# DL0WH_BiTuner_Ctrl_1V2.net
KiCad netlist of a schematic drawn in EAGLE
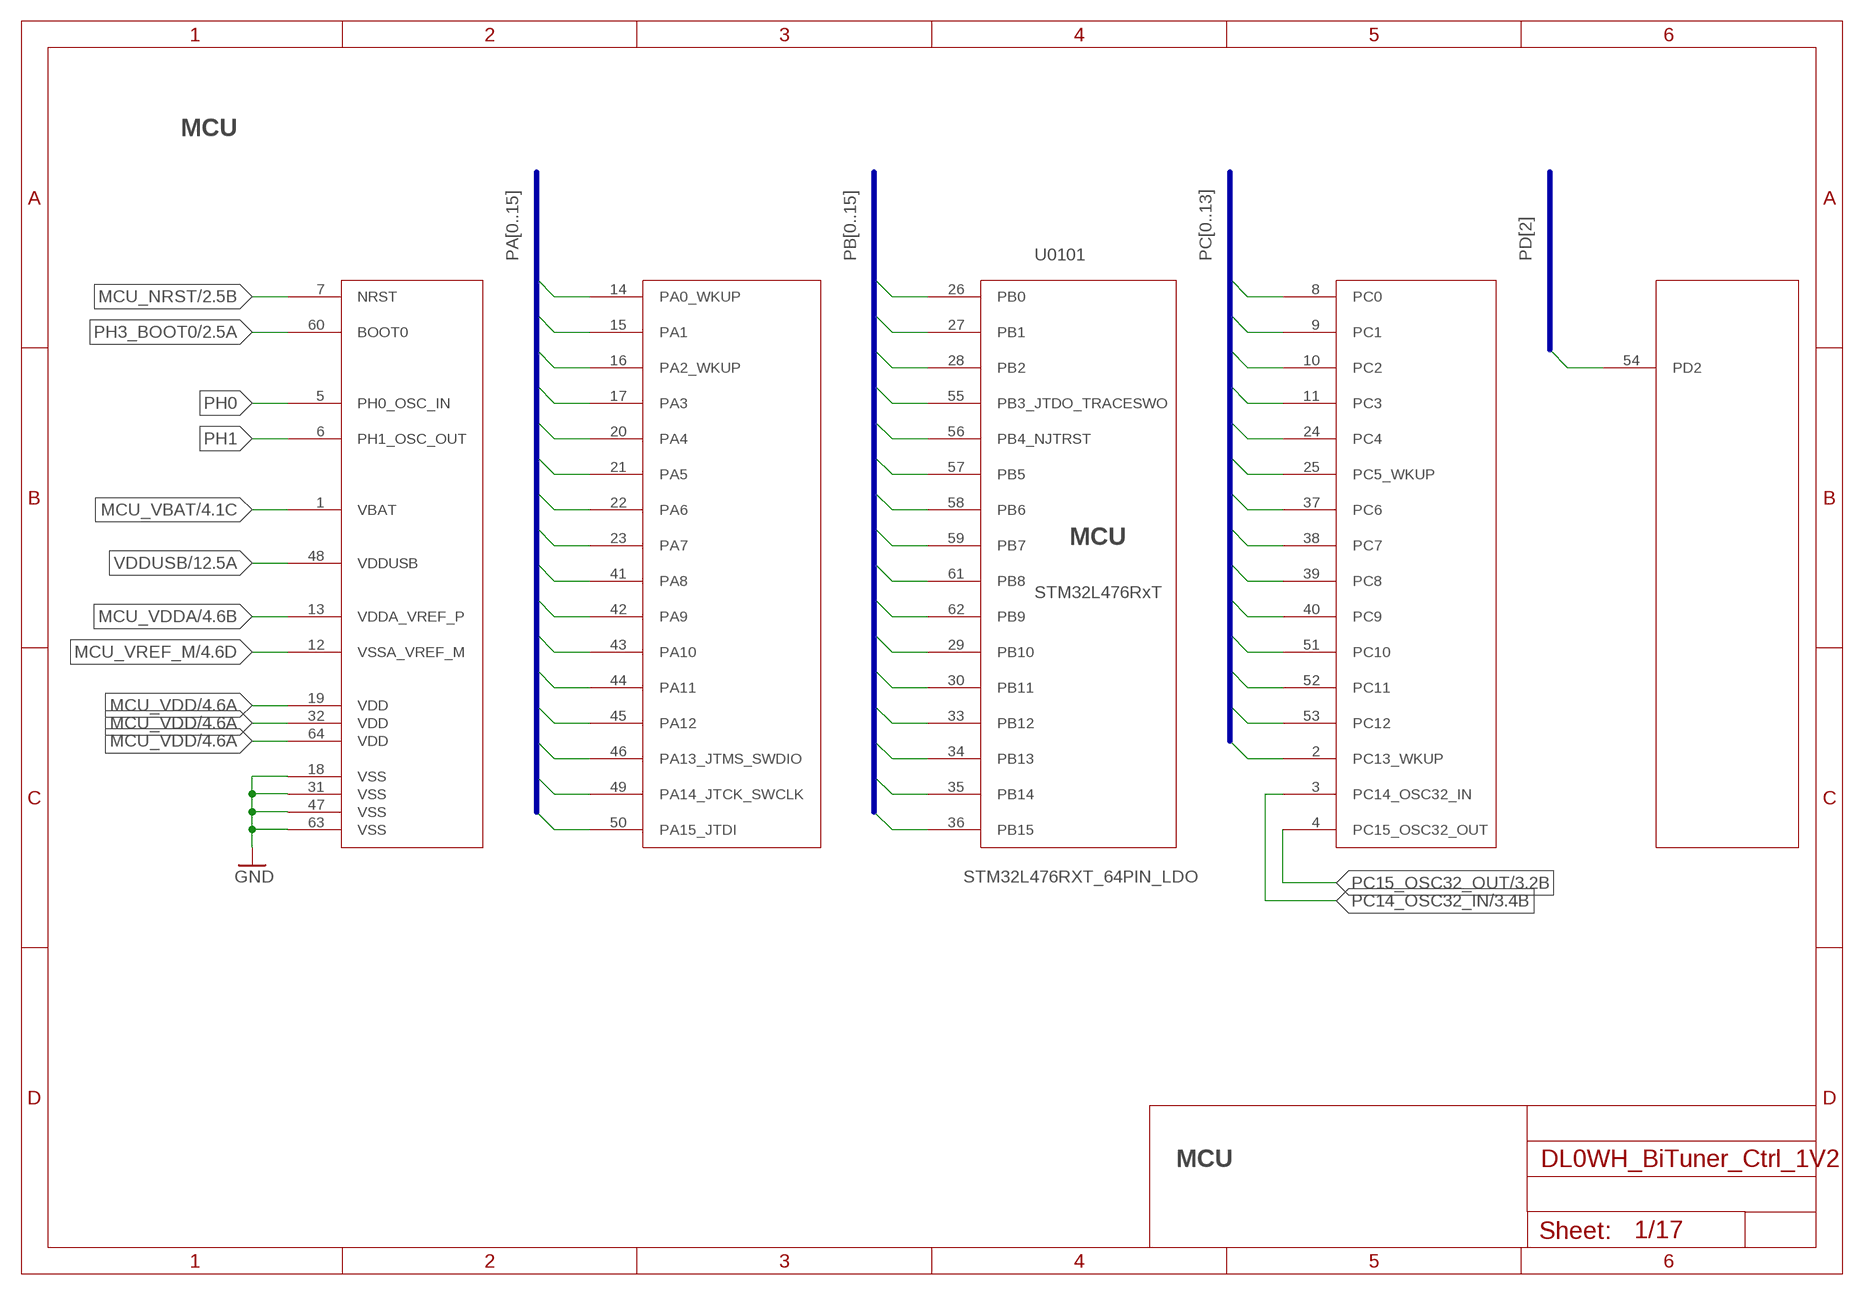
[diagram p0: schematic, sheet 1]
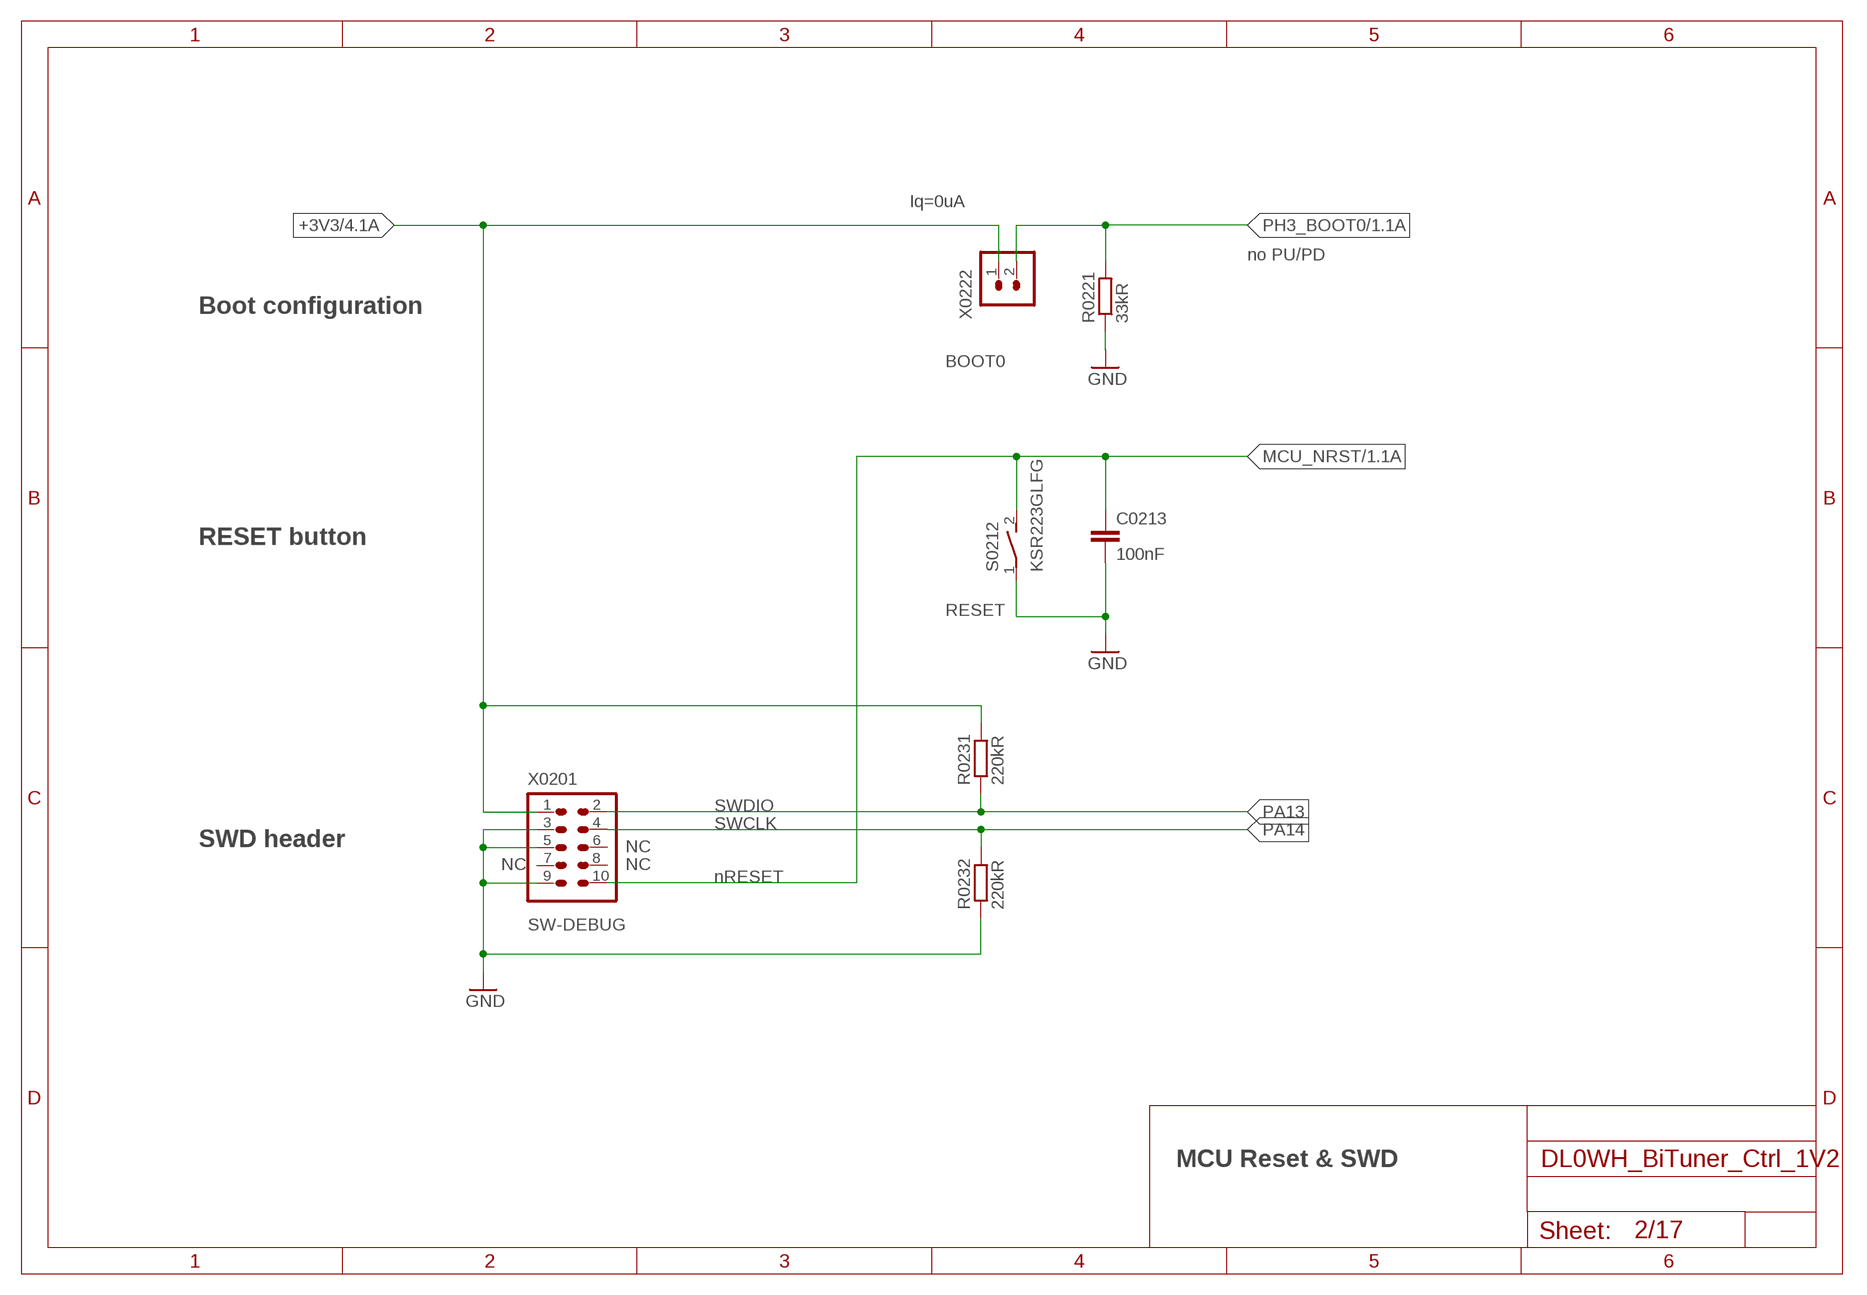
[diagram p1: schematic, sheet 2]
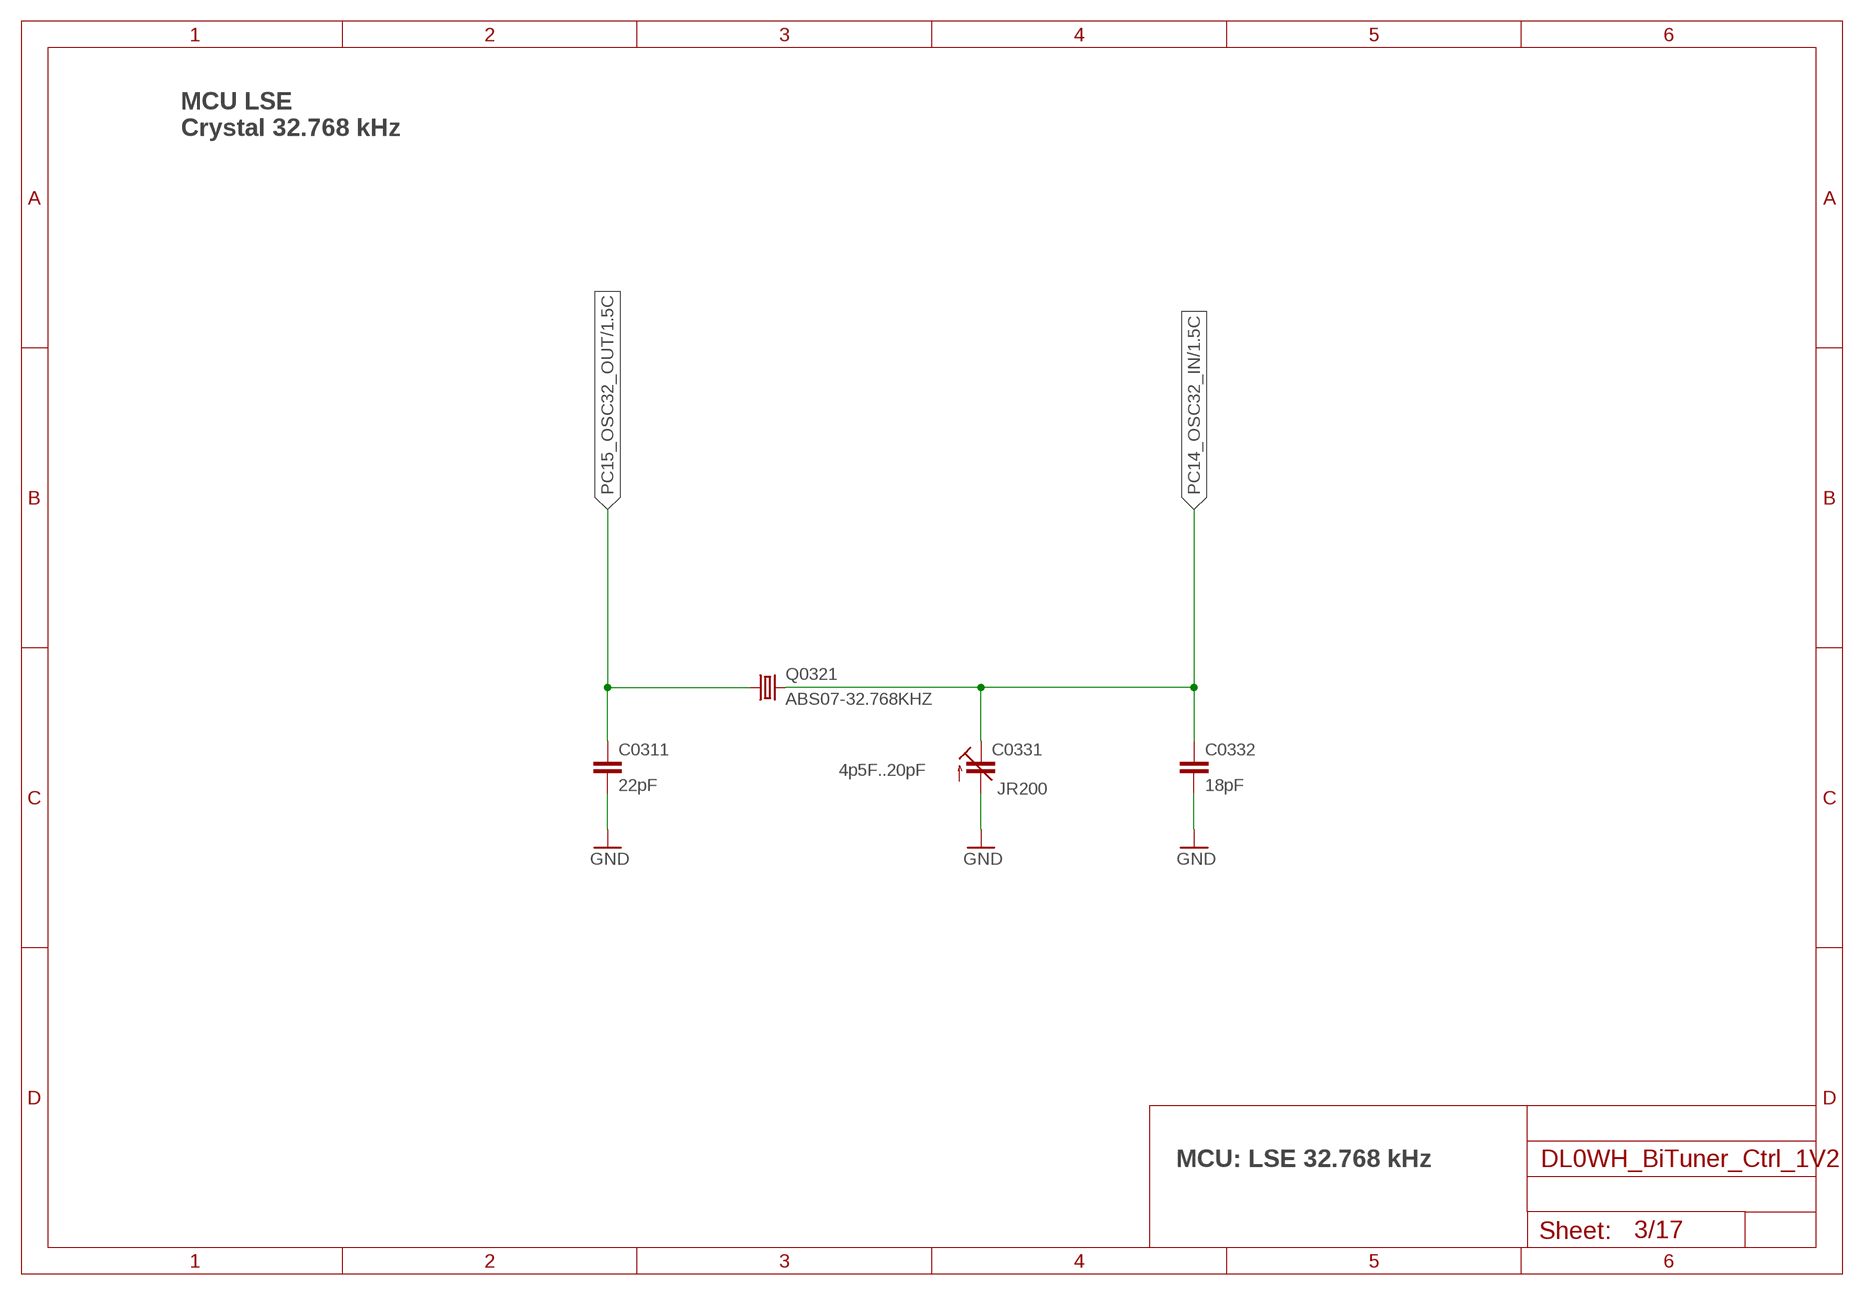
[diagram p2: schematic, sheet 3]
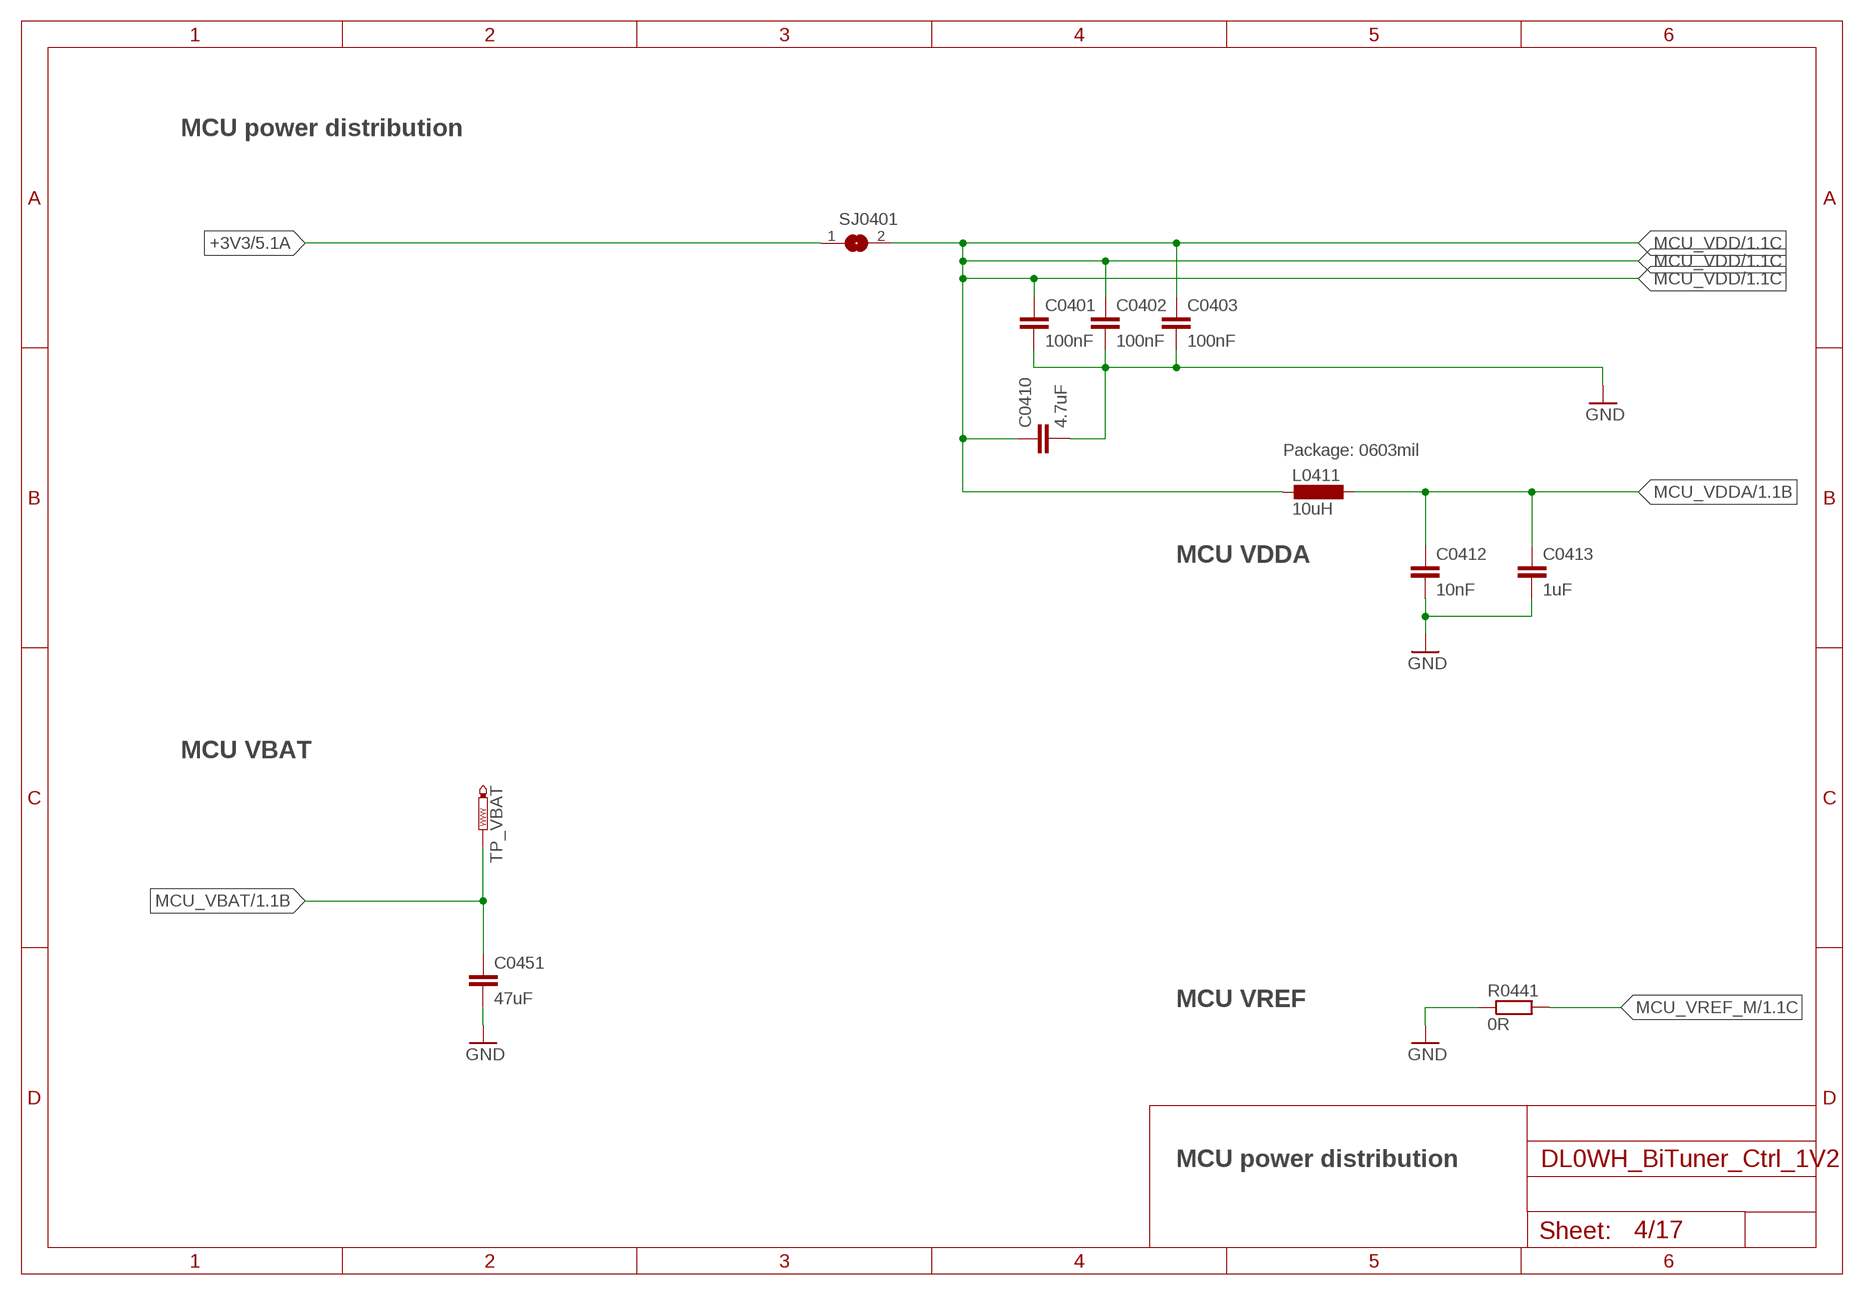
[diagram p3: schematic, sheet 4]
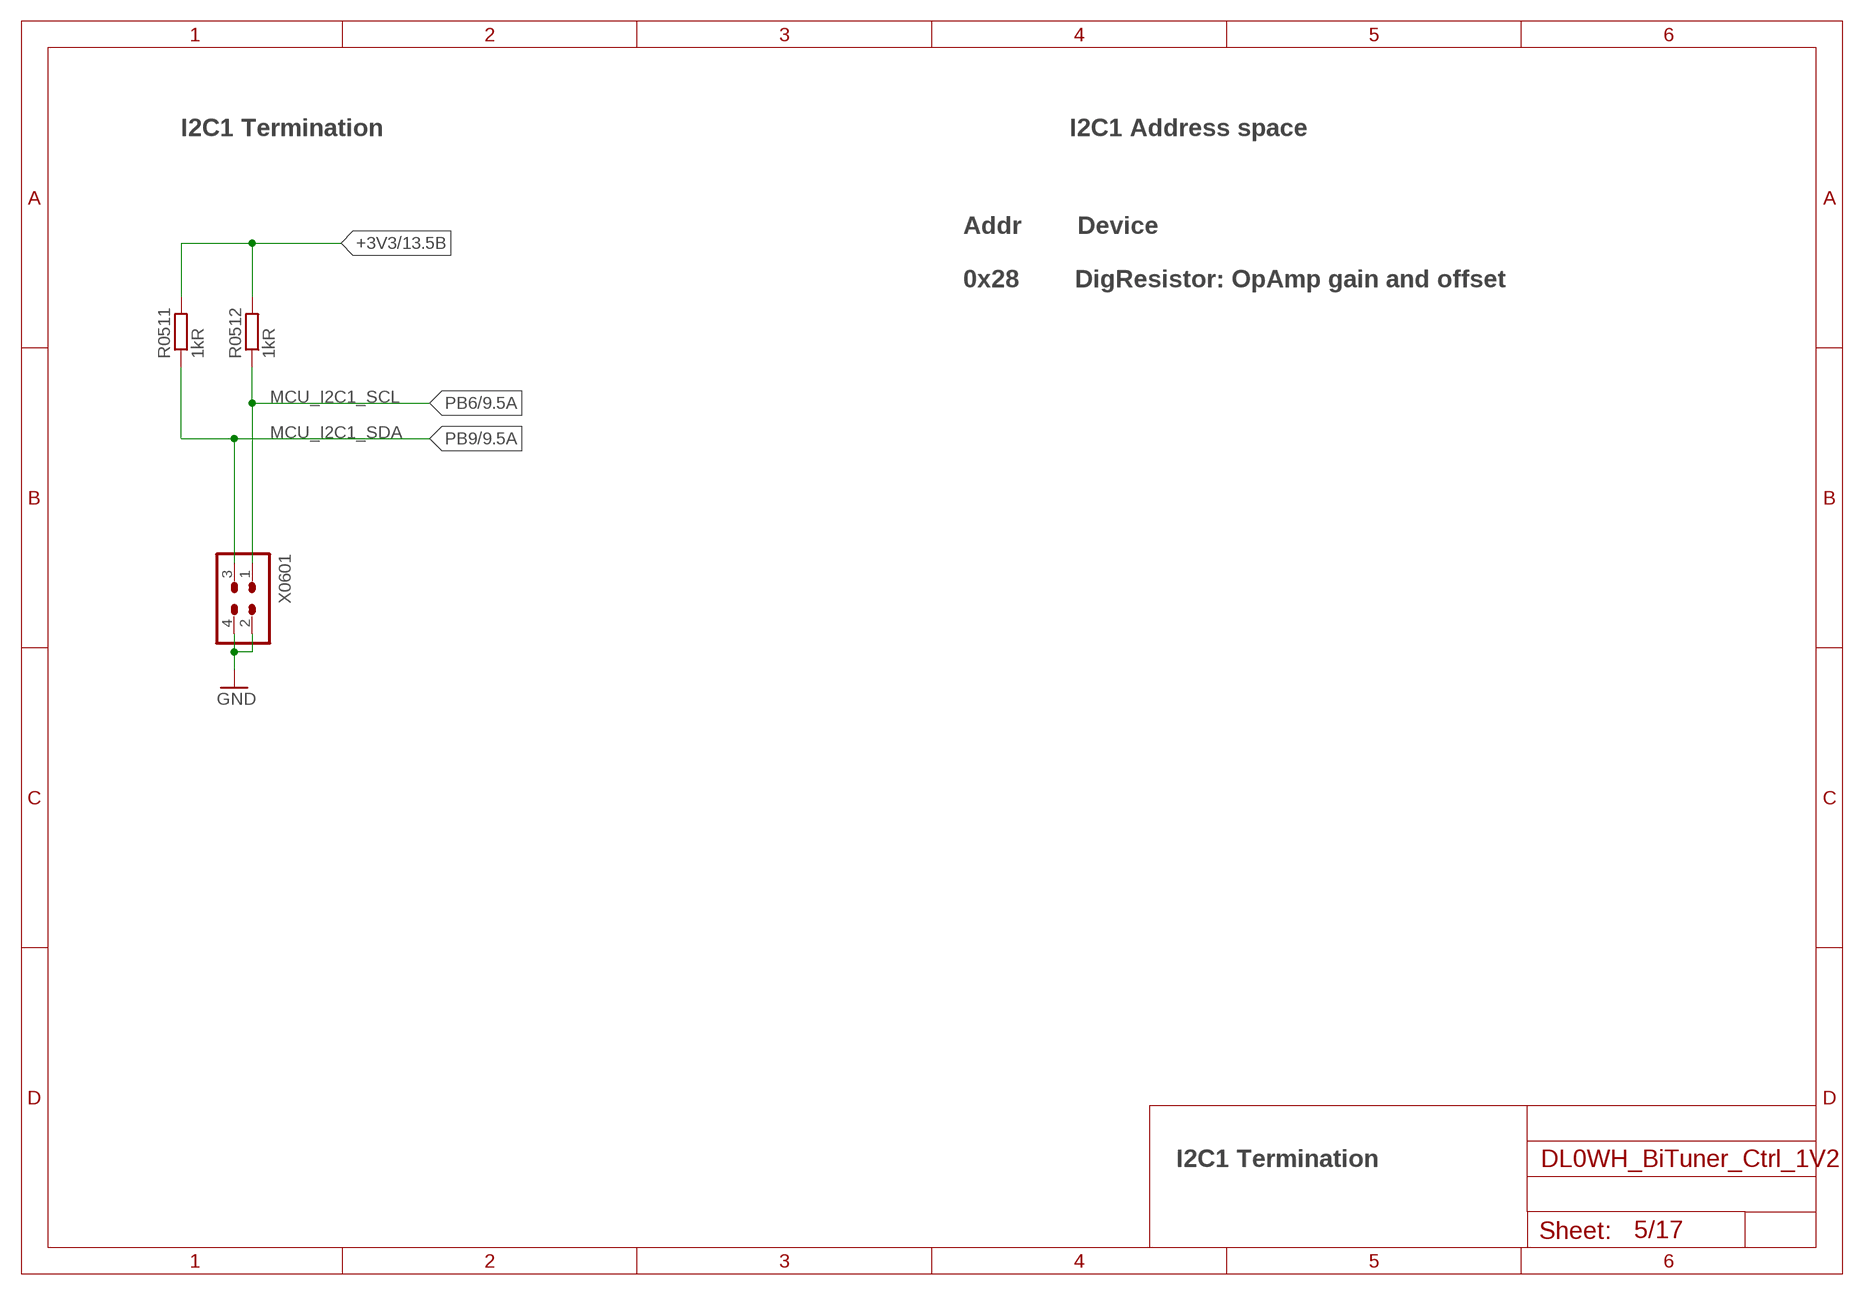
[diagram p4: schematic, sheet 5]
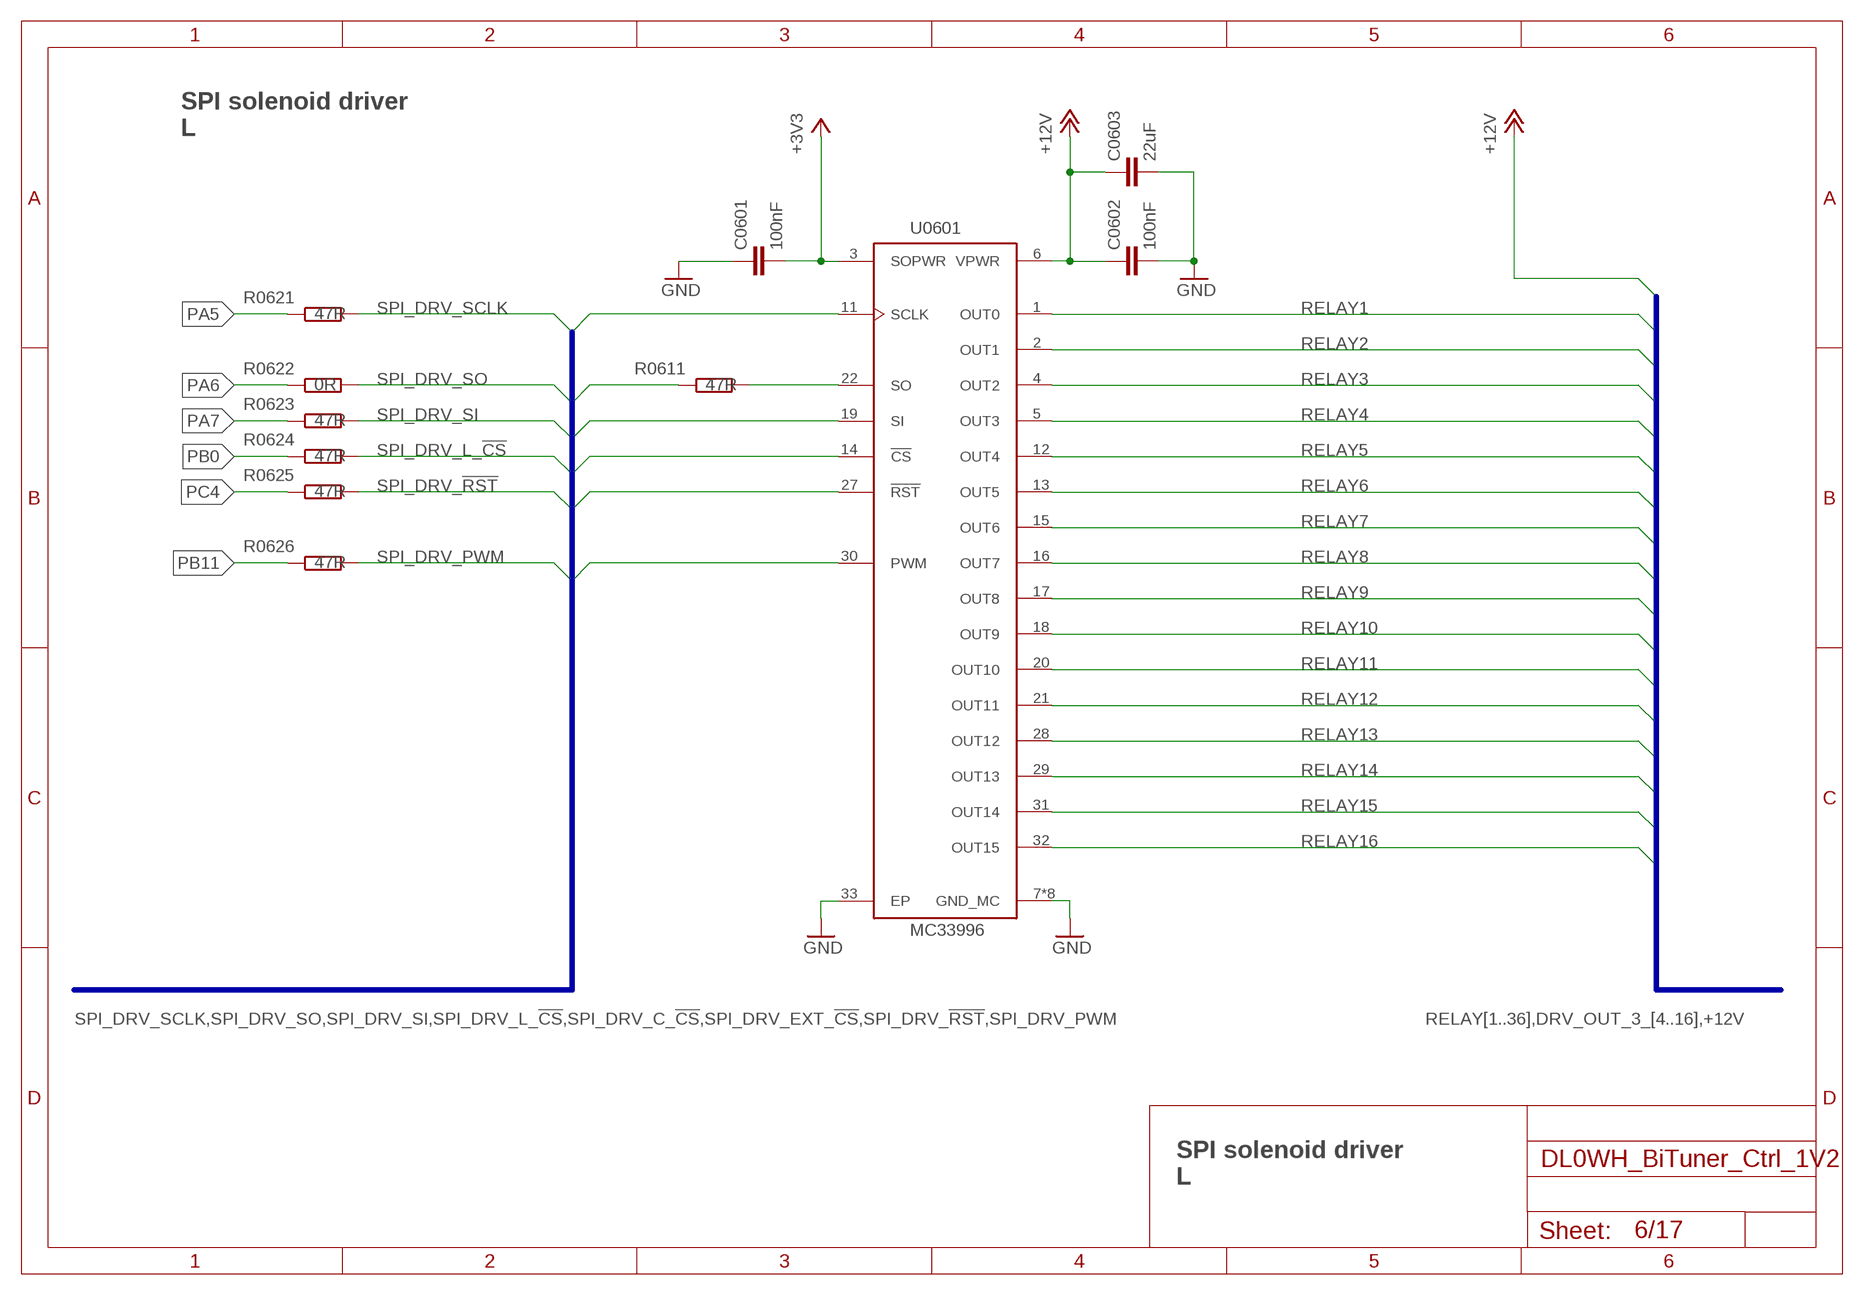
[diagram p5: schematic, sheet 6]
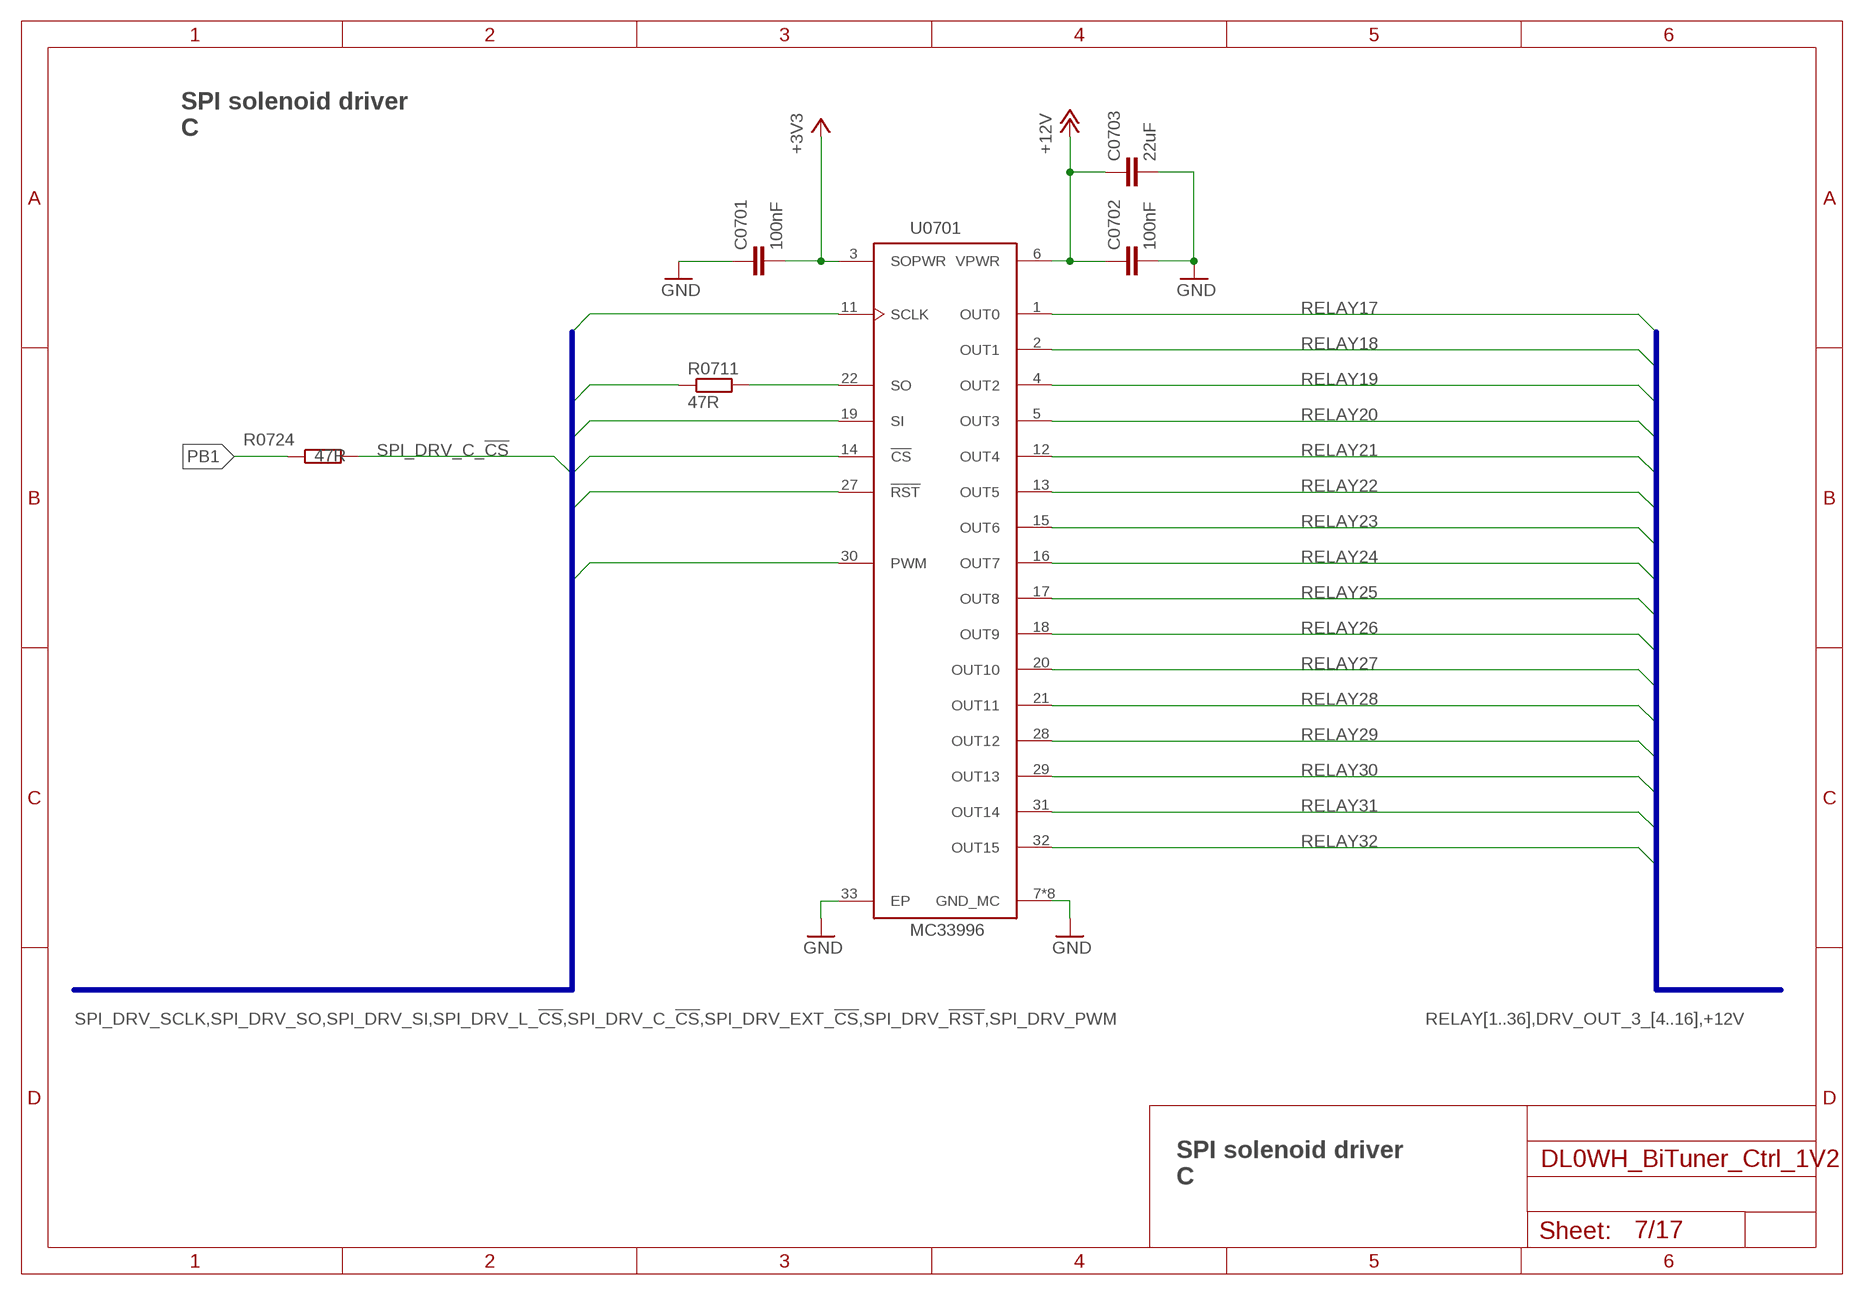
[diagram p6: schematic, sheet 7]
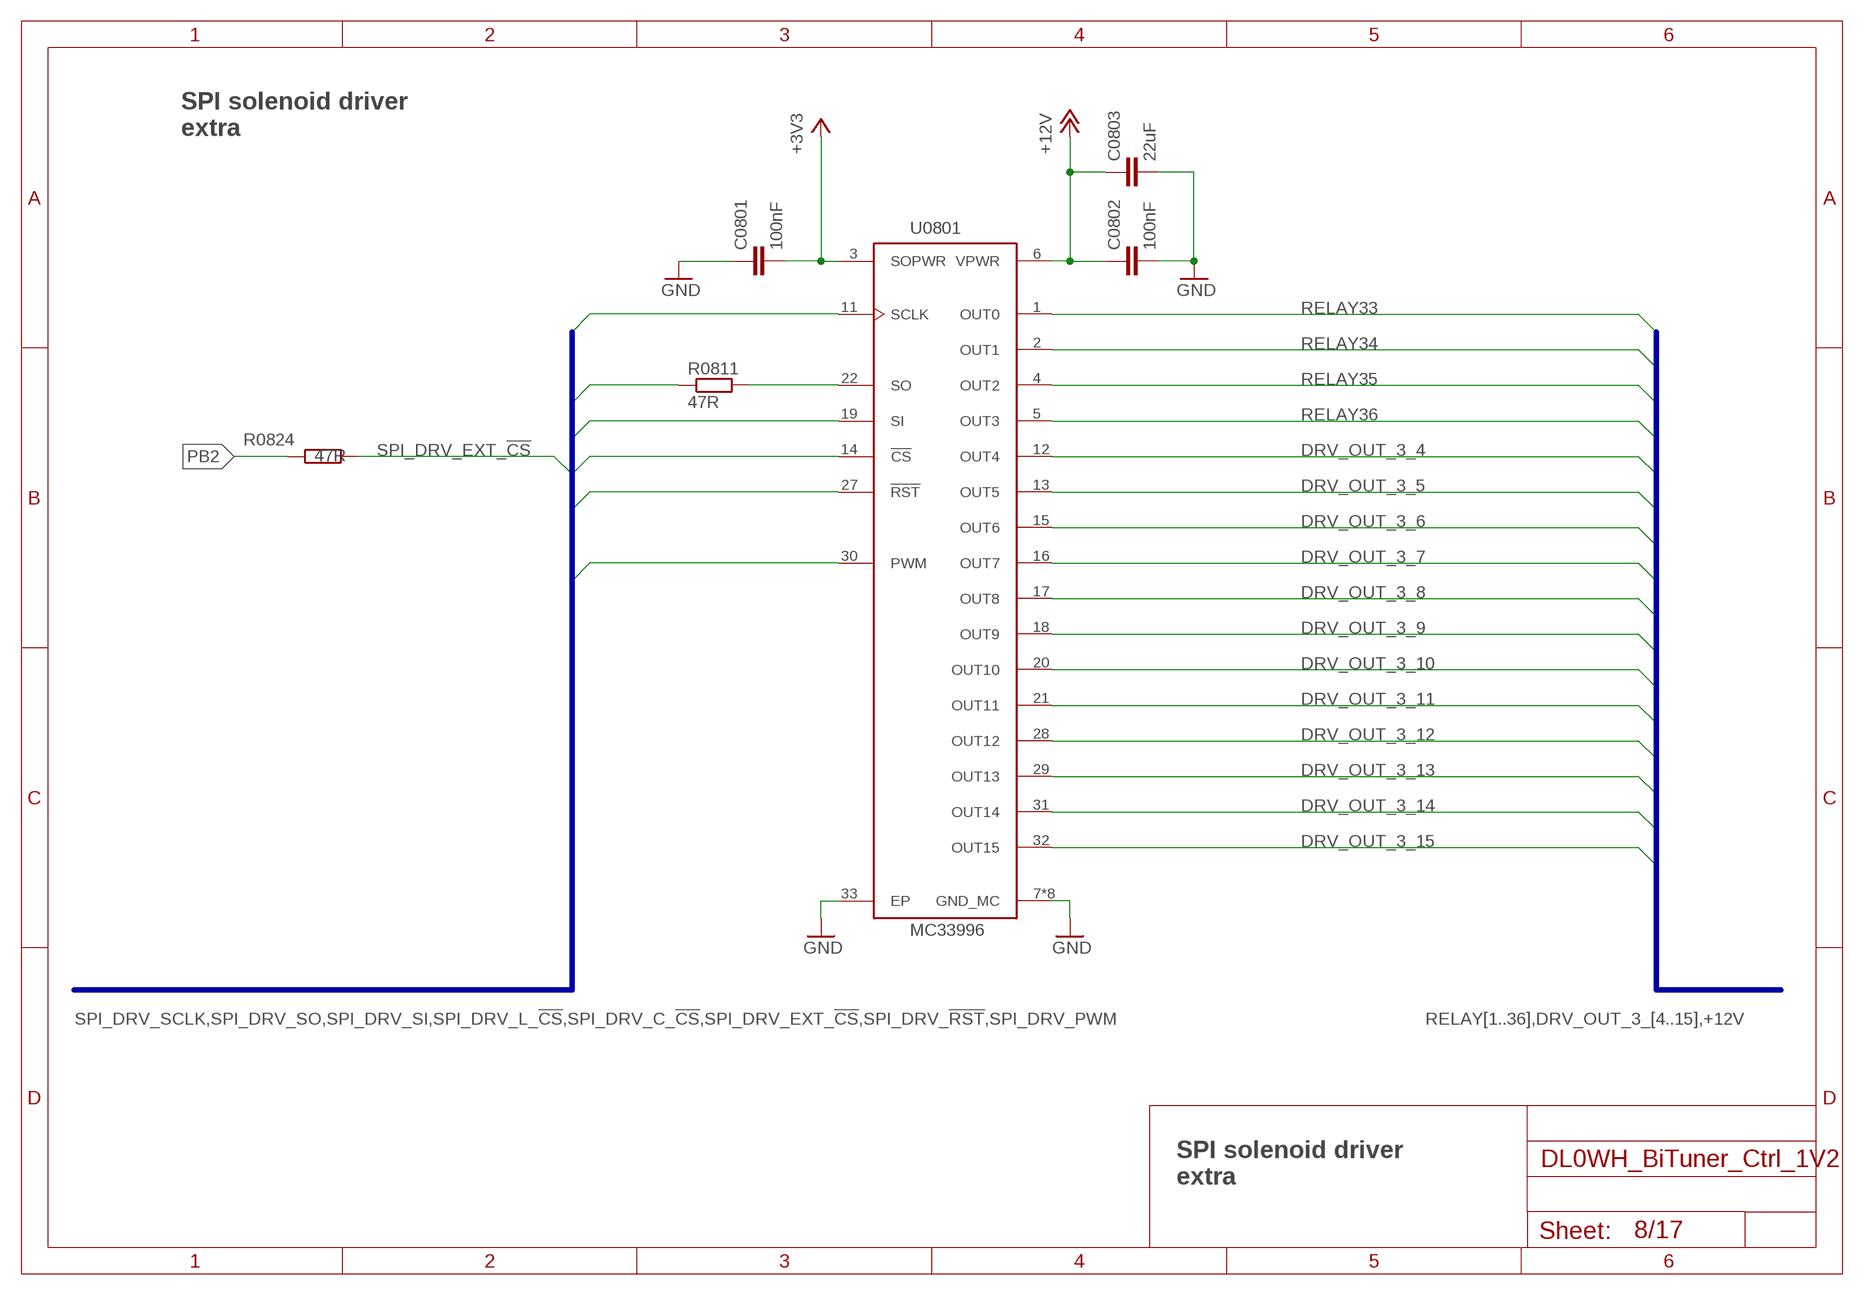
[diagram p7: schematic, sheet 8]
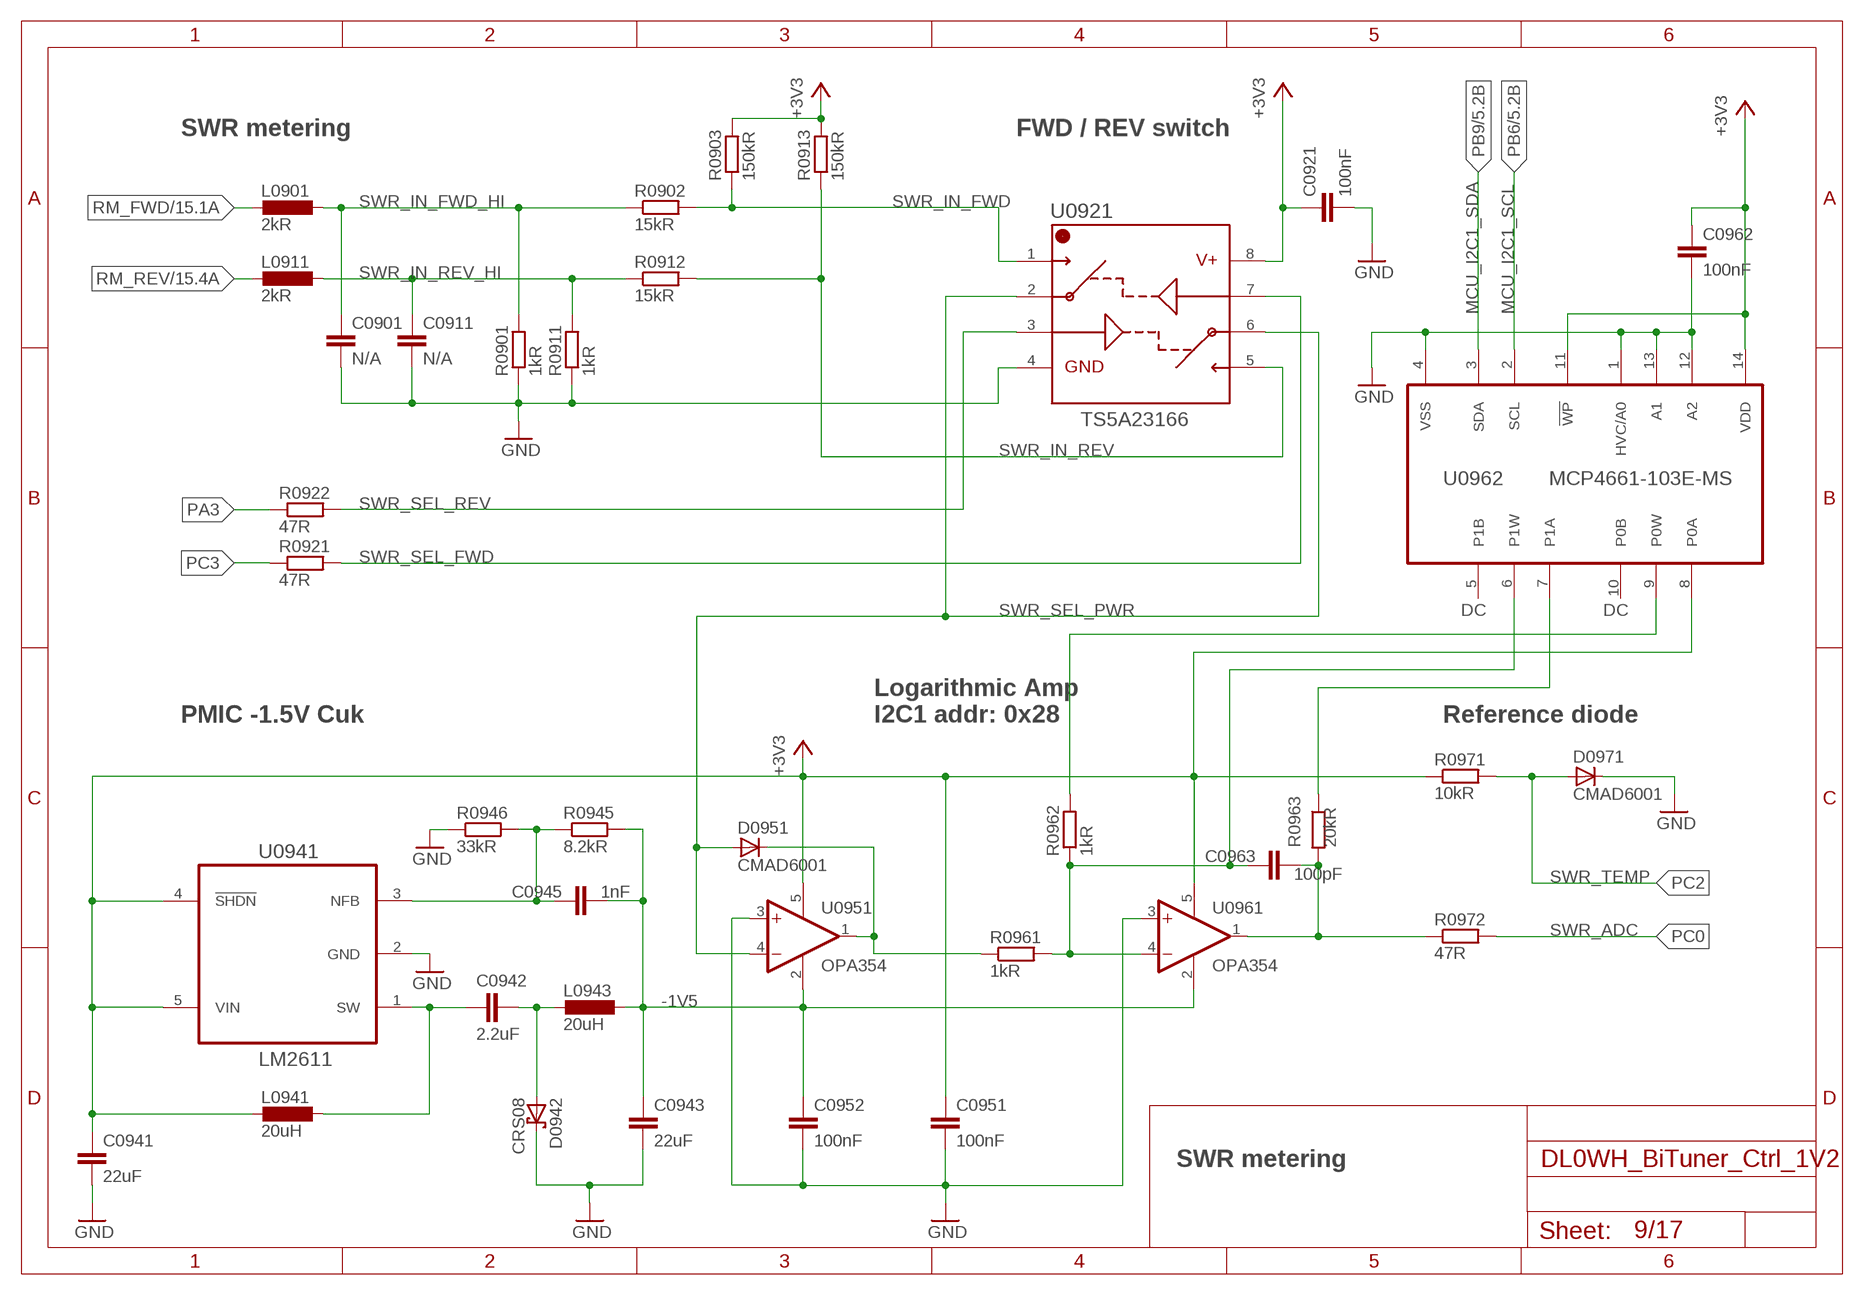
[diagram p8: schematic, sheet 9]
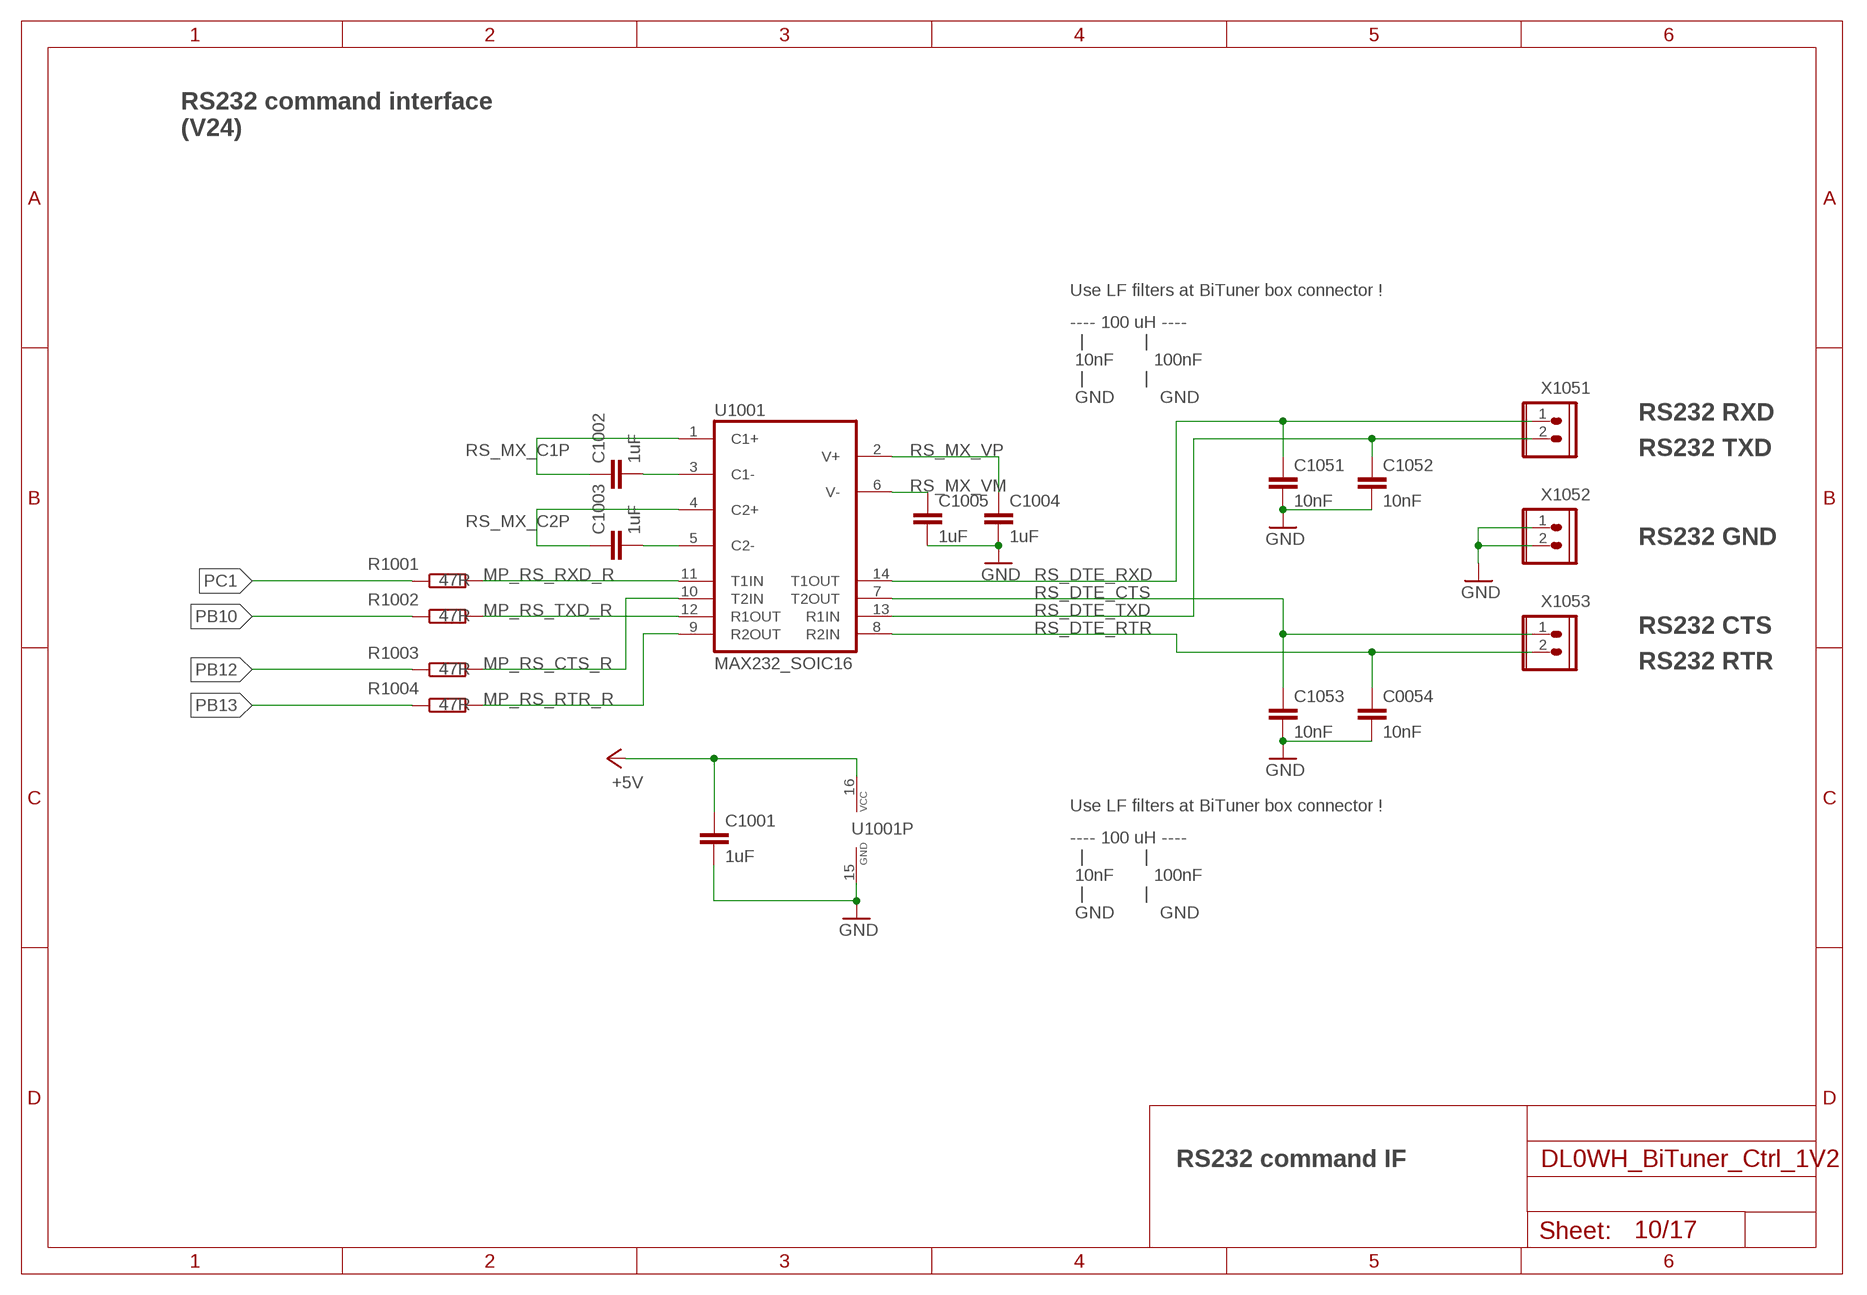
[diagram p9: schematic, sheet 10]
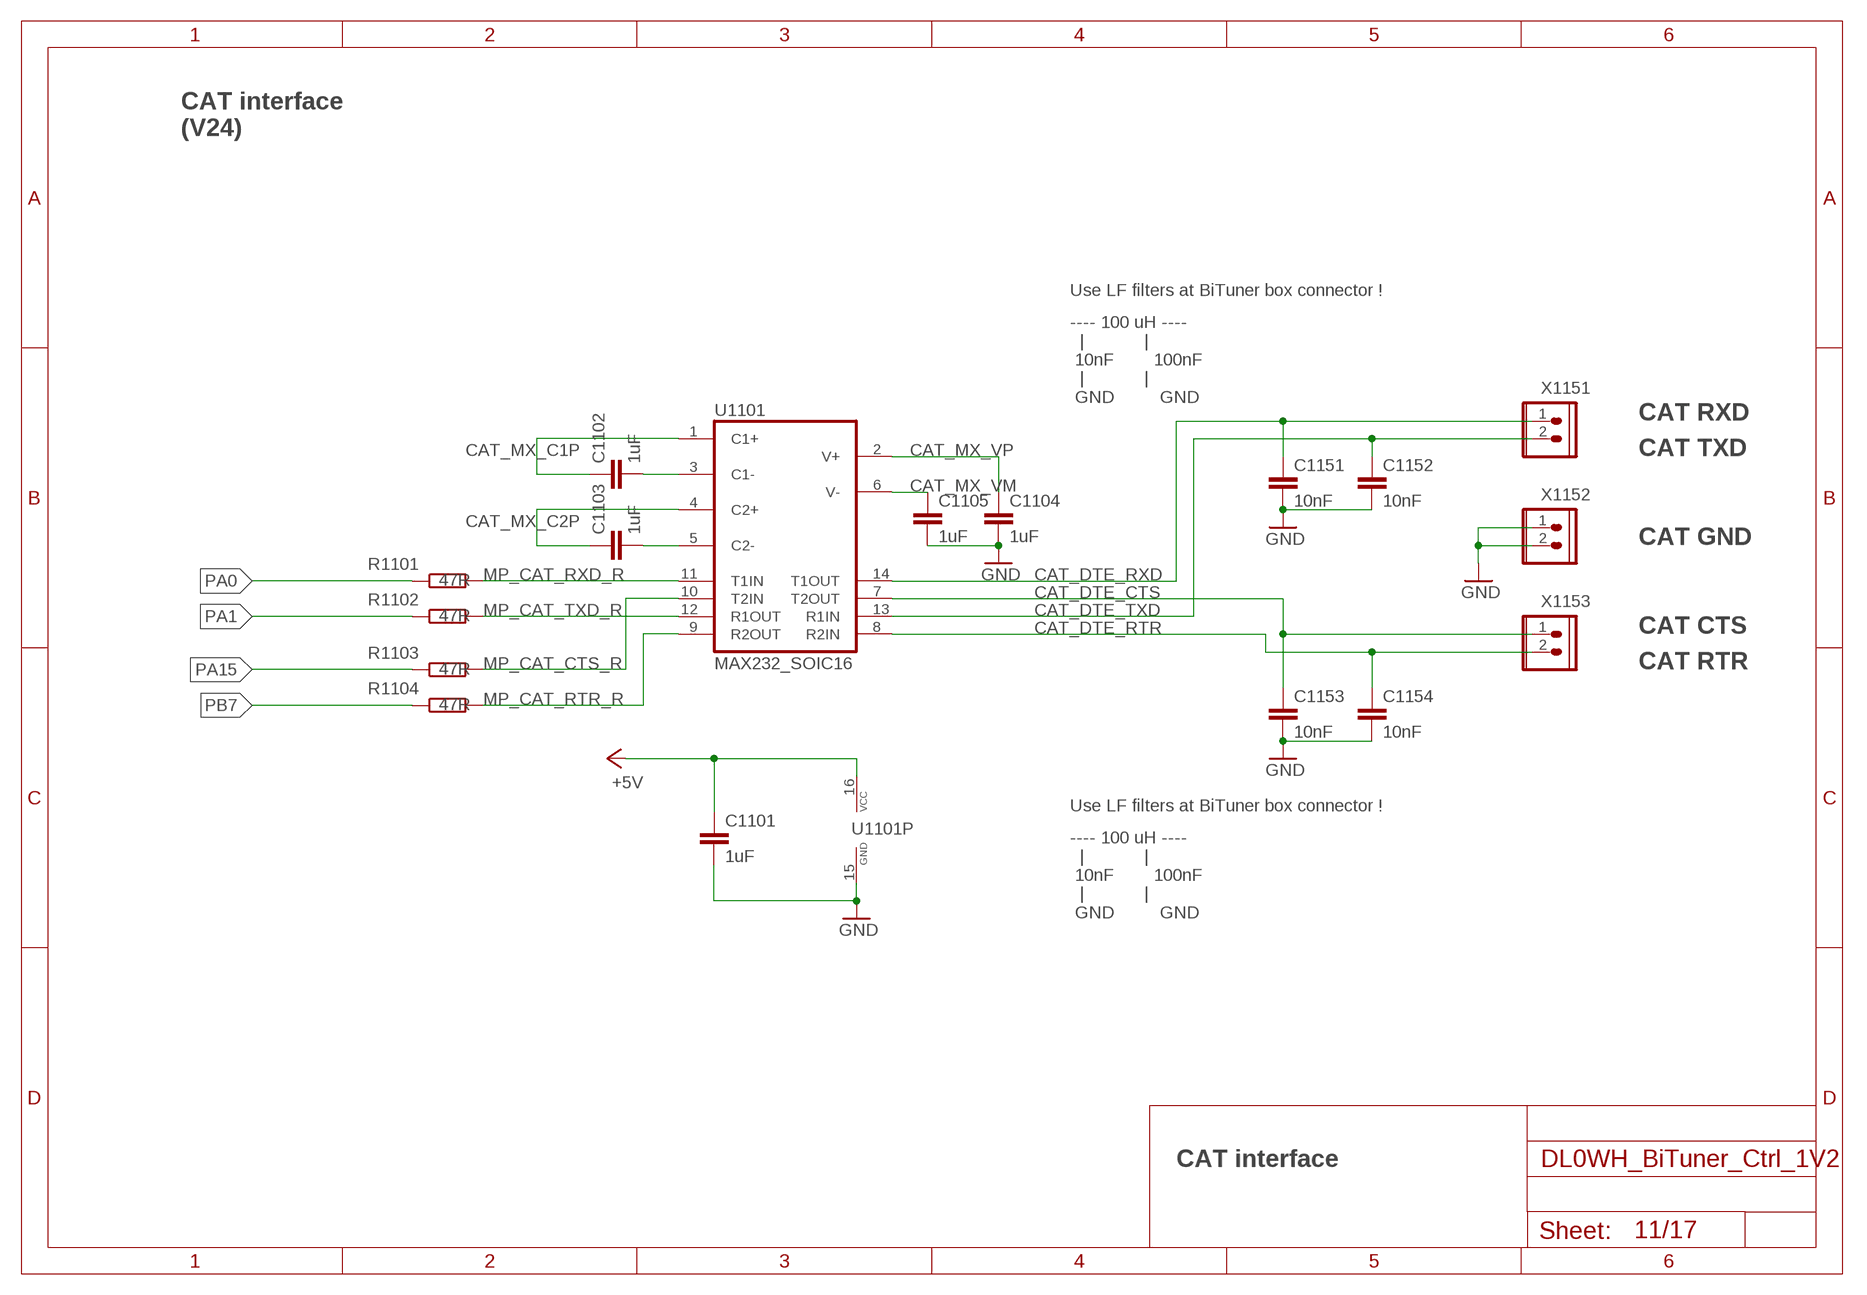
[diagram p10: schematic, sheet 11]
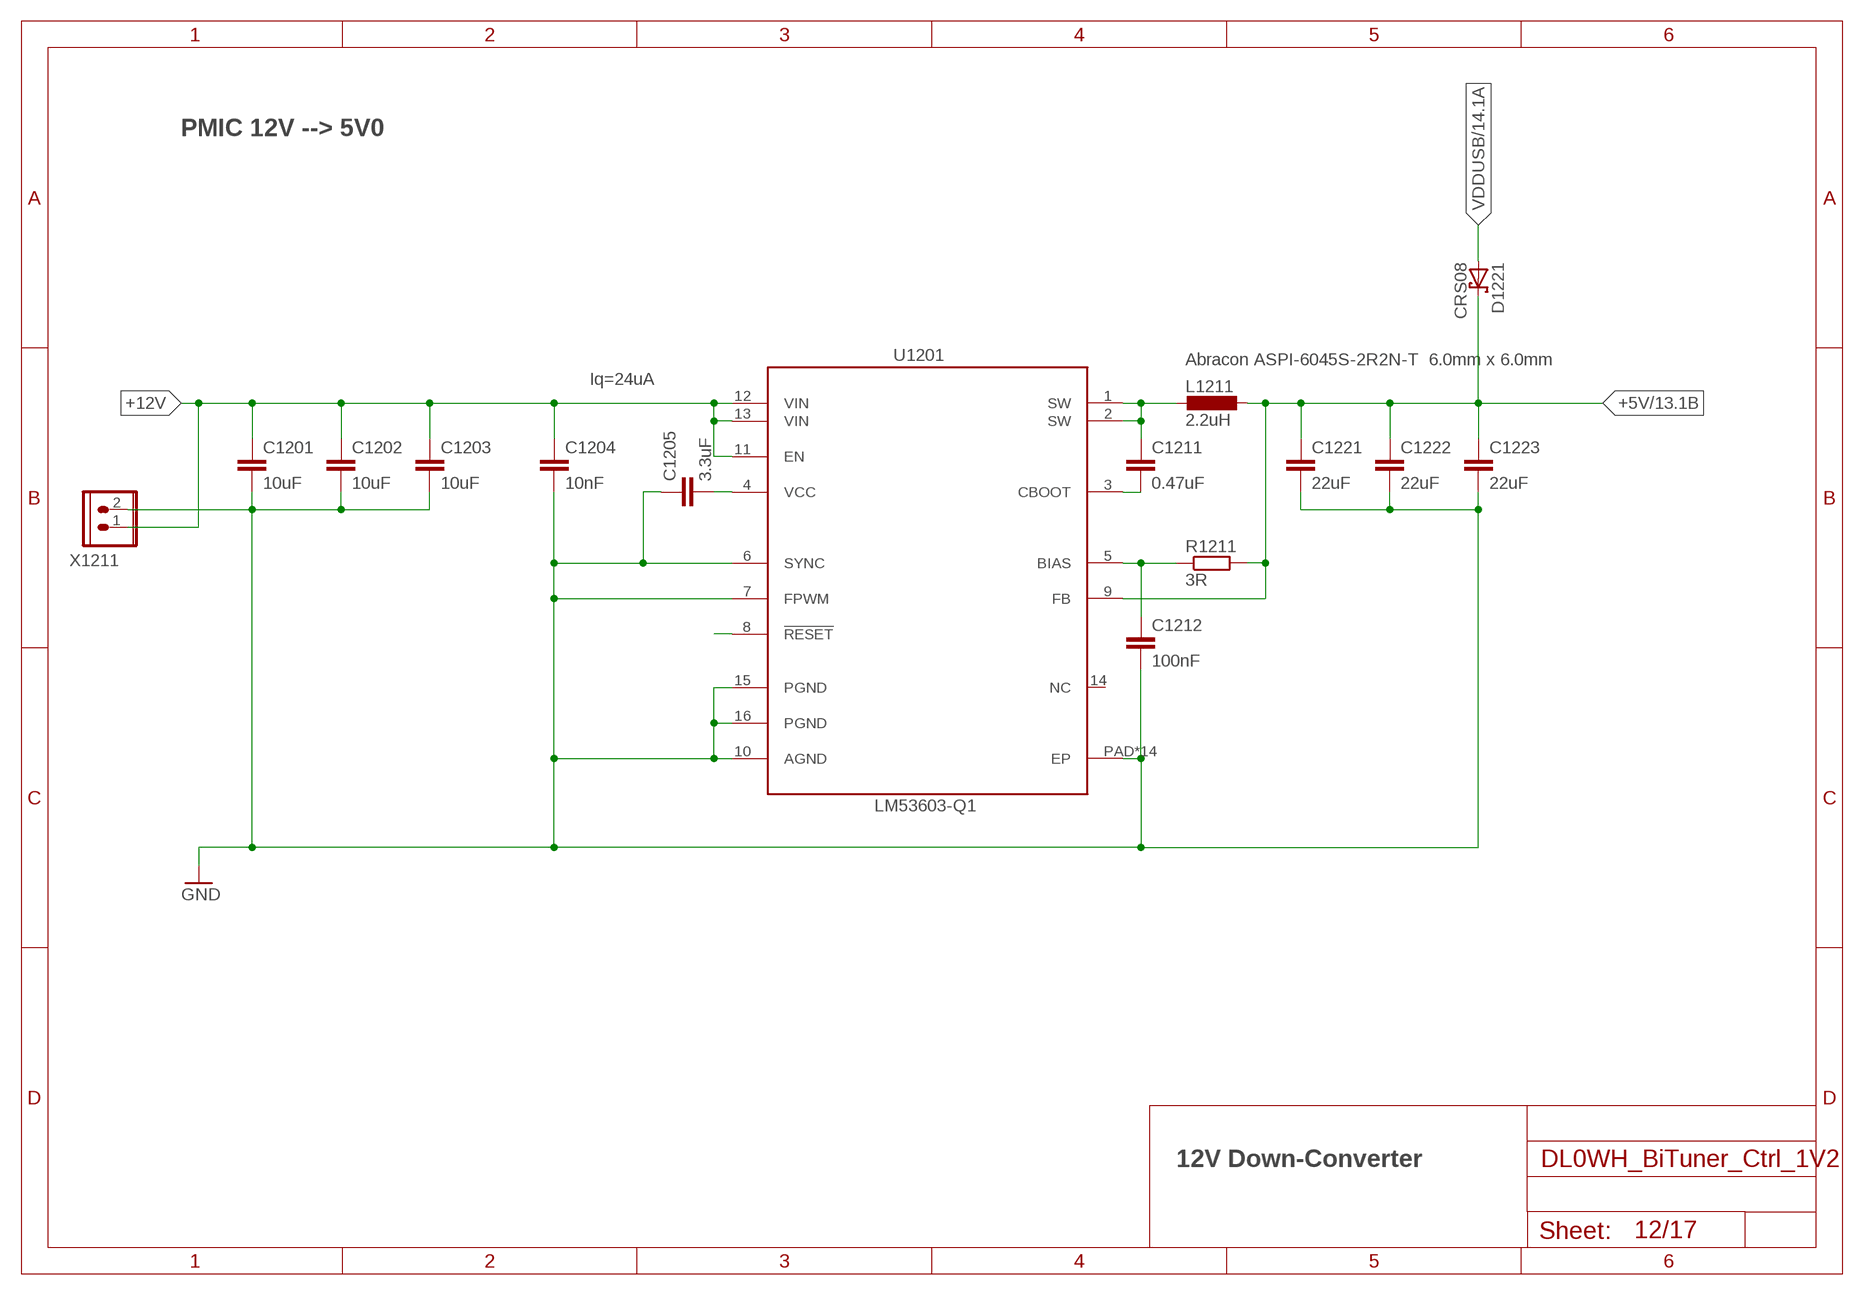
[diagram p11: schematic, sheet 12]
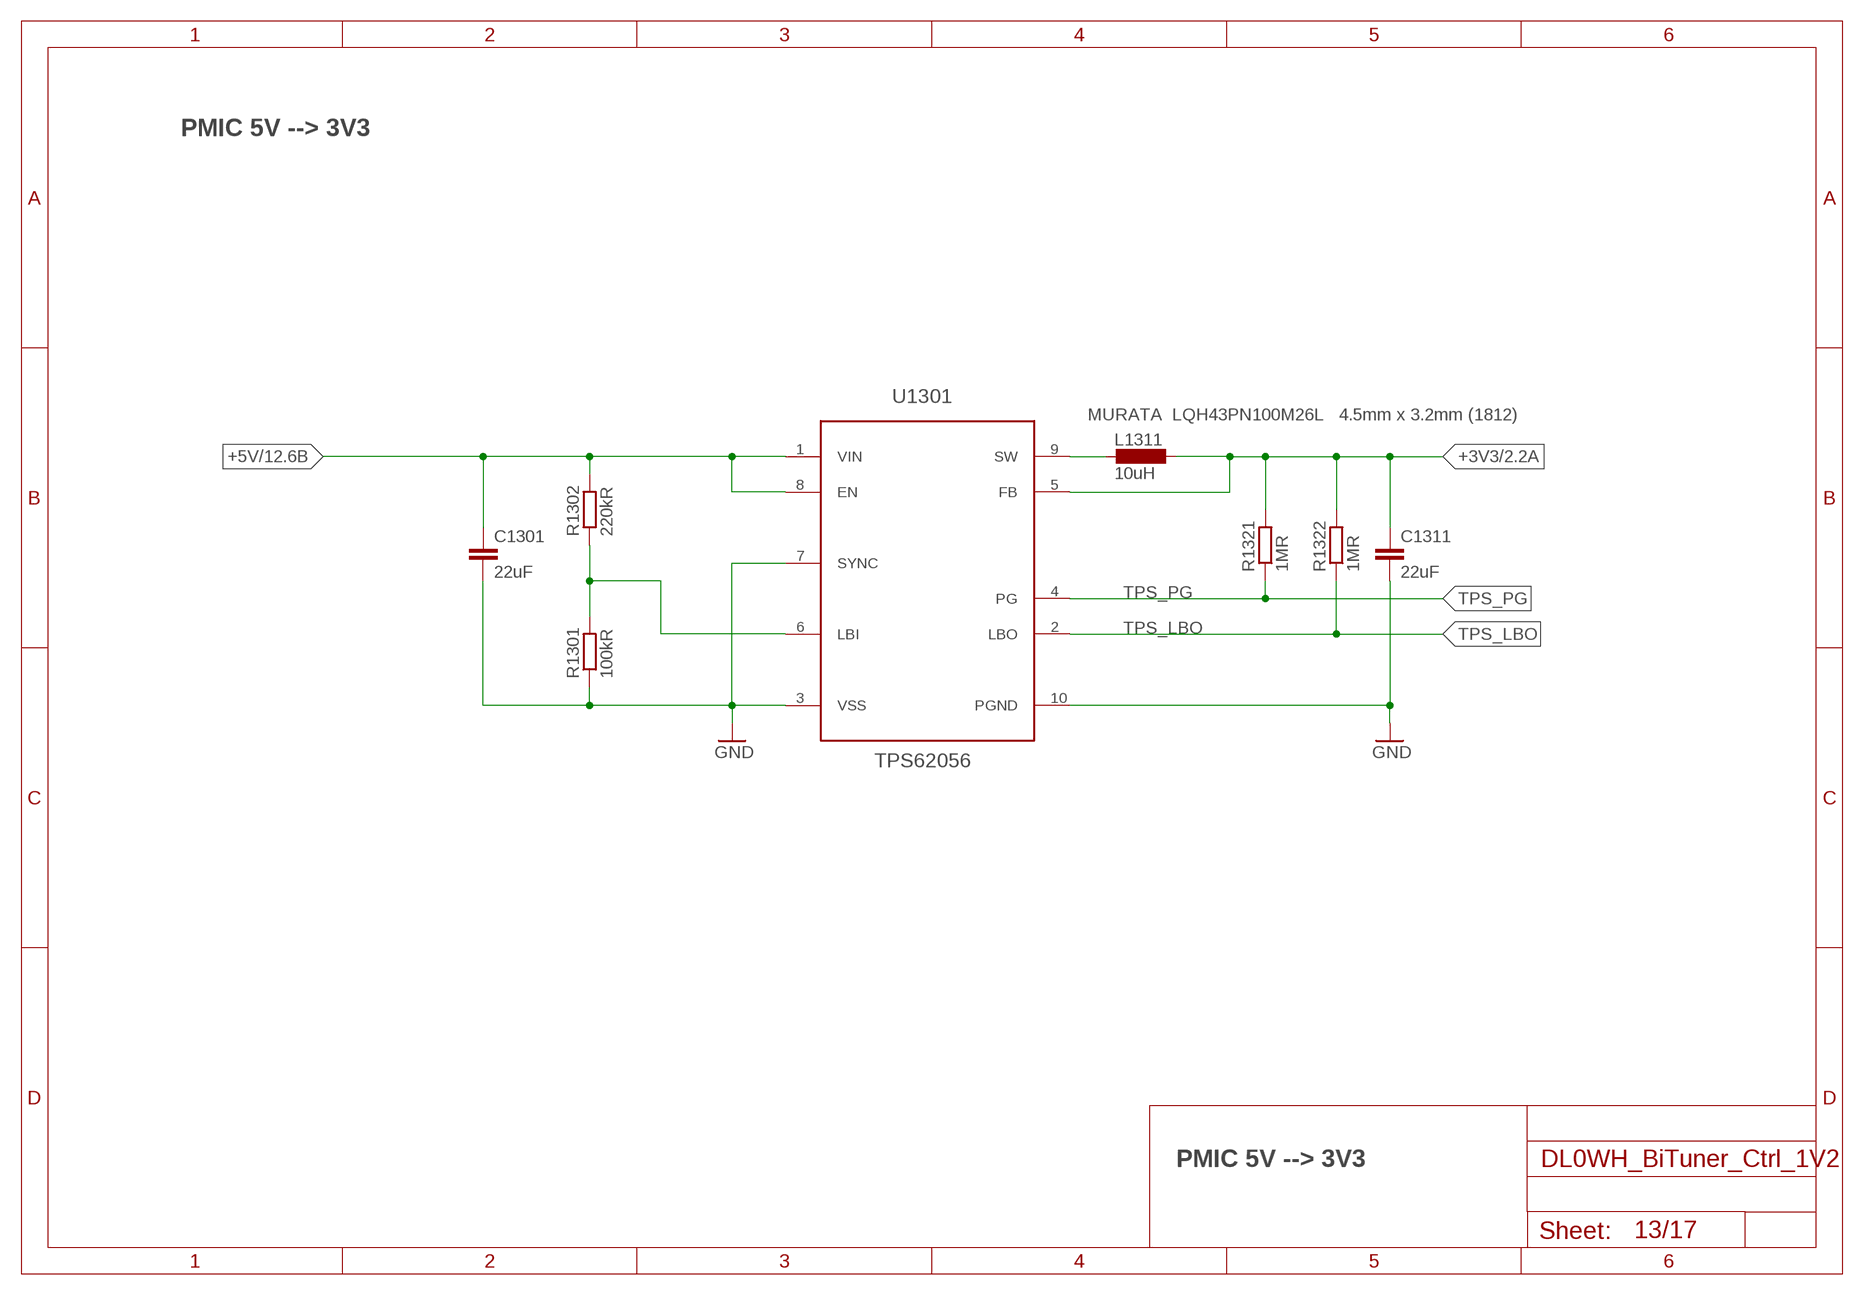
[diagram p12: schematic, sheet 13]
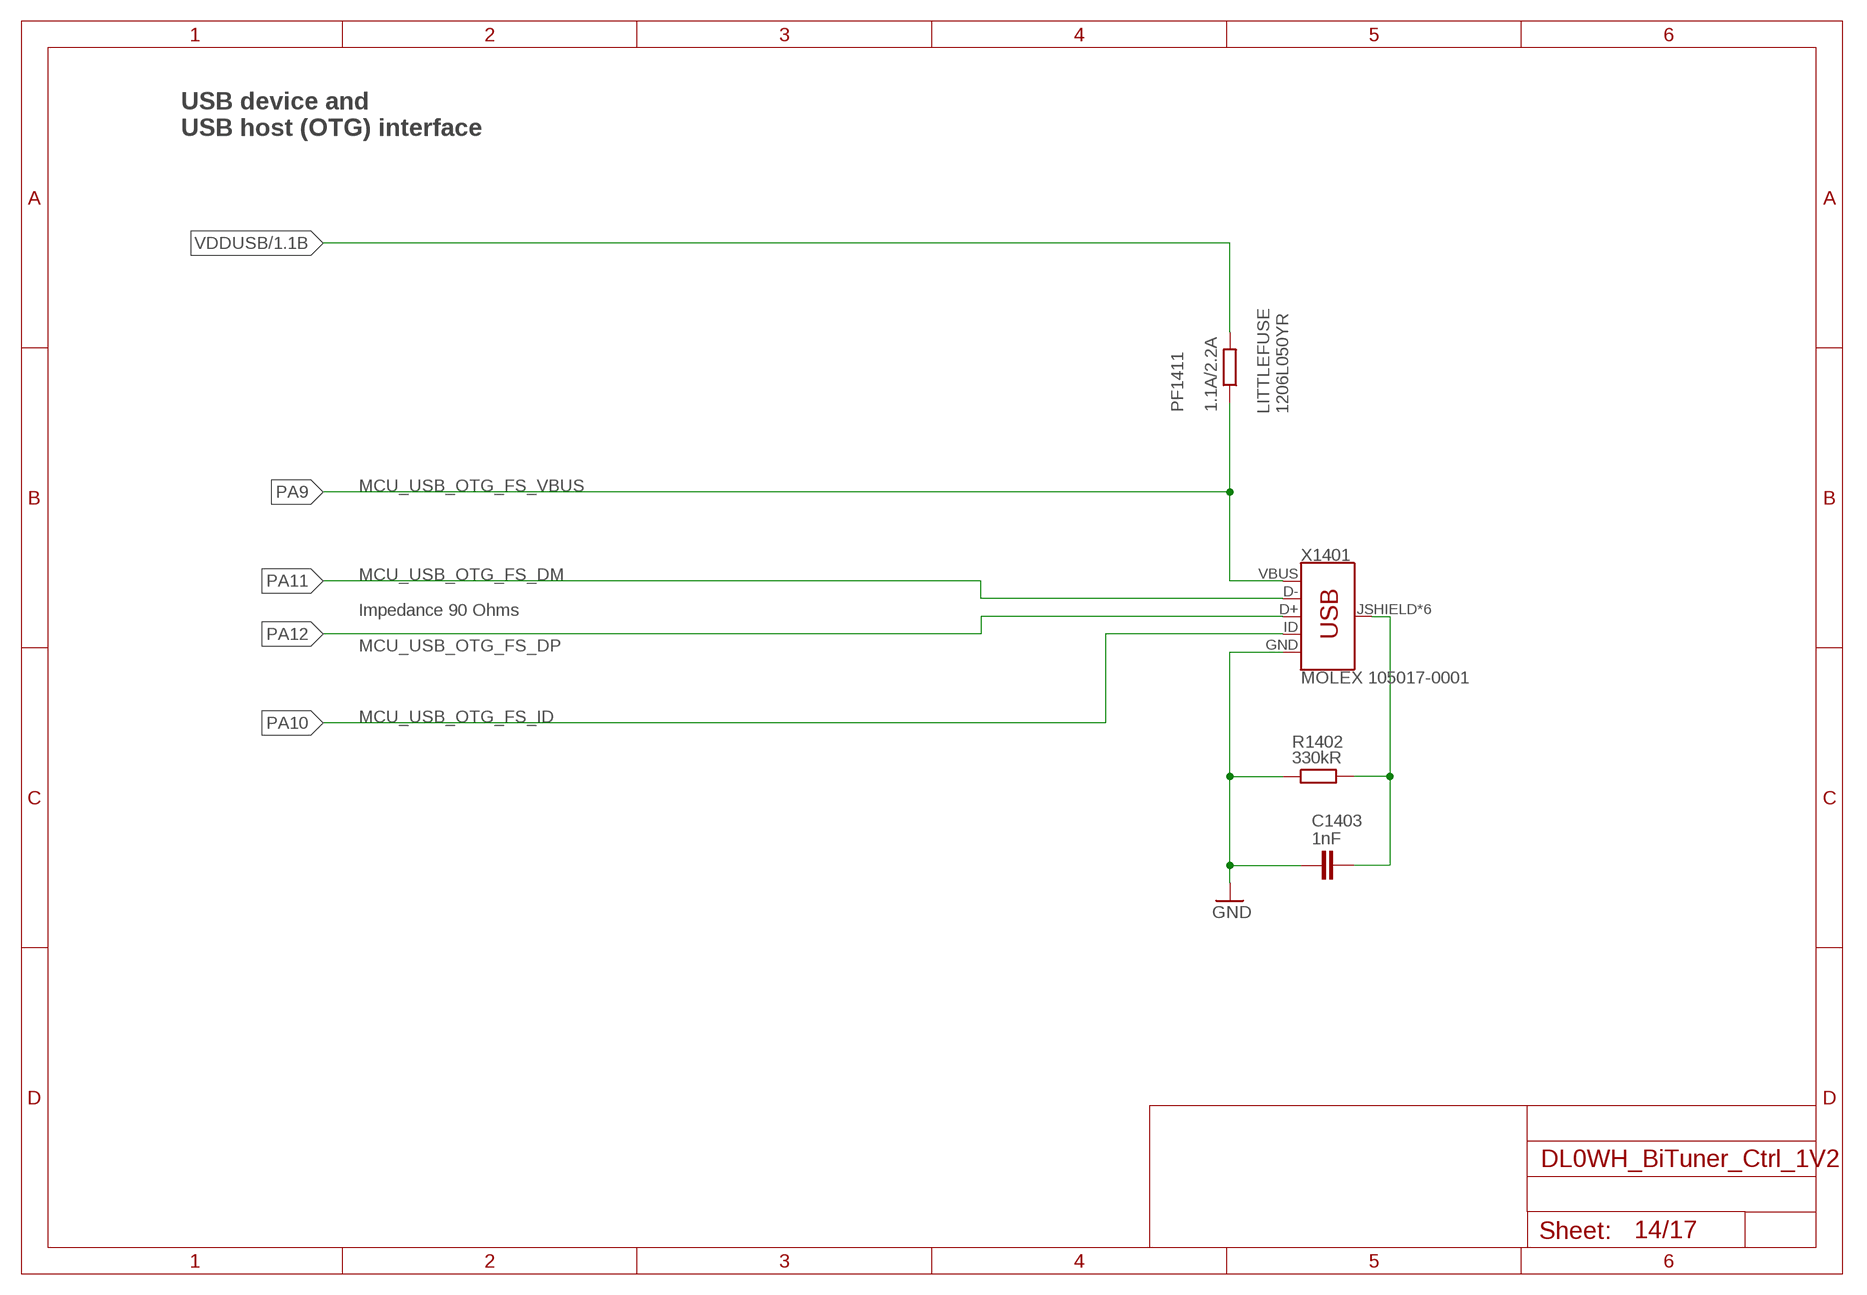
[diagram p13: schematic, sheet 14]
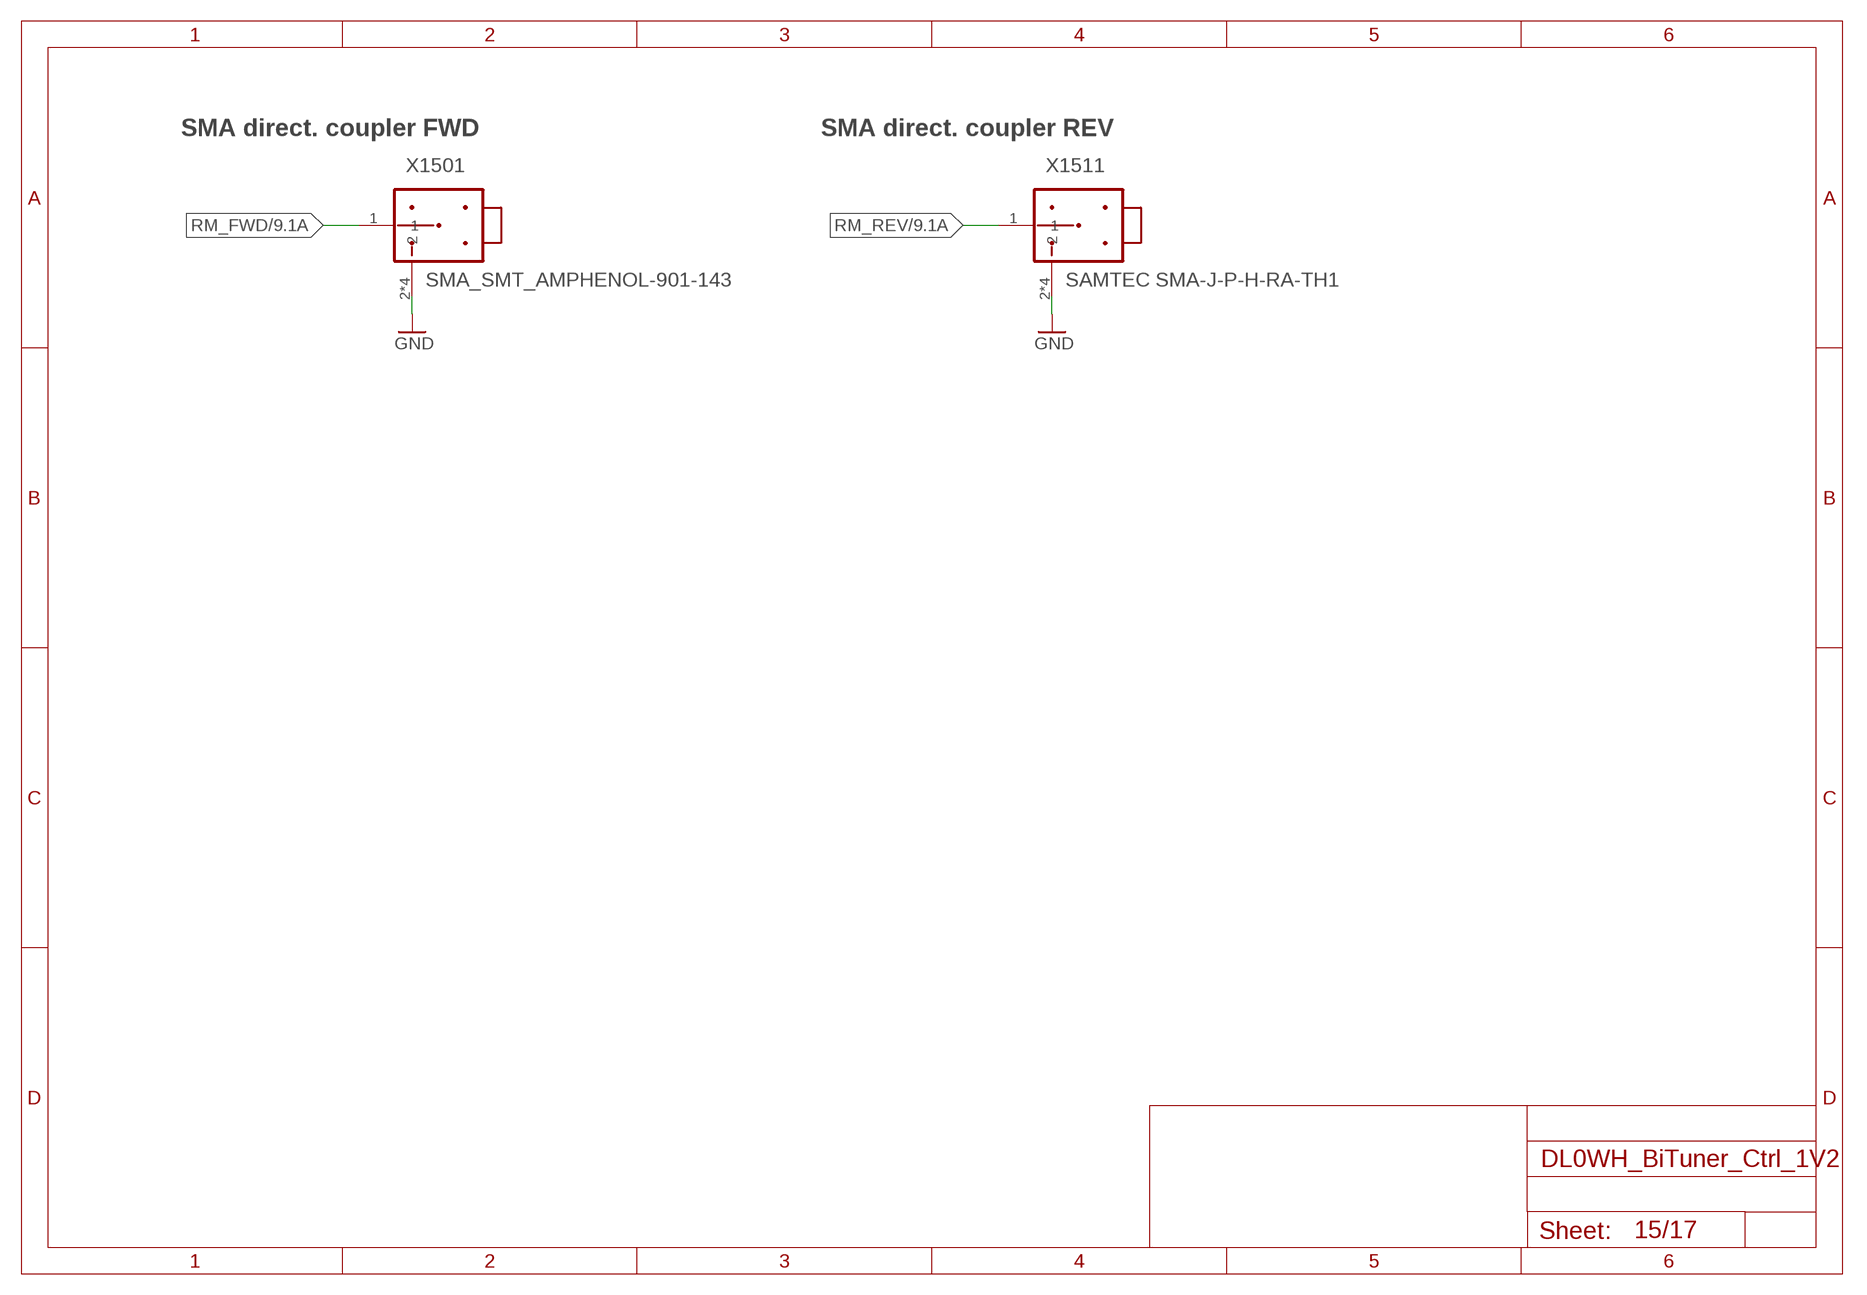
[diagram p14: schematic, sheet 15]
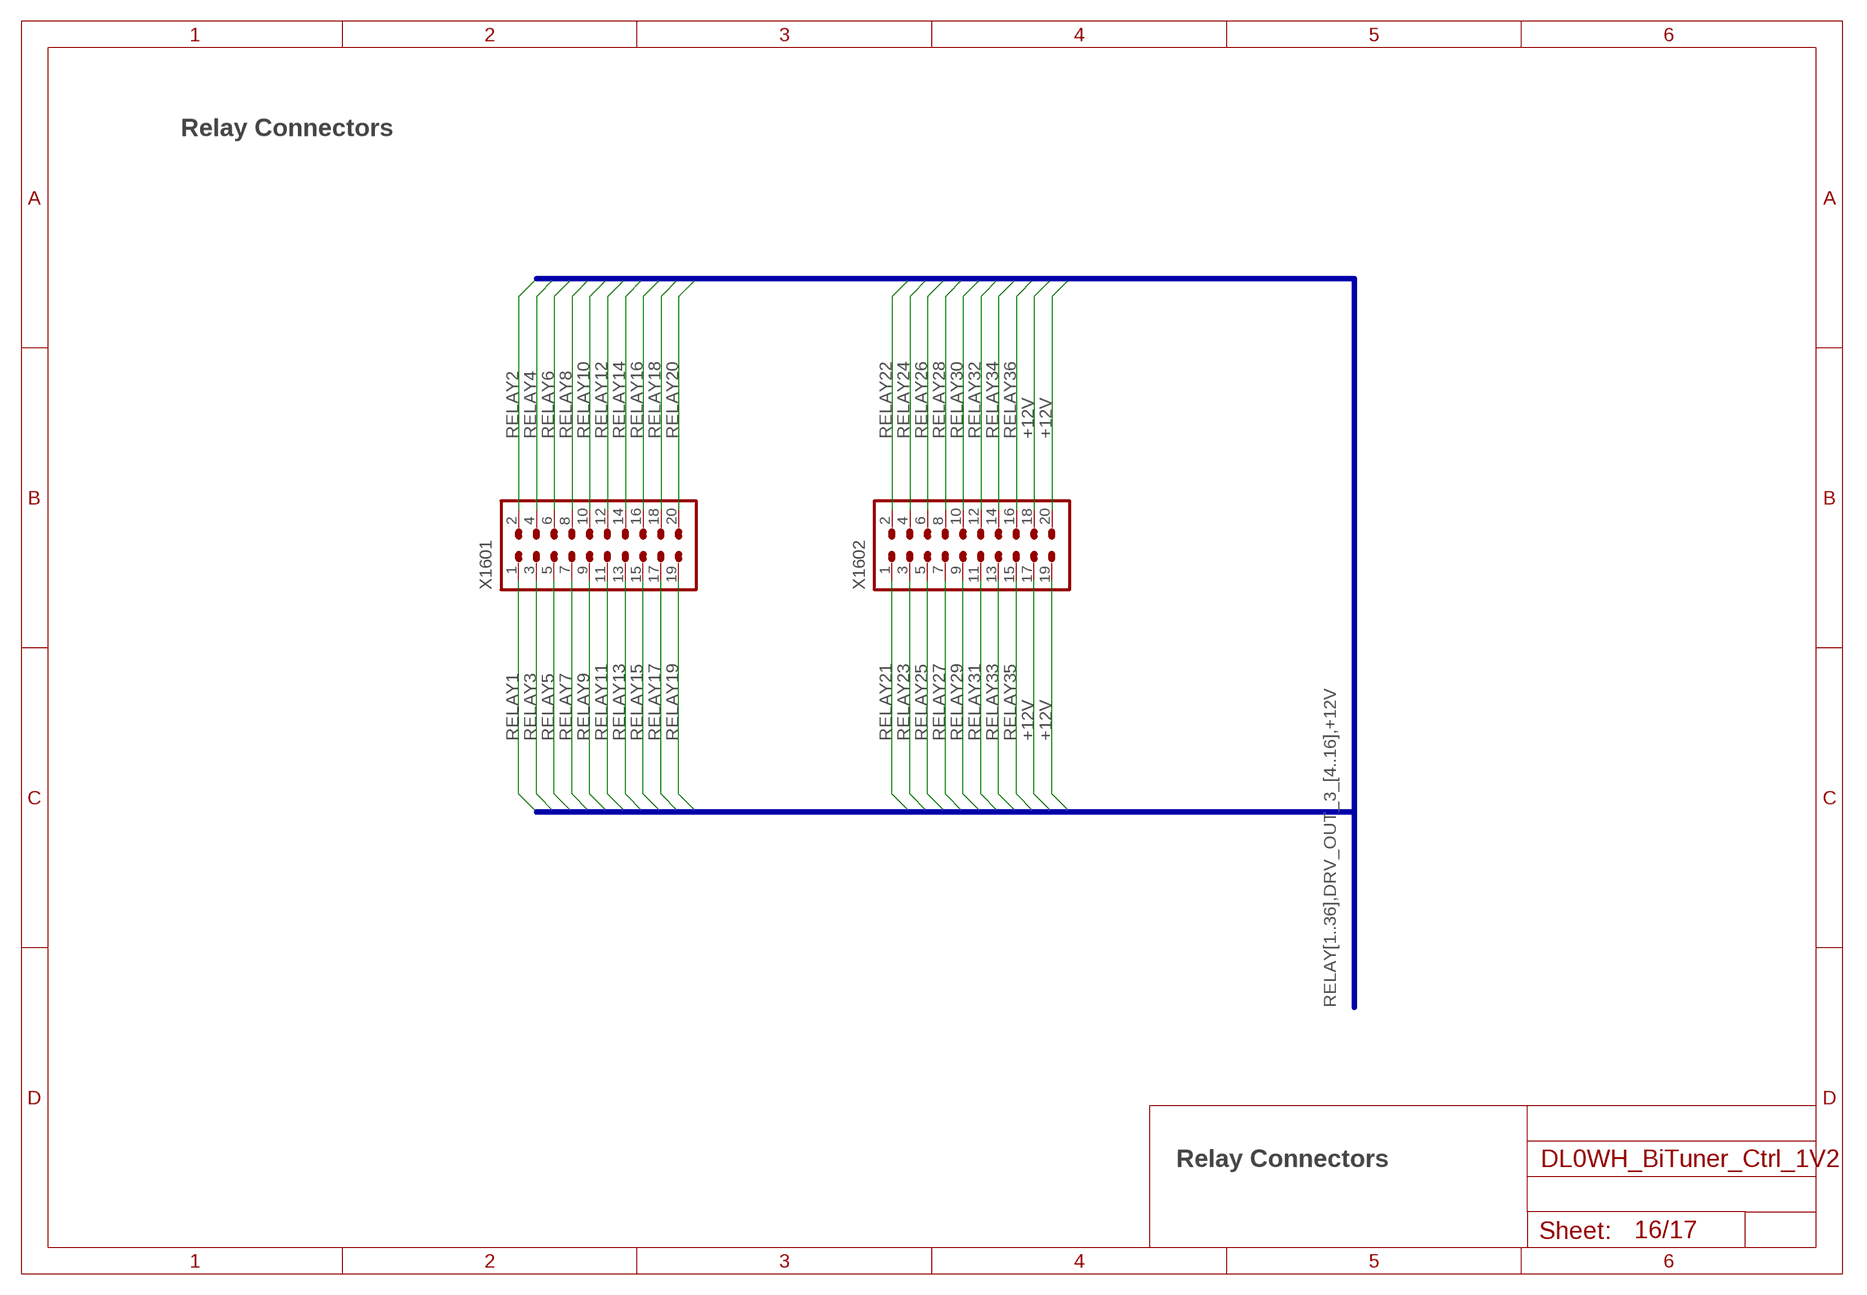
[diagram p15: schematic, sheet 16]
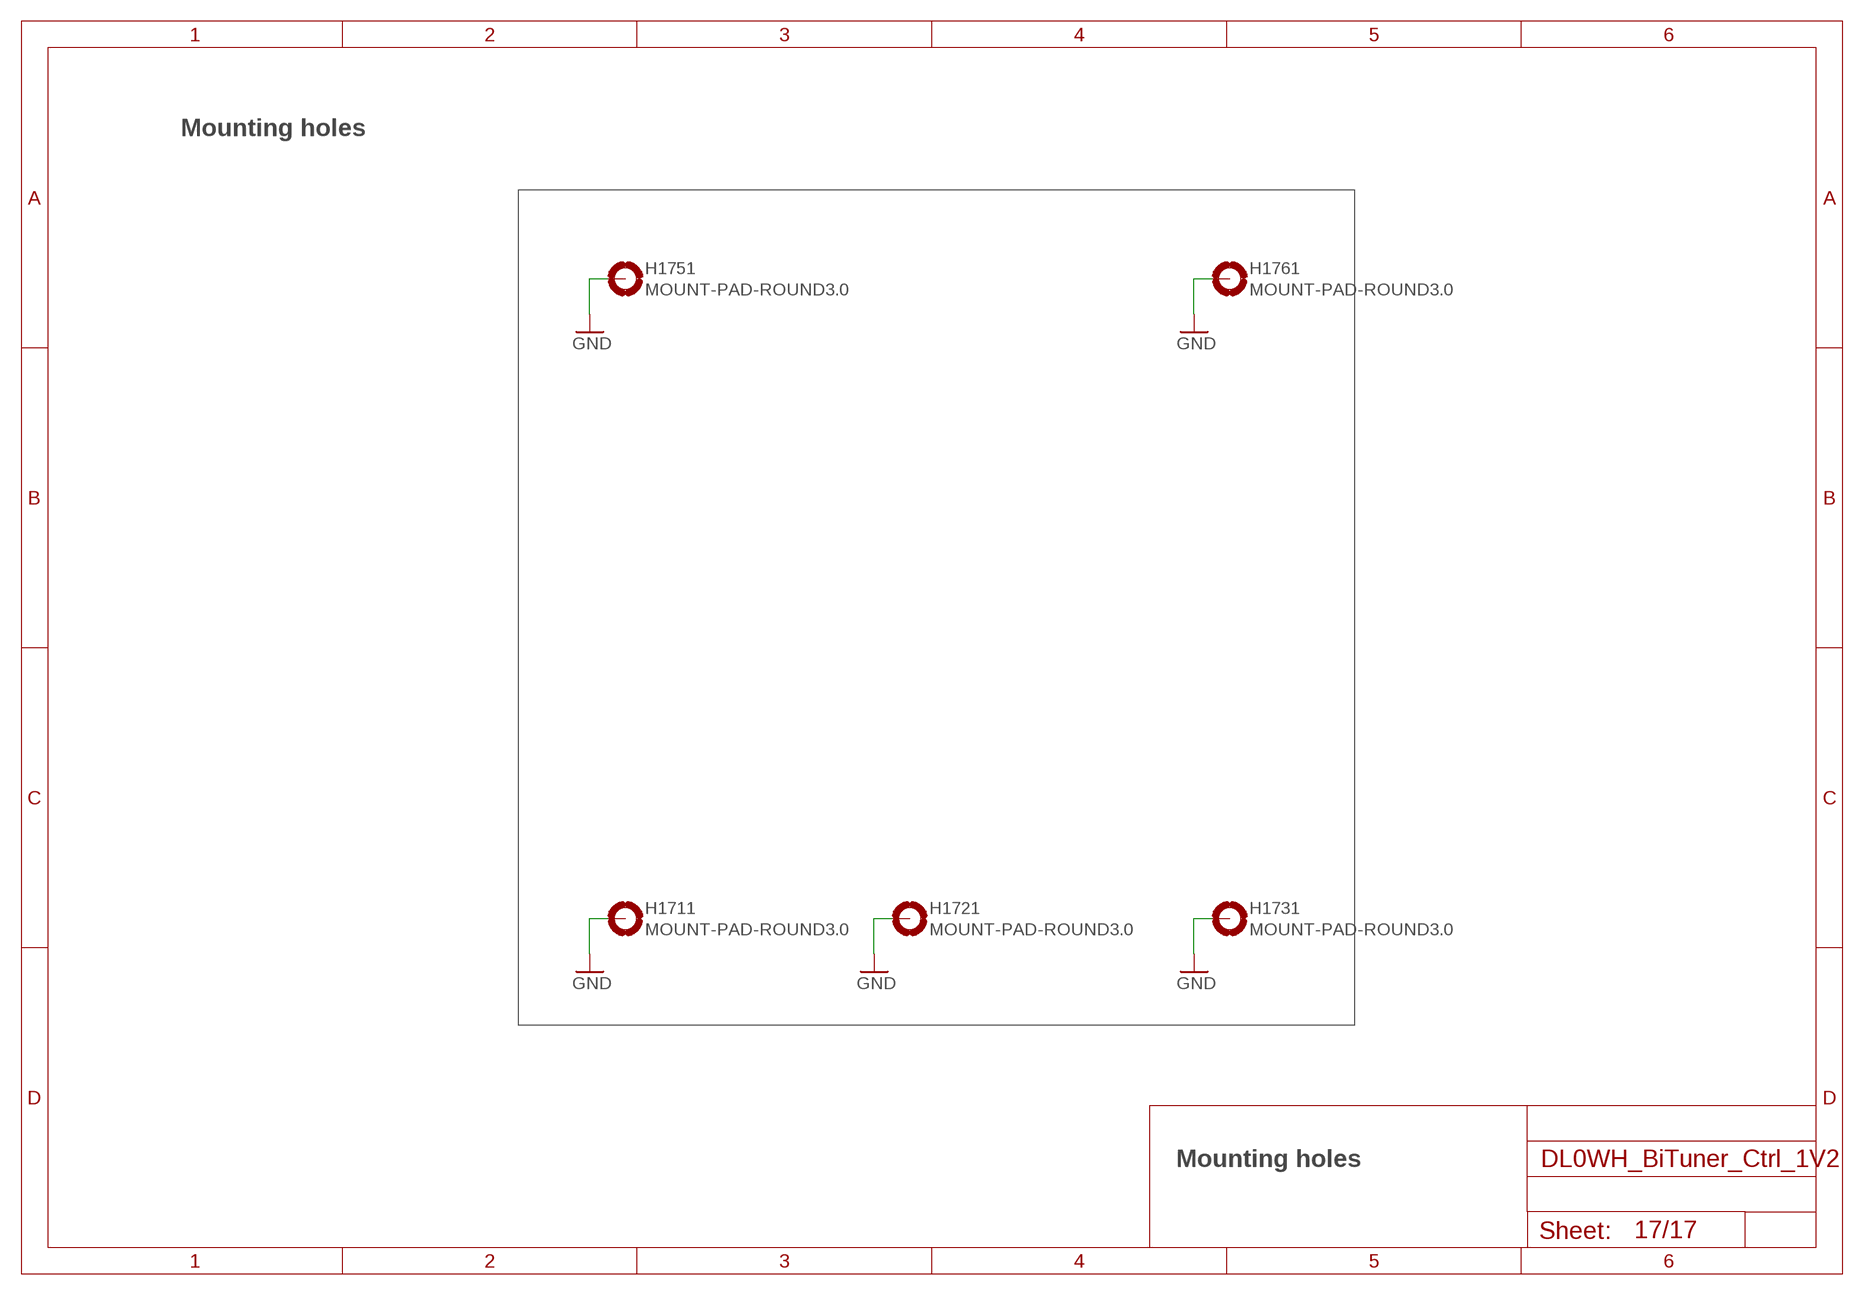
[diagram p16: schematic, sheet 17]

(export (version "E")
  (design (tool "Eeschema 10.0.6"))
  (components
    (comp (ref "C0401")
      (value "100nF")
      (footprint "eagle-import:C0402")
      (libsource (lib "eagle-import") (part "C-EUC0402"))
    )
    (comp (ref "C0402")
      (value "100nF")
      (footprint "eagle-import:C0402")
      (libsource (lib "eagle-import") (part "C-EUC0402"))
    )
    (comp (ref "C0403")
      (value "100nF")
      (footprint "eagle-import:C0402")
      (libsource (lib "eagle-import") (part "C-EUC0402"))
    )
    (comp (ref "C0410")
      (value "4.7uF")
      (footprint "eagle-import:C0603")
      (libsource (lib "eagle-import") (part "C-EUC0603"))
    )
    (comp (ref "C0412")
      (value "10nF")
      (footprint "eagle-import:C0402")
      (libsource (lib "eagle-import") (part "C-EUC0402"))
    )
    (comp (ref "C0413")
      (value "1uF")
      (footprint "eagle-import:C0402")
      (libsource (lib "eagle-import") (part "C-EUC0402"))
    )
    (comp (ref "C0451")
      (value "47uF")
      (footprint "eagle-import:C0805")
      (libsource (lib "eagle-import") (part "C-EUC0805"))
    )
    (comp (ref "L0411")
      (value "10uH")
      (footprint "eagle-import:L0603")
      (libsource (lib "eagle-import") (part "L-EUL0603"))
    )
    (comp (ref "R0441")
      (value "0R")
      (footprint "eagle-import:R0402")
      (libsource (lib "eagle-import") (part "R-EU_R0402"))
    )
    (comp (ref "SJ0401")
      (value "SJ")
      (footprint "eagle-import:SJ")
      (libsource (lib "eagle-import") (part "SJ"))
    )
    (comp (ref "TP_VBAT")
      (value "PTR1B1,27")
      (footprint "eagle-import:B1,27")
      (libsource (lib "eagle-import") (part "PTR1B1,27"))
    )
    (comp (ref "C1201")
      (value "10uF")
      (footprint "eagle-import:C0603")
      (libsource (lib "eagle-import") (part "C-EUC0603"))
    )
    (comp (ref "C1202")
      (value "10uF")
      (footprint "eagle-import:C0603")
      (libsource (lib "eagle-import") (part "C-EUC0603"))
    )
    (comp (ref "C1203")
      (value "10uF")
      (footprint "eagle-import:C0603")
      (libsource (lib "eagle-import") (part "C-EUC0603"))
    )
    (comp (ref "C1204")
      (value "10nF")
      (footprint "eagle-import:C0402")
      (libsource (lib "eagle-import") (part "C-EUC0402"))
    )
    (comp (ref "C1205")
      (value "3.3uF")
      (footprint "eagle-import:C0603")
      (libsource (lib "eagle-import") (part "C-EUC0603"))
    )
    (comp (ref "C1211")
      (value "0.47uF")
      (footprint "eagle-import:C0402")
      (libsource (lib "eagle-import") (part "C-EUC0402"))
    )
    (comp (ref "C1212")
      (value "100nF")
      (footprint "eagle-import:C0402")
      (libsource (lib "eagle-import") (part "C-EUC0402"))
    )
    (comp (ref "C1221")
      (value "22uF")
      (footprint "eagle-import:C0603")
      (libsource (lib "eagle-import") (part "C-EUC0603"))
    )
    (comp (ref "C1222")
      (value "22uF")
      (footprint "eagle-import:C0603")
      (libsource (lib "eagle-import") (part "C-EUC0603"))
    )
    (comp (ref "C1223")
      (value "22uF")
      (footprint "eagle-import:C0603")
      (libsource (lib "eagle-import") (part "C-EUC0603"))
    )
    (comp (ref "D1221")
      (value "CRS08")
      (footprint "eagle-import:SOD80C")
      (libsource (lib "eagle-import") (part "CRS08"))
    )
    (comp (ref "L1211")
      (value "2.2uH")
      (footprint "eagle-import:L_6.00MM_X_6.00MM")
      (libsource (lib "eagle-import") (part "L-EU6.00X6.00MM"))
    )
    (comp (ref "R1211")
      (value "3R")
      (footprint "eagle-import:R0402")
      (libsource (lib "eagle-import") (part "R-EU_R0402"))
    )
    (comp (ref "U1201")
      (value "LM53603-Q1")
      (footprint "eagle-import:HTSSOP16")
      (libsource (lib "eagle-import") (part "LM53603-Q1"))
    )
    (comp (ref "X1211")
      (value "WIRE-TO-BOARD_5MM08_1X02")
      (footprint "eagle-import:WIRE-TO-BOARD_5MM08_1X02")
      (libsource (lib "eagle-import") (part "WIRE-TO-BOARD_5MM08_1X02"))
    )
    (comp (ref "C0213")
      (value "100nF")
      (footprint "eagle-import:C0402")
      (libsource (lib "eagle-import") (part "C-EUC0402"))
    )
    (comp (ref "R0221")
      (value "33kR")
      (footprint "eagle-import:R0402")
      (libsource (lib "eagle-import") (part "R-EU_R0402"))
    )
    (comp (ref "R0231")
      (value "220kR")
      (footprint "eagle-import:R0402")
      (libsource (lib "eagle-import") (part "R-EU_R0402"))
    )
    (comp (ref "R0232")
      (value "220kR")
      (footprint "eagle-import:R0402")
      (libsource (lib "eagle-import") (part "R-EU_R0402"))
    )
    (comp (ref "S0212")
      (value "KSR223GLFG")
      (footprint "eagle-import:KSR223G_SMD_1POL")
      (libsource (lib "eagle-import") (part "KSR223G_SMD_1POL"))
    )
    (comp (ref "X0201")
      (value "FTSH-105-01-F-D-K")
      (footprint "eagle-import:2X05_1MM27_SHROUDED_CORTEX_JTAG_SWD")
      (libsource (lib "eagle-import") (part "2X05_1MM27_SHROUDED_CORTEX_JTAG_SWD{dblquote}"))
    )
    (comp (ref "X0222")
      (value "HEADER-1X2")
      (footprint "eagle-import:1X02")
      (libsource (lib "eagle-import") (part "HEADER-1X2"))
    )
    (comp (ref "C0801")
      (value "100nF")
      (footprint "eagle-import:C0402")
      (libsource (lib "eagle-import") (part "C-EUC0402"))
    )
    (comp (ref "C0802")
      (value "100nF")
      (footprint "eagle-import:C0402")
      (libsource (lib "eagle-import") (part "C-EUC0402"))
    )
    (comp (ref "C0803")
      (value "22uF")
      (footprint "eagle-import:C0603")
      (libsource (lib "eagle-import") (part "C-EUC0603"))
    )
    (comp (ref "R0811")
      (value "47R")
      (footprint "eagle-import:R0402")
      (libsource (lib "eagle-import") (part "R-EU_R0402"))
    )
    (comp (ref "R0824")
      (value "47R")
      (footprint "eagle-import:R0402")
      (libsource (lib "eagle-import") (part "R-EU_R0402"))
    )
    (comp (ref "U0801")
      (value "MC33996")
      (footprint "eagle-import:SOICW32")
      (libsource (lib "eagle-import") (part "MC33996"))
    )
    (comp (ref "C1301")
      (value "22uF")
      (footprint "eagle-import:C0603")
      (libsource (lib "eagle-import") (part "C-EUC0603"))
    )
    (comp (ref "C1311")
      (value "22uF")
      (footprint "eagle-import:C0603")
      (libsource (lib "eagle-import") (part "C-EUC0603"))
    )
    (comp (ref "L1311")
      (value "10uH")
      (footprint "eagle-import:L_4.50MM_X_3.20MM")
      (libsource (lib "eagle-import") (part "L-EU4.50X3.20MM"))
    )
    (comp (ref "R1301")
      (value "100kR")
      (footprint "eagle-import:R0402")
      (libsource (lib "eagle-import") (part "R-EU_R0402"))
    )
    (comp (ref "R1302")
      (value "220kR")
      (footprint "eagle-import:R0402")
      (libsource (lib "eagle-import") (part "R-EU_R0402"))
    )
    (comp (ref "R1321")
      (value "1MR")
      (footprint "eagle-import:R0402")
      (libsource (lib "eagle-import") (part "R-EU_R0402"))
    )
    (comp (ref "R1322")
      (value "1MR")
      (footprint "eagle-import:R0402")
      (libsource (lib "eagle-import") (part "R-EU_R0402"))
    )
    (comp (ref "U1301")
      (value "TPS62056")
      (footprint "eagle-import:S-PDSO-G10")
      (libsource (lib "eagle-import") (part "TPS62051"))
    )
    (comp (ref "X1601")
      (value "2X10_2MM56_SOCKET")
      (footprint "eagle-import:2X10")
      (libsource (lib "eagle-import") (part "2X10_2MM56_SOCKET"))
    )
    (comp (ref "X1602")
      (value "2X10_2MM56_SOCKET")
      (footprint "eagle-import:2X10")
      (libsource (lib "eagle-import") (part "2X10_2MM56_SOCKET"))
    )
    (comp (ref "C0901")
      (value "N/A")
      (footprint "eagle-import:C0402")
      (libsource (lib "eagle-import") (part "C-EUC0402"))
    )
    (comp (ref "C0911")
      (value "N/A")
      (footprint "eagle-import:C0402")
      (libsource (lib "eagle-import") (part "C-EUC0402"))
    )
    (comp (ref "C0921")
      (value "100nF")
      (footprint "eagle-import:C0402")
      (libsource (lib "eagle-import") (part "C-EUC0402"))
    )
    (comp (ref "C0941")
      (value "22uF")
      (footprint "eagle-import:C0603")
      (libsource (lib "eagle-import") (part "C-EUC0603"))
    )
    (comp (ref "C0942")
      (value "2.2uF")
      (footprint "eagle-import:C0805")
      (libsource (lib "eagle-import") (part "C-EUC0805"))
    )
    (comp (ref "C0943")
      (value "22uF")
      (footprint "eagle-import:C0603")
      (libsource (lib "eagle-import") (part "C-EUC0603"))
    )
    (comp (ref "C0945")
      (value "1nF")
      (footprint "eagle-import:C0402")
      (libsource (lib "eagle-import") (part "C-EUC0402"))
    )
    (comp (ref "C0951")
      (value "100nF")
      (footprint "eagle-import:C0402")
      (libsource (lib "eagle-import") (part "C-EUC0402"))
    )
    (comp (ref "C0952")
      (value "100nF")
      (footprint "eagle-import:C0402")
      (libsource (lib "eagle-import") (part "C-EUC0402"))
    )
    (comp (ref "C0962")
      (value "100nF")
      (footprint "eagle-import:C0402")
      (libsource (lib "eagle-import") (part "C-EUC0402"))
    )
    (comp (ref "C0963")
      (value "100pF")
      (footprint "eagle-import:C0402")
      (libsource (lib "eagle-import") (part "C-EUC0402"))
    )
    (comp (ref "D0942")
      (value "CRS08")
      (footprint "eagle-import:SOD80C")
      (libsource (lib "eagle-import") (part "CRS08"))
    )
    (comp (ref "D0951")
      (value "CMAD6001")
      (footprint "eagle-import:SOD923")
      (libsource (lib "eagle-import") (part "D_SOD923"))
    )
    (comp (ref "D0971")
      (value "CMAD6001")
      (footprint "eagle-import:SOD923")
      (libsource (lib "eagle-import") (part "D_SOD923"))
    )
    (comp (ref "L0901")
      (value "2kR")
      (footprint "eagle-import:L0603")
      (libsource (lib "eagle-import") (part "L-EUL0603"))
    )
    (comp (ref "L0911")
      (value "2kR")
      (footprint "eagle-import:L0603")
      (libsource (lib "eagle-import") (part "L-EUL0603"))
    )
    (comp (ref "L0941")
      (value "20uH")
      (footprint "eagle-import:L1812")
      (libsource (lib "eagle-import") (part "L-EUL1812"))
    )
    (comp (ref "L0943")
      (value "20uH")
      (footprint "eagle-import:L1812")
      (libsource (lib "eagle-import") (part "L-EUL1812"))
    )
    (comp (ref "R0901")
      (value "1kR")
      (footprint "eagle-import:R0402")
      (libsource (lib "eagle-import") (part "R-EU_R0402"))
    )
    (comp (ref "R0902")
      (value "15kR")
      (footprint "eagle-import:R0402")
      (libsource (lib "eagle-import") (part "R-EU_R0402"))
    )
    (comp (ref "R0903")
      (value "150kR")
      (footprint "eagle-import:R0402")
      (libsource (lib "eagle-import") (part "R-EU_R0402"))
    )
    (comp (ref "R0911")
      (value "1kR")
      (footprint "eagle-import:R0402")
      (libsource (lib "eagle-import") (part "R-EU_R0402"))
    )
    (comp (ref "R0912")
      (value "15kR")
      (footprint "eagle-import:R0402")
      (libsource (lib "eagle-import") (part "R-EU_R0402"))
    )
    (comp (ref "R0913")
      (value "150kR")
      (footprint "eagle-import:R0402")
      (libsource (lib "eagle-import") (part "R-EU_R0402"))
    )
    (comp (ref "R0921")
      (value "47R")
      (footprint "eagle-import:R0402")
      (libsource (lib "eagle-import") (part "R-EU_R0402"))
    )
    (comp (ref "R0922")
      (value "47R")
      (footprint "eagle-import:R0402")
      (libsource (lib "eagle-import") (part "R-EU_R0402"))
    )
    (comp (ref "R0945")
      (value "8.2kR")
      (footprint "eagle-import:R0402")
      (libsource (lib "eagle-import") (part "R-EU_R0402"))
    )
    (comp (ref "R0946")
      (value "33kR")
      (footprint "eagle-import:R0402")
      (libsource (lib "eagle-import") (part "R-EU_R0402"))
    )
    (comp (ref "R0961")
      (value "1kR")
      (footprint "eagle-import:R0402")
      (libsource (lib "eagle-import") (part "R-EU_R0402"))
    )
    (comp (ref "R0962")
      (value "1kR")
      (footprint "eagle-import:R0402")
      (libsource (lib "eagle-import") (part "R-EU_R0402"))
    )
    (comp (ref "R0963")
      (value "20kR")
      (footprint "eagle-import:R0402")
      (libsource (lib "eagle-import") (part "R-EU_R0402"))
    )
    (comp (ref "R0971")
      (value "10kR")
      (footprint "eagle-import:R0402")
      (libsource (lib "eagle-import") (part "R-EU_R0402"))
    )
    (comp (ref "R0972")
      (value "47R")
      (footprint "eagle-import:R0402")
      (libsource (lib "eagle-import") (part "R-EU_R0402"))
    )
    (comp (ref "U0921")
      (value "TS5A23166")
      (footprint "eagle-import:R-PDSO-G8")
      (libsource (lib "eagle-import") (part "TS5A23166"))
    )
    (comp (ref "U0941")
      (value "LM2611")
      (footprint "eagle-import:SOT95P280X145-5N")
      (libsource (lib "eagle-import") (part "LM2611"))
    )
    (comp (ref "U0951")
      (value "OPA354")
      (footprint "eagle-import:SOT-23-5")
      (fields (field (name "MPN") "OPA354AIDBVT"))
      (libsource (lib "eagle-import") (part "OPA354"))
    )
    (comp (ref "U0961")
      (value "OPA354")
      (footprint "eagle-import:SOT-23-5")
      (fields (field (name "MPN") "OPA354AIDBVT"))
      (libsource (lib "eagle-import") (part "OPA354"))
    )
    (comp (ref "U0962")
      (value "MCP4661-103E-MS")
      (footprint "eagle-import:TSSOP14")
      (libsource (lib "eagle-import") (part "MCP4661-104E-MS"))
    )
    (comp (ref "C1403")
      (value "1nF")
      (footprint "eagle-import:C0402")
      (libsource (lib "eagle-import") (part "C-EUC0402"))
    )
    (comp (ref "PF1411")
      (value "1.1A/2.2A")
      (footprint "eagle-import:M1206")
      (libsource (lib "eagle-import") (part "rcl_R-EU_M1206"))
    )
    (comp (ref "R1402")
      (value "330kR")
      (footprint "eagle-import:R0402")
      (libsource (lib "eagle-import") (part "R-EU_R0402"))
    )
    (comp (ref "X1401")
      (value "MOLEX 105017-0001")
      (footprint "eagle-import:USB-B-MICRO-SMD_MOLEX-105017-0001")
      (libsource (lib "eagle-import") (part "USB_MICRO-B_MOLEX"))
    )
    (comp (ref "C0311")
      (value "22pF")
      (footprint "eagle-import:C0402")
      (libsource (lib "eagle-import") (part "C-EUC0402"))
    )
    (comp (ref "C0331")
      (value "JR200")
      (footprint "eagle-import:3MM2_X_2MM5")
      (libsource (lib "eagle-import") (part "C-TRIMM3MM2_2MM5"))
    )
    (comp (ref "C0332")
      (value "18pF")
      (footprint "eagle-import:C0402")
      (libsource (lib "eagle-import") (part "C-EUC0402"))
    )
    (comp (ref "Q0321")
      (value "ABS07-32.768KHZ")
      (footprint "eagle-import:ABS07")
      (fields (field (name "MANUFACTURER") "ABS07-32.768KHZ-1-T"))
      (libsource (lib "eagle-import") (part "ABS07-32.768KHZ"))
    )
    (comp (ref "C0701")
      (value "100nF")
      (footprint "eagle-import:C0402")
      (libsource (lib "eagle-import") (part "C-EUC0402"))
    )
    (comp (ref "C0702")
      (value "100nF")
      (footprint "eagle-import:C0402")
      (libsource (lib "eagle-import") (part "C-EUC0402"))
    )
    (comp (ref "C0703")
      (value "22uF")
      (footprint "eagle-import:C0603")
      (libsource (lib "eagle-import") (part "C-EUC0603"))
    )
    (comp (ref "R0711")
      (value "47R")
      (footprint "eagle-import:R0402")
      (libsource (lib "eagle-import") (part "R-EU_R0402"))
    )
    (comp (ref "R0724")
      (value "47R")
      (footprint "eagle-import:R0402")
      (libsource (lib "eagle-import") (part "R-EU_R0402"))
    )
    (comp (ref "U0701")
      (value "MC33996")
      (footprint "eagle-import:SOICW32")
      (libsource (lib "eagle-import") (part "MC33996"))
    )
    (comp (ref "R0511")
      (value "1kR")
      (footprint "eagle-import:R0402")
      (libsource (lib "eagle-import") (part "R-EU_R0402"))
    )
    (comp (ref "R0512")
      (value "1kR")
      (footprint "eagle-import:R0402")
      (libsource (lib "eagle-import") (part "R-EU_R0402"))
    )
    (comp (ref "X0601")
      (value "HEADER-2X2")
      (footprint "eagle-import:2X02")
      (libsource (lib "eagle-import") (part "HEADER-2X2"))
    )
    (comp (ref "C0601")
      (value "100nF")
      (footprint "eagle-import:C0402")
      (libsource (lib "eagle-import") (part "C-EUC0402"))
    )
    (comp (ref "C0602")
      (value "100nF")
      (footprint "eagle-import:C0402")
      (libsource (lib "eagle-import") (part "C-EUC0402"))
    )
    (comp (ref "C0603")
      (value "22uF")
      (footprint "eagle-import:C0603")
      (libsource (lib "eagle-import") (part "C-EUC0603"))
    )
    (comp (ref "R0611")
      (value "47R")
      (footprint "eagle-import:R0402")
      (libsource (lib "eagle-import") (part "R-EU_R0402"))
    )
    (comp (ref "R0621")
      (value "47R")
      (footprint "eagle-import:R0402")
      (libsource (lib "eagle-import") (part "R-EU_R0402"))
    )
    (comp (ref "R0622")
      (value "0R")
      (footprint "eagle-import:R0402")
      (libsource (lib "eagle-import") (part "R-EU_R0402"))
    )
    (comp (ref "R0623")
      (value "47R")
      (footprint "eagle-import:R0402")
      (libsource (lib "eagle-import") (part "R-EU_R0402"))
    )
    (comp (ref "R0624")
      (value "47R")
      (footprint "eagle-import:R0402")
      (libsource (lib "eagle-import") (part "R-EU_R0402"))
    )
    (comp (ref "R0625")
      (value "47R")
      (footprint "eagle-import:R0402")
      (libsource (lib "eagle-import") (part "R-EU_R0402"))
    )
    (comp (ref "R0626")
      (value "47R")
      (footprint "eagle-import:R0402")
      (libsource (lib "eagle-import") (part "R-EU_R0402"))
    )
    (comp (ref "U0601")
      (value "MC33996")
      (footprint "eagle-import:SOICW32")
      (libsource (lib "eagle-import") (part "MC33996"))
    )
    (comp (ref "U0101")
      (value "STM32L476RXT_64PIN_LDO")
      (footprint "eagle-import:LQFP64")
      (libsource (lib "eagle-import") (part "STM32L476RXT_64PIN_LDO"))
    )
    (comp (ref "C1101")
      (value "1uF")
      (footprint "eagle-import:C0402")
      (libsource (lib "eagle-import") (part "C-EUC0402"))
    )
    (comp (ref "C1102")
      (value "1uF")
      (footprint "eagle-import:C0402")
      (libsource (lib "eagle-import") (part "C-EUC0402"))
    )
    (comp (ref "C1103")
      (value "1uF")
      (footprint "eagle-import:C0402")
      (libsource (lib "eagle-import") (part "C-EUC0402"))
    )
    (comp (ref "C1104")
      (value "1uF")
      (footprint "eagle-import:C0402")
      (libsource (lib "eagle-import") (part "C-EUC0402"))
    )
    (comp (ref "C1105")
      (value "1uF")
      (footprint "eagle-import:C0402")
      (libsource (lib "eagle-import") (part "C-EUC0402"))
    )
    (comp (ref "C1151")
      (value "10nF")
      (footprint "eagle-import:C0603")
      (libsource (lib "eagle-import") (part "C-EUC0603"))
    )
    (comp (ref "C1152")
      (value "10nF")
      (footprint "eagle-import:C0603")
      (libsource (lib "eagle-import") (part "C-EUC0603"))
    )
    (comp (ref "C1153")
      (value "10nF")
      (footprint "eagle-import:C0603")
      (libsource (lib "eagle-import") (part "C-EUC0603"))
    )
    (comp (ref "C1154")
      (value "10nF")
      (footprint "eagle-import:C0603")
      (libsource (lib "eagle-import") (part "C-EUC0603"))
    )
    (comp (ref "R1101")
      (value "47R")
      (footprint "eagle-import:R0402")
      (libsource (lib "eagle-import") (part "R-EU_R0402"))
    )
    (comp (ref "R1102")
      (value "47R")
      (footprint "eagle-import:R0402")
      (libsource (lib "eagle-import") (part "R-EU_R0402"))
    )
    (comp (ref "R1103")
      (value "47R")
      (footprint "eagle-import:R0402")
      (libsource (lib "eagle-import") (part "R-EU_R0402"))
    )
    (comp (ref "R1104")
      (value "47R")
      (footprint "eagle-import:R0402")
      (libsource (lib "eagle-import") (part "R-EU_R0402"))
    )
    (comp (ref "U1101")
      (value "MAX232_SOIC16")
      (footprint "eagle-import:SOIC16N")
      (fields (field (name "MF") "MAXIM") (field (name "MPN") "MAX232ECDR"))
      (libsource (lib "eagle-import") (part "MAX232_SOIC16"))
    )
    (comp (ref "X1151")
      (value "WIRE-TO-BOARD_5MM08_1X02")
      (footprint "eagle-import:WIRE-TO-BOARD_5MM08_1X02")
      (libsource (lib "eagle-import") (part "WIRE-TO-BOARD_5MM08_1X02"))
    )
    (comp (ref "X1152")
      (value "WIRE-TO-BOARD_5MM08_1X02")
      (footprint "eagle-import:WIRE-TO-BOARD_5MM08_1X02")
      (libsource (lib "eagle-import") (part "WIRE-TO-BOARD_5MM08_1X02"))
    )
    (comp (ref "X1153")
      (value "WIRE-TO-BOARD_5MM08_1X02")
      (footprint "eagle-import:WIRE-TO-BOARD_5MM08_1X02")
      (libsource (lib "eagle-import") (part "WIRE-TO-BOARD_5MM08_1X02"))
    )
    (comp (ref "H1711")
      (value "MOUNT-PAD-ROUND3.0")
      (footprint "eagle-import:3,0-PAD")
      (libsource (lib "eagle-import") (part "MOUNT-PAD-ROUND3.0"))
    )
    (comp (ref "H1721")
      (value "MOUNT-PAD-ROUND3.0")
      (footprint "eagle-import:3,0-PAD")
      (libsource (lib "eagle-import") (part "MOUNT-PAD-ROUND3.0"))
    )
    (comp (ref "H1731")
      (value "MOUNT-PAD-ROUND3.0")
      (footprint "eagle-import:3,0-PAD")
      (libsource (lib "eagle-import") (part "MOUNT-PAD-ROUND3.0"))
    )
    (comp (ref "H1751")
      (value "MOUNT-PAD-ROUND3.0")
      (footprint "eagle-import:3,0-PAD")
      (libsource (lib "eagle-import") (part "MOUNT-PAD-ROUND3.0"))
    )
    (comp (ref "H1761")
      (value "MOUNT-PAD-ROUND3.0")
      (footprint "eagle-import:3,0-PAD")
      (libsource (lib "eagle-import") (part "MOUNT-PAD-ROUND3.0"))
    )
    (comp (ref "C0054")
      (value "10nF")
      (footprint "eagle-import:C0603")
      (libsource (lib "eagle-import") (part "C-EUC0603"))
    )
    (comp (ref "C1001")
      (value "1uF")
      (footprint "eagle-import:C0402")
      (libsource (lib "eagle-import") (part "C-EUC0402"))
    )
    (comp (ref "C1002")
      (value "1uF")
      (footprint "eagle-import:C0402")
      (libsource (lib "eagle-import") (part "C-EUC0402"))
    )
    (comp (ref "C1003")
      (value "1uF")
      (footprint "eagle-import:C0402")
      (libsource (lib "eagle-import") (part "C-EUC0402"))
    )
    (comp (ref "C1004")
      (value "1uF")
      (footprint "eagle-import:C0402")
      (libsource (lib "eagle-import") (part "C-EUC0402"))
    )
    (comp (ref "C1005")
      (value "1uF")
      (footprint "eagle-import:C0402")
      (libsource (lib "eagle-import") (part "C-EUC0402"))
    )
    (comp (ref "C1051")
      (value "10nF")
      (footprint "eagle-import:C0603")
      (libsource (lib "eagle-import") (part "C-EUC0603"))
    )
    (comp (ref "C1052")
      (value "10nF")
      (footprint "eagle-import:C0603")
      (libsource (lib "eagle-import") (part "C-EUC0603"))
    )
    (comp (ref "C1053")
      (value "10nF")
      (footprint "eagle-import:C0603")
      (libsource (lib "eagle-import") (part "C-EUC0603"))
    )
    (comp (ref "R1001")
      (value "47R")
      (footprint "eagle-import:R0402")
      (libsource (lib "eagle-import") (part "R-EU_R0402"))
    )
    (comp (ref "R1002")
      (value "47R")
      (footprint "eagle-import:R0402")
      (libsource (lib "eagle-import") (part "R-EU_R0402"))
    )
    (comp (ref "R1003")
      (value "47R")
      (footprint "eagle-import:R0402")
      (libsource (lib "eagle-import") (part "R-EU_R0402"))
    )
    (comp (ref "R1004")
      (value "47R")
      (footprint "eagle-import:R0402")
      (libsource (lib "eagle-import") (part "R-EU_R0402"))
    )
    (comp (ref "U1001")
      (value "MAX232_SOIC16")
      (footprint "eagle-import:SOIC16N")
      (fields (field (name "MF") "MAXIM") (field (name "MPN") "MAX232ECDR"))
      (libsource (lib "eagle-import") (part "MAX232_SOIC16"))
    )
    (comp (ref "X1051")
      (value "WIRE-TO-BOARD_5MM08_1X02")
      (footprint "eagle-import:WIRE-TO-BOARD_5MM08_1X02")
      (libsource (lib "eagle-import") (part "WIRE-TO-BOARD_5MM08_1X02"))
    )
    (comp (ref "X1052")
      (value "WIRE-TO-BOARD_5MM08_1X02")
      (footprint "eagle-import:WIRE-TO-BOARD_5MM08_1X02")
      (libsource (lib "eagle-import") (part "WIRE-TO-BOARD_5MM08_1X02"))
    )
    (comp (ref "X1053")
      (value "WIRE-TO-BOARD_5MM08_1X02")
      (footprint "eagle-import:WIRE-TO-BOARD_5MM08_1X02")
      (libsource (lib "eagle-import") (part "WIRE-TO-BOARD_5MM08_1X02"))
    )
    (comp (ref "X1501")
      (value "SMA_SMT_AMPHENOL-901-143")
      (footprint "eagle-import:SMA_SMT_AMPHENOL_901-143")
      (fields (field (name "MPN") "901-143"))
      (libsource (lib "eagle-import") (part "SMA_SMT_AMPHENOL-901-143"))
    )
    (comp (ref "X1511")
      (value "SAMTEC SMA-J-P-H-RA-TH1")
      (footprint "eagle-import:SMA_SMT_AMPHENOL_901-143")
      (fields (field (name "MPN") "901-143"))
      (libsource (lib "eagle-import") (part "SMA_SMT_AMPHENOL-901-143"))
    )
  )
  (nets
    (net (code "26") (name "+3V3") (class "Default")
      (node (ref "C0601") (pin "2") (pinfunction "2_2") (pintype "passive"))
      (node (ref "C0701") (pin "2") (pinfunction "2_2") (pintype "passive"))
      (node (ref "C0801") (pin "2") (pinfunction "2_2") (pintype "passive"))
      (node (ref "C0921") (pin "1") (pinfunction "1_1") (pintype "passive"))
      (node (ref "C0941") (pin "1") (pinfunction "1_1") (pintype "passive"))
      (node (ref "C0951") (pin "1") (pinfunction "1_1") (pintype "passive"))
      (node (ref "C0962") (pin "1") (pinfunction "1_1") (pintype "passive"))
      (node (ref "C1311") (pin "1") (pinfunction "1_1") (pintype "passive"))
      (node (ref "L0941") (pin "2") (pinfunction "2_2") (pintype "passive"))
      (node (ref "L1311") (pin "1") (pinfunction "1_1") (pintype "passive"))
      (node (ref "L1311") (pin "3") (pinfunction "1_3") (pintype "passive"))
      (node (ref "R0231") (pin "2") (pinfunction "2_2") (pintype "passive"))
      (node (ref "R0511") (pin "2") (pinfunction "2_2") (pintype "passive"))
      (node (ref "R0512") (pin "2") (pinfunction "2_2") (pintype "passive"))
      (node (ref "R0903") (pin "2") (pinfunction "2_2") (pintype "passive"))
      (node (ref "R0913") (pin "2") (pinfunction "2_2") (pintype "passive"))
      (node (ref "R0971") (pin "1") (pinfunction "1_1") (pintype "passive"))
      (node (ref "R1321") (pin "2") (pinfunction "2_2") (pintype "passive"))
      (node (ref "R1322") (pin "2") (pinfunction "2_2") (pintype "passive"))
      (node (ref "SJ0401") (pin "1") (pinfunction "1_1") (pintype "passive"))
      (node (ref "U0601") (pin "3") (pinfunction "SOPWR_3") (pintype "power_in"))
      (node (ref "U0701") (pin "3") (pinfunction "SOPWR_3") (pintype "power_in"))
      (node (ref "U0801") (pin "3") (pinfunction "SOPWR_3") (pintype "power_in"))
      (node (ref "U0921") (pin "8") (pinfunction "8_8") (pintype "power_in"))
      (node (ref "U0941") (pin "4") (pinfunction "~{SHDN}_4") (pintype "input"))
      (node (ref "U0941") (pin "5") (pinfunction "VIN_5") (pintype "power_in"))
      (node (ref "U0951") (pin "5") (pinfunction "V+_5") (pintype "power_in"))
      (node (ref "U0961") (pin "5") (pinfunction "V+_5") (pintype "power_in"))
      (node (ref "U0962") (pin "11") (pinfunction "~{WP}_11") (pintype "input"))
      (node (ref "U0962") (pin "14") (pinfunction "VDD_14") (pintype "power_in"))
      (node (ref "U0962") (pin "8") (pinfunction "P0A_8") (pintype "passive"))
      (node (ref "U1301") (pin "5") (pinfunction "FB_5") (pintype "passive"))
      (node (ref "X0201") (pin "1") (pinfunction "1_1") (pintype "passive"))
      (node (ref "X0222") (pin "1") (pinfunction "1_1") (pintype "passive"))
    )
    (net (code "27") (name "+5V") (class "Default")
      (node (ref "C1001") (pin "1") (pinfunction "1_1") (pintype "passive"))
      (node (ref "C1101") (pin "1") (pinfunction "1_1") (pintype "passive"))
      (node (ref "C1221") (pin "1") (pinfunction "1_1") (pintype "passive"))
      (node (ref "C1222") (pin "1") (pinfunction "1_1") (pintype "passive"))
      (node (ref "C1223") (pin "1") (pinfunction "1_1") (pintype "passive"))
      (node (ref "C1301") (pin "1") (pinfunction "1_1") (pintype "passive"))
      (node (ref "D1221") (pin "C") (pinfunction "C_C") (pintype "passive"))
      (node (ref "L1211") (pin "1") (pinfunction "1_1") (pintype "passive"))
      (node (ref "R1211") (pin "2") (pinfunction "2_2") (pintype "passive"))
      (node (ref "R1302") (pin "2") (pinfunction "2_2") (pintype "passive"))
      (node (ref "U1001") (pin "16") (pinfunction "VCC_16") (pintype "power_in"))
      (node (ref "U1101") (pin "16") (pinfunction "VCC_16") (pintype "power_in"))
      (node (ref "U1201") (pin "9") (pinfunction "FB_9") (pintype "passive"))
      (node (ref "U1301") (pin "1") (pinfunction "VIN_1") (pintype "power_in"))
      (node (ref "U1301") (pin "8") (pinfunction "EN_8") (pintype "input"))
    )
    (net (code "28") (name "+12V") (class "Default")
      (node (ref "C0602") (pin "1") (pinfunction "1_1") (pintype "passive"))
      (node (ref "C0603") (pin "1") (pinfunction "1_1") (pintype "passive"))
      (node (ref "C0702") (pin "1") (pinfunction "1_1") (pintype "passive"))
      (node (ref "C0703") (pin "1") (pinfunction "1_1") (pintype "passive"))
      (node (ref "C0802") (pin "1") (pinfunction "1_1") (pintype "passive"))
      (node (ref "C0803") (pin "1") (pinfunction "1_1") (pintype "passive"))
      (node (ref "C1201") (pin "1") (pinfunction "1_1") (pintype "passive"))
      (node (ref "C1202") (pin "1") (pinfunction "1_1") (pintype "passive"))
      (node (ref "C1203") (pin "1") (pinfunction "1_1") (pintype "passive"))
      (node (ref "C1204") (pin "1") (pinfunction "1_1") (pintype "passive"))
      (node (ref "U0601") (pin "6") (pinfunction "VPWR_6") (pintype "power_in"))
      (node (ref "U0701") (pin "6") (pinfunction "VPWR_6") (pintype "power_in"))
      (node (ref "U0801") (pin "6") (pinfunction "VPWR_6") (pintype "power_in"))
      (node (ref "U1201") (pin "11") (pinfunction "EN_11") (pintype "input"))
      (node (ref "U1201") (pin "12") (pinfunction "VIN_12") (pintype "power_in"))
      (node (ref "U1201") (pin "13") (pinfunction "VIN_13") (pintype "power_in"))
      (node (ref "X1211") (pin "1") (pinfunction "1_1") (pintype "passive"))
      (node (ref "X1602") (pin "17") (pinfunction "17_17") (pintype "passive"))
      (node (ref "X1602") (pin "18") (pinfunction "18_18") (pintype "passive"))
      (node (ref "X1602") (pin "19") (pinfunction "19_19") (pintype "passive"))
      (node (ref "X1602") (pin "20") (pinfunction "20_20") (pintype "passive"))
    )
    (net (code "29") (name "-1V5") (class "Default")
      (node (ref "C0943") (pin "1") (pinfunction "1_1") (pintype "passive"))
      (node (ref "C0945") (pin "2") (pinfunction "2_2") (pintype "passive"))
      (node (ref "C0952") (pin "1") (pinfunction "1_1") (pintype "passive"))
      (node (ref "L0943") (pin "1") (pinfunction "1_1") (pintype "passive"))
      (node (ref "R0945") (pin "2") (pinfunction "2_2") (pintype "passive"))
      (node (ref "U0951") (pin "2") (pinfunction "V-_2") (pintype "power_in"))
      (node (ref "U0961") (pin "2") (pinfunction "V-_2") (pintype "power_in"))
    )
    (net (code "41") (name "CAT_DTE_CTS") (class "Default")
      (node (ref "C1153") (pin "1") (pinfunction "1_1") (pintype "passive"))
      (node (ref "U1101") (pin "7") (pinfunction "T2OUT_7") (pintype "output"))
      (node (ref "X1153") (pin "1") (pinfunction "1_1") (pintype "passive"))
    )
    (net (code "42") (name "CAT_DTE_RTR") (class "Default")
      (node (ref "C1154") (pin "1") (pinfunction "1_1") (pintype "passive"))
      (node (ref "U1101") (pin "8") (pinfunction "R2IN_8") (pintype "input"))
      (node (ref "X1153") (pin "2") (pinfunction "2_2") (pintype "passive"))
    )
    (net (code "43") (name "CAT_DTE_RXD") (class "Default")
      (node (ref "C1151") (pin "1") (pinfunction "1_1") (pintype "passive"))
      (node (ref "U1101") (pin "14") (pinfunction "T1OUT_14") (pintype "output"))
      (node (ref "X1151") (pin "1") (pinfunction "1_1") (pintype "passive"))
    )
    (net (code "44") (name "CAT_DTE_TXD") (class "Default")
      (node (ref "C1152") (pin "1") (pinfunction "1_1") (pintype "passive"))
      (node (ref "U1101") (pin "13") (pinfunction "R1IN_13") (pintype "input"))
      (node (ref "X1151") (pin "2") (pinfunction "2_2") (pintype "passive"))
    )
    (net (code "45") (name "CAT_MX_C1P") (class "Default")
      (node (ref "C1102") (pin "1") (pinfunction "1_1") (pintype "passive"))
      (node (ref "U1101") (pin "1") (pinfunction "C1+_1") (pintype "bidirectional"))
    )
    (net (code "46") (name "CAT_MX_C2P") (class "Default")
      (node (ref "C1103") (pin "1") (pinfunction "1_1") (pintype "passive"))
      (node (ref "U1101") (pin "4") (pinfunction "C2+_4") (pintype "bidirectional"))
    )
    (net (code "47") (name "CAT_MX_VM") (class "Default")
      (node (ref "C1105") (pin "1") (pinfunction "1_1") (pintype "passive"))
      (node (ref "U1101") (pin "6") (pinfunction "V-_6") (pintype "bidirectional"))
    )
    (net (code "48") (name "CAT_MX_VP") (class "Default")
      (node (ref "C1104") (pin "1") (pinfunction "1_1") (pintype "passive"))
      (node (ref "U1101") (pin "2") (pinfunction "V+_2") (pintype "bidirectional"))
    )
    (net (code "49") (name "DRV_OUT_3_4") (class "Default")
      (node (ref "U0801") (pin "12") (pinfunction "OUT4_12") (pintype "passive"))
    )
    (net (code "50") (name "DRV_OUT_3_5") (class "Default")
      (node (ref "U0801") (pin "13") (pinfunction "OUT5_13") (pintype "passive"))
    )
    (net (code "51") (name "DRV_OUT_3_6") (class "Default")
      (node (ref "U0801") (pin "15") (pinfunction "OUT6_15") (pintype "passive"))
    )
    (net (code "52") (name "DRV_OUT_3_7") (class "Default")
      (node (ref "U0801") (pin "16") (pinfunction "OUT7_16") (pintype "passive"))
    )
    (net (code "53") (name "DRV_OUT_3_8") (class "Default")
      (node (ref "U0801") (pin "17") (pinfunction "OUT8_17") (pintype "passive"))
    )
    (net (code "54") (name "DRV_OUT_3_9") (class "Default")
      (node (ref "U0801") (pin "18") (pinfunction "OUT9_18") (pintype "passive"))
    )
    (net (code "55") (name "DRV_OUT_3_10") (class "Default")
      (node (ref "U0801") (pin "20") (pinfunction "OUT10_20") (pintype "passive"))
    )
    (net (code "56") (name "DRV_OUT_3_11") (class "Default")
      (node (ref "U0801") (pin "21") (pinfunction "OUT11_21") (pintype "passive"))
    )
    (net (code "57") (name "DRV_OUT_3_12") (class "Default")
      (node (ref "U0801") (pin "28") (pinfunction "OUT12_28") (pintype "passive"))
    )
    (net (code "58") (name "DRV_OUT_3_13") (class "Default")
      (node (ref "U0801") (pin "29") (pinfunction "OUT13_29") (pintype "passive"))
    )
    (net (code "59") (name "DRV_OUT_3_14") (class "Default")
      (node (ref "U0801") (pin "31") (pinfunction "OUT14_31") (pintype "passive"))
    )
    (net (code "60") (name "DRV_OUT_3_15") (class "Default")
      (node (ref "U0801") (pin "32") (pinfunction "OUT15_32") (pintype "passive"))
    )
    (net (code "61") (name "GND") (class "Default")
      (node (ref "C0054") (pin "2") (pinfunction "2_2") (pintype "passive"))
      (node (ref "C0213") (pin "2") (pinfunction "2_2") (pintype "passive"))
      (node (ref "C0311") (pin "2") (pinfunction "2_2") (pintype "passive"))
      (node (ref "C0331") (pin "+") (pinfunction "A_+") (pintype "passive"))
      (node (ref "C0332") (pin "2") (pinfunction "2_2") (pintype "passive"))
      (node (ref "C0401") (pin "2") (pinfunction "2_2") (pintype "passive"))
      (node (ref "C0402") (pin "2") (pinfunction "2_2") (pintype "passive"))
      (node (ref "C0403") (pin "2") (pinfunction "2_2") (pintype "passive"))
      (node (ref "C0410") (pin "2") (pinfunction "2_2") (pintype "passive"))
      (node (ref "C0412") (pin "2") (pinfunction "2_2") (pintype "passive"))
      (node (ref "C0413") (pin "2") (pinfunction "2_2") (pintype "passive"))
      (node (ref "C0451") (pin "2") (pinfunction "2_2") (pintype "passive"))
      (node (ref "C0601") (pin "1") (pinfunction "1_1") (pintype "passive"))
      (node (ref "C0602") (pin "2") (pinfunction "2_2") (pintype "passive"))
      (node (ref "C0603") (pin "2") (pinfunction "2_2") (pintype "passive"))
      (node (ref "C0701") (pin "1") (pinfunction "1_1") (pintype "passive"))
      (node (ref "C0702") (pin "2") (pinfunction "2_2") (pintype "passive"))
      (node (ref "C0703") (pin "2") (pinfunction "2_2") (pintype "passive"))
      (node (ref "C0801") (pin "1") (pinfunction "1_1") (pintype "passive"))
      (node (ref "C0802") (pin "2") (pinfunction "2_2") (pintype "passive"))
      (node (ref "C0803") (pin "2") (pinfunction "2_2") (pintype "passive"))
      (node (ref "C0901") (pin "2") (pinfunction "2_2") (pintype "passive"))
      (node (ref "C0911") (pin "2") (pinfunction "2_2") (pintype "passive"))
      (node (ref "C0921") (pin "2") (pinfunction "2_2") (pintype "passive"))
      (node (ref "C0941") (pin "2") (pinfunction "2_2") (pintype "passive"))
      (node (ref "C0943") (pin "2") (pinfunction "2_2") (pintype "passive"))
      (node (ref "C0951") (pin "2") (pinfunction "2_2") (pintype "passive"))
      (node (ref "C0952") (pin "2") (pinfunction "2_2") (pintype "passive"))
      (node (ref "C0962") (pin "2") (pinfunction "2_2") (pintype "passive"))
      (node (ref "C1001") (pin "2") (pinfunction "2_2") (pintype "passive"))
      (node (ref "C1004") (pin "2") (pinfunction "2_2") (pintype "passive"))
      (node (ref "C1005") (pin "2") (pinfunction "2_2") (pintype "passive"))
      (node (ref "C1051") (pin "2") (pinfunction "2_2") (pintype "passive"))
      (node (ref "C1052") (pin "2") (pinfunction "2_2") (pintype "passive"))
      (node (ref "C1053") (pin "2") (pinfunction "2_2") (pintype "passive"))
      (node (ref "C1101") (pin "2") (pinfunction "2_2") (pintype "passive"))
      (node (ref "C1104") (pin "2") (pinfunction "2_2") (pintype "passive"))
      (node (ref "C1105") (pin "2") (pinfunction "2_2") (pintype "passive"))
      (node (ref "C1151") (pin "2") (pinfunction "2_2") (pintype "passive"))
      (node (ref "C1152") (pin "2") (pinfunction "2_2") (pintype "passive"))
      (node (ref "C1153") (pin "2") (pinfunction "2_2") (pintype "passive"))
      (node (ref "C1154") (pin "2") (pinfunction "2_2") (pintype "passive"))
      (node (ref "C1201") (pin "2") (pinfunction "2_2") (pintype "passive"))
      (node (ref "C1202") (pin "2") (pinfunction "2_2") (pintype "passive"))
      (node (ref "C1203") (pin "2") (pinfunction "2_2") (pintype "passive"))
      (node (ref "C1204") (pin "2") (pinfunction "2_2") (pintype "passive"))
      (node (ref "C1205") (pin "1") (pinfunction "1_1") (pintype "passive"))
      (node (ref "C1212") (pin "2") (pinfunction "2_2") (pintype "passive"))
      (node (ref "C1221") (pin "2") (pinfunction "2_2") (pintype "passive"))
      (node (ref "C1222") (pin "2") (pinfunction "2_2") (pintype "passive"))
      (node (ref "C1223") (pin "2") (pinfunction "2_2") (pintype "passive"))
      (node (ref "C1301") (pin "2") (pinfunction "2_2") (pintype "passive"))
      (node (ref "C1311") (pin "2") (pinfunction "2_2") (pintype "passive"))
      (node (ref "C1403") (pin "1") (pinfunction "1_1") (pintype "passive"))
      (node (ref "D0942") (pin "C") (pinfunction "C_C") (pintype "passive"))
      (node (ref "D0971") (pin "C") (pinfunction "C_C") (pintype "passive"))
      (node (ref "H1711") (pin "B3,0") (pinfunction "MOUNT_B3,0") (pintype "passive"))
      (node (ref "H1721") (pin "B3,0") (pinfunction "MOUNT_B3,0") (pintype "passive"))
      (node (ref "H1731") (pin "B3,0") (pinfunction "MOUNT_B3,0") (pintype "passive"))
      (node (ref "H1751") (pin "B3,0") (pinfunction "MOUNT_B3,0") (pintype "passive"))
      (node (ref "H1761") (pin "B3,0") (pinfunction "MOUNT_B3,0") (pintype "passive"))
      (node (ref "R0221") (pin "1") (pinfunction "1_1") (pintype "passive"))
      (node (ref "R0232") (pin "1") (pinfunction "1_1") (pintype "passive"))
      (node (ref "R0441") (pin "1") (pinfunction "1_1") (pintype "passive"))
      (node (ref "R0901") (pin "1") (pinfunction "1_1") (pintype "passive"))
      (node (ref "R0911") (pin "1") (pinfunction "1_1") (pintype "passive"))
      (node (ref "R0946") (pin "1") (pinfunction "1_1") (pintype "passive"))
      (node (ref "R1301") (pin "1") (pinfunction "1_1") (pintype "passive"))
      (node (ref "R1402") (pin "1") (pinfunction "1_1") (pintype "passive"))
      (node (ref "S0212") (pin "1") (pinfunction "P_1") (pintype "passive"))
      (node (ref "U0101") (pin "18") (pinfunction "VSS_18") (pintype "passive"))
      (node (ref "U0101") (pin "31") (pinfunction "VSS_31") (pintype "passive"))
      (node (ref "U0101") (pin "47") (pinfunction "VSS_47") (pintype "passive"))
      (node (ref "U0101") (pin "63") (pinfunction "VSS_63") (pintype "passive"))
      (node (ref "U0601") (pin "10") (pinfunction "GND_MC_10") (pintype "passive"))
      (node (ref "U0601") (pin "23") (pinfunction "GND_MC_23") (pintype "passive"))
      (node (ref "U0601") (pin "24") (pinfunction "GND_MC_24") (pintype "passive"))
      (node (ref "U0601") (pin "25") (pinfunction "GND_MC_25") (pintype "passive"))
      (node (ref "U0601") (pin "26") (pinfunction "GND_MC_26") (pintype "passive"))
      (node (ref "U0601") (pin "33") (pinfunction "EP_33") (pintype "passive"))
      (node (ref "U0601") (pin "7") (pinfunction "GND_MC_7") (pintype "passive"))
      (node (ref "U0601") (pin "8") (pinfunction "GND_MC_8") (pintype "passive"))
      (node (ref "U0601") (pin "9") (pinfunction "GND_MC_9") (pintype "passive"))
      (node (ref "U0701") (pin "10") (pinfunction "GND_MC_10") (pintype "passive"))
      (node (ref "U0701") (pin "23") (pinfunction "GND_MC_23") (pintype "passive"))
      (node (ref "U0701") (pin "24") (pinfunction "GND_MC_24") (pintype "passive"))
      (node (ref "U0701") (pin "25") (pinfunction "GND_MC_25") (pintype "passive"))
      (node (ref "U0701") (pin "26") (pinfunction "GND_MC_26") (pintype "passive"))
      (node (ref "U0701") (pin "33") (pinfunction "EP_33") (pintype "passive"))
      (node (ref "U0701") (pin "7") (pinfunction "GND_MC_7") (pintype "passive"))
      (node (ref "U0701") (pin "8") (pinfunction "GND_MC_8") (pintype "passive"))
      (node (ref "U0701") (pin "9") (pinfunction "GND_MC_9") (pintype "passive"))
      (node (ref "U0801") (pin "10") (pinfunction "GND_MC_10") (pintype "passive"))
      (node (ref "U0801") (pin "23") (pinfunction "GND_MC_23") (pintype "passive"))
      (node (ref "U0801") (pin "24") (pinfunction "GND_MC_24") (pintype "passive"))
      (node (ref "U0801") (pin "25") (pinfunction "GND_MC_25") (pintype "passive"))
      (node (ref "U0801") (pin "26") (pinfunction "GND_MC_26") (pintype "passive"))
      (node (ref "U0801") (pin "33") (pinfunction "EP_33") (pintype "passive"))
      (node (ref "U0801") (pin "7") (pinfunction "GND_MC_7") (pintype "passive"))
      (node (ref "U0801") (pin "8") (pinfunction "GND_MC_8") (pintype "passive"))
      (node (ref "U0801") (pin "9") (pinfunction "GND_MC_9") (pintype "passive"))
      (node (ref "U0921") (pin "4") (pinfunction "4_4") (pintype "passive"))
      (node (ref "U0941") (pin "2") (pinfunction "GND_2") (pintype "passive"))
      (node (ref "U0951") (pin "3") (pinfunction "+IN_3") (pintype "input"))
      (node (ref "U0961") (pin "3") (pinfunction "+IN_3") (pintype "input"))
      (node (ref "U0962") (pin "1") (pinfunction "HVC/A0_1") (pintype "input"))
      (node (ref "U0962") (pin "12") (pinfunction "A2_12") (pintype "input"))
      (node (ref "U0962") (pin "13") (pinfunction "A1_13") (pintype "input"))
      (node (ref "U0962") (pin "4") (pinfunction "VSS_4") (pintype "passive"))
      (node (ref "U1001") (pin "15") (pinfunction "GND_15") (pintype "power_in"))
      (node (ref "U1101") (pin "15") (pinfunction "GND_15") (pintype "power_in"))
      (node (ref "U1201") (pin "10") (pinfunction "AGND_10") (pintype "passive"))
      (node (ref "U1201") (pin "15") (pinfunction "PGND_15") (pintype "passive"))
      (node (ref "U1201") (pin "16") (pinfunction "PGND_16") (pintype "passive"))
      (node (ref "U1201") (pin "6") (pinfunction "SYNC_6") (pintype "input"))
      (node (ref "U1201") (pin "7") (pinfunction "FPWM_7") (pintype "input"))
      (node (ref "U1201") (pin "PAD") (pinfunction "EP_PAD") (pintype "passive"))
      (node (ref "U1201") (pin "PAD1") (pinfunction "EP_PAD1") (pintype "passive"))
      (node (ref "U1201") (pin "PAD10") (pinfunction "EP_PAD10") (pintype "passive"))
      (node (ref "U1201") (pin "PAD11") (pinfunction "EP_PAD11") (pintype "passive"))
      (node (ref "U1201") (pin "PAD12") (pinfunction "EP_PAD12") (pintype "passive"))
      (node (ref "U1201") (pin "PAD13") (pinfunction "EP_PAD13") (pintype "passive"))
      (node (ref "U1201") (pin "PAD2") (pinfunction "EP_PAD2") (pintype "passive"))
      (node (ref "U1201") (pin "PAD3") (pinfunction "EP_PAD3") (pintype "passive"))
      (node (ref "U1201") (pin "PAD4") (pinfunction "EP_PAD4") (pintype "passive"))
      (node (ref "U1201") (pin "PAD5") (pinfunction "EP_PAD5") (pintype "passive"))
      (node (ref "U1201") (pin "PAD6") (pinfunction "EP_PAD6") (pintype "passive"))
      (node (ref "U1201") (pin "PAD7") (pinfunction "EP_PAD7") (pintype "passive"))
      (node (ref "U1201") (pin "PAD8") (pinfunction "EP_PAD8") (pintype "passive"))
      (node (ref "U1201") (pin "PAD9") (pinfunction "EP_PAD9") (pintype "passive"))
      (node (ref "U1301") (pin "10") (pinfunction "PGND_10") (pintype "passive"))
      (node (ref "U1301") (pin "3") (pinfunction "VSS_3") (pintype "passive"))
      (node (ref "U1301") (pin "7") (pinfunction "SYNC_7") (pintype "input"))
      (node (ref "X0201") (pin "3") (pinfunction "3_3") (pintype "passive"))
      (node (ref "X0201") (pin "5") (pinfunction "5_5") (pintype "passive"))
      (node (ref "X0201") (pin "9") (pinfunction "9_9") (pintype "passive"))
      (node (ref "X0601") (pin "2") (pinfunction "2_2") (pintype "passive"))
      (node (ref "X0601") (pin "4") (pinfunction "4_4") (pintype "passive"))
      (node (ref "X1052") (pin "1") (pinfunction "1_1") (pintype "passive"))
      (node (ref "X1052") (pin "2") (pinfunction "2_2") (pintype "passive"))
      (node (ref "X1152") (pin "1") (pinfunction "1_1") (pintype "passive"))
      (node (ref "X1152") (pin "2") (pinfunction "2_2") (pintype "passive"))
      (node (ref "X1211") (pin "2") (pinfunction "2_2") (pintype "passive"))
      (node (ref "X1401") (pin "GND") (pinfunction "GND_GND") (pintype "passive"))
      (node (ref "X1501") (pin "2") (pinfunction "2_2") (pintype "passive"))
      (node (ref "X1501") (pin "3") (pinfunction "2_3") (pintype "passive"))
      (node (ref "X1501") (pin "4") (pinfunction "2_4") (pintype "passive"))
      (node (ref "X1501") (pin "5") (pinfunction "2_5") (pintype "passive"))
      (node (ref "X1511") (pin "2") (pinfunction "2_2") (pintype "passive"))
      (node (ref "X1511") (pin "3") (pinfunction "2_3") (pintype "passive"))
      (node (ref "X1511") (pin "4") (pinfunction "2_4") (pintype "passive"))
      (node (ref "X1511") (pin "5") (pinfunction "2_5") (pintype "passive"))
    )
    (net (code "62") (name "MCU_NRST") (class "Default")
      (node (ref "C0213") (pin "1") (pinfunction "1_1") (pintype "passive"))
      (node (ref "S0212") (pin "2") (pinfunction "S_2") (pintype "passive"))
      (node (ref "U0101") (pin "7") (pinfunction "NRST_7") (pintype "bidirectional"))
      (node (ref "X0201") (pin "10") (pinfunction "10_10") (pintype "passive"))
    )
    (net (code "63") (name "MCU_VBAT") (class "Default")
      (node (ref "C0451") (pin "1") (pinfunction "1_1") (pintype "passive"))
      (node (ref "TP_VBAT") (pin "TP") (pinfunction "TP_TP") (pintype "input"))
      (node (ref "U0101") (pin "1") (pinfunction "VBAT_1") (pintype "power_in"))
    )
    (net (code "64") (name "MCU_VDD") (class "Default")
      (node (ref "C0401") (pin "1") (pinfunction "1_1") (pintype "passive"))
      (node (ref "C0402") (pin "1") (pinfunction "1_1") (pintype "passive"))
      (node (ref "C0403") (pin "1") (pinfunction "1_1") (pintype "passive"))
      (node (ref "C0410") (pin "1") (pinfunction "1_1") (pintype "passive"))
      (node (ref "L0411") (pin "1") (pinfunction "1_1") (pintype "passive"))
      (node (ref "SJ0401") (pin "2") (pinfunction "2_2") (pintype "passive"))
      (node (ref "U0101") (pin "19") (pinfunction "VDD_19") (pintype "power_in"))
      (node (ref "U0101") (pin "32") (pinfunction "VDD_32") (pintype "power_in"))
      (node (ref "U0101") (pin "64") (pinfunction "VDD_64") (pintype "power_in"))
    )
    (net (code "65") (name "MCU_VDDA") (class "Default")
      (node (ref "C0412") (pin "1") (pinfunction "1_1") (pintype "passive"))
      (node (ref "C0413") (pin "1") (pinfunction "1_1") (pintype "passive"))
      (node (ref "L0411") (pin "2") (pinfunction "2_2") (pintype "passive"))
      (node (ref "U0101") (pin "13") (pinfunction "VDDA_VREF_P_13") (pintype "power_in"))
    )
    (net (code "66") (name "MCU_VREF_M") (class "Default")
      (node (ref "R0441") (pin "2") (pinfunction "2_2") (pintype "passive"))
      (node (ref "U0101") (pin "12") (pinfunction "VSSA_VREF_M_12") (pintype "passive"))
    )
    (net (code "67") (name "MP_CAT_CTS_R") (class "Default")
      (node (ref "R1103") (pin "2") (pinfunction "2_2") (pintype "passive"))
      (node (ref "U1101") (pin "10") (pinfunction "T2IN_10") (pintype "input"))
    )
    (net (code "68") (name "MP_CAT_RTR_R") (class "Default")
      (node (ref "R1104") (pin "2") (pinfunction "2_2") (pintype "passive"))
      (node (ref "U1101") (pin "9") (pinfunction "R2OUT_9") (pintype "output"))
    )
    (net (code "69") (name "MP_CAT_RXD_R") (class "Default")
      (node (ref "R1101") (pin "2") (pinfunction "2_2") (pintype "passive"))
      (node (ref "U1101") (pin "11") (pinfunction "T1IN_11") (pintype "input"))
    )
    (net (code "70") (name "MP_CAT_TXD_R") (class "Default")
      (node (ref "R1102") (pin "2") (pinfunction "2_2") (pintype "passive"))
      (node (ref "U1101") (pin "12") (pinfunction "R1OUT_12") (pintype "output"))
    )
    (net (code "71") (name "MP_RS_CTS_R") (class "Default")
      (node (ref "R1003") (pin "2") (pinfunction "2_2") (pintype "passive"))
      (node (ref "U1001") (pin "10") (pinfunction "T2IN_10") (pintype "input"))
    )
    (net (code "72") (name "MP_RS_RTR_R") (class "Default")
      (node (ref "R1004") (pin "2") (pinfunction "2_2") (pintype "passive"))
      (node (ref "U1001") (pin "9") (pinfunction "R2OUT_9") (pintype "output"))
    )
    (net (code "73") (name "MP_RS_RXD_R") (class "Default")
      (node (ref "R1001") (pin "2") (pinfunction "2_2") (pintype "passive"))
      (node (ref "U1001") (pin "11") (pinfunction "T1IN_11") (pintype "input"))
    )
    (net (code "74") (name "MP_RS_TXD_R") (class "Default")
      (node (ref "R1002") (pin "2") (pinfunction "2_2") (pintype "passive"))
      (node (ref "U1001") (pin "12") (pinfunction "R1OUT_12") (pintype "output"))
    )
    (net (code "75") (name "Net-(C0942-Pad2)") (class "Default")
      (node (ref "C0942") (pin "2") (pinfunction "2_2") (pintype "passive"))
      (node (ref "D0942") (pin "A") (pinfunction "A_A") (pintype "passive"))
      (node (ref "L0943") (pin "2") (pinfunction "2_2") (pintype "passive"))
    )
    (net (code "76") (name "Net-(C1211-Pad1)") (class "Default")
      (node (ref "C1211") (pin "1") (pinfunction "1_1") (pintype "passive"))
      (node (ref "L1211") (pin "2") (pinfunction "2_2") (pintype "passive"))
      (node (ref "U1201") (pin "1") (pinfunction "SW_1") (pintype "passive"))
      (node (ref "U1201") (pin "2") (pinfunction "SW_2") (pintype "passive"))
    )
    (net (code "77") (name "Net-(C1403-Pad2)") (class "Default")
      (node (ref "C1403") (pin "2") (pinfunction "2_2") (pintype "passive"))
      (node (ref "R1402") (pin "2") (pinfunction "2_2") (pintype "passive"))
      (node (ref "X1401") (pin "JSHIELD") (pinfunction "SHIELD_JSHIELD") (pintype "passive"))
      (node (ref "X1401") (pin "JSHIELD@2") (pinfunction "SHIELD_JSHIELD@2") (pintype "passive"))
      (node (ref "X1401") (pin "JSHIELD@3") (pinfunction "SHIELD_JSHIELD@3") (pintype "passive"))
      (node (ref "X1401") (pin "JSHIELD@4") (pinfunction "SHIELD_JSHIELD@4") (pintype "passive"))
      (node (ref "X1401") (pin "JSHIELD@5") (pinfunction "SHIELD_JSHIELD@5") (pintype "passive"))
      (node (ref "X1401") (pin "JSHIELD@6") (pinfunction "SHIELD_JSHIELD@6") (pintype "passive"))
    )
    (net (code "78") (name "Net-(U0601-SO)") (class "Default")
      (node (ref "R0611") (pin "2") (pinfunction "2_2") (pintype "passive"))
      (node (ref "U0601") (pin "22") (pinfunction "SO_22") (pintype "output"))
    )
    (net (code "79") (name "Net-(U0701-SO)") (class "Default")
      (node (ref "R0711") (pin "2") (pinfunction "2_2") (pintype "passive"))
      (node (ref "U0701") (pin "22") (pinfunction "SO_22") (pintype "output"))
    )
    (net (code "80") (name "Net-(U0801-SO)") (class "Default")
      (node (ref "R0811") (pin "2") (pinfunction "2_2") (pintype "passive"))
      (node (ref "U0801") (pin "22") (pinfunction "SO_22") (pintype "output"))
    )
    (net (code "81") (name "Net-(U0941-NFB)") (class "Default")
      (node (ref "C0945") (pin "1") (pinfunction "1_1") (pintype "passive"))
      (node (ref "R0945") (pin "1") (pinfunction "1_1") (pintype "passive"))
      (node (ref "R0946") (pin "2") (pinfunction "2_2") (pintype "passive"))
      (node (ref "U0941") (pin "3") (pinfunction "NFB_3") (pintype "input"))
    )
    (net (code "82") (name "Net-(U0941-SW)") (class "Default")
      (node (ref "C0942") (pin "1") (pinfunction "1_1") (pintype "passive"))
      (node (ref "L0941") (pin "1") (pinfunction "1_1") (pintype "passive"))
      (node (ref "U0941") (pin "1") (pinfunction "SW_1") (pintype "output"))
    )
    (net (code "83") (name "Net-(U0951-OUT)") (class "Default")
      (node (ref "D0951") (pin "C") (pinfunction "C_C") (pintype "passive"))
      (node (ref "R0961") (pin "1") (pinfunction "1_1") (pintype "passive"))
      (node (ref "U0951") (pin "1") (pinfunction "OUT_1") (pintype "output"))
    )
    (net (code "84") (name "Net-(U0961--IN)") (class "Default")
      (node (ref "C0963") (pin "1") (pinfunction "1_1") (pintype "passive"))
      (node (ref "R0961") (pin "2") (pinfunction "2_2") (pintype "passive"))
      (node (ref "R0962") (pin "1") (pinfunction "1_1") (pintype "passive"))
      (node (ref "U0961") (pin "4") (pinfunction "-IN_4") (pintype "input"))
      (node (ref "U0962") (pin "6") (pinfunction "P1W_6") (pintype "passive"))
    )
    (net (code "85") (name "Net-(U0961-OUT)") (class "Default")
      (node (ref "C0963") (pin "2") (pinfunction "2_2") (pintype "passive"))
      (node (ref "R0963") (pin "2") (pinfunction "2_2") (pintype "passive"))
      (node (ref "R0972") (pin "1") (pinfunction "1_1") (pintype "passive"))
      (node (ref "U0961") (pin "1") (pinfunction "OUT_1") (pintype "output"))
    )
    (net (code "86") (name "Net-(U0962-P0W)") (class "Default")
      (node (ref "R0962") (pin "2") (pinfunction "2_2") (pintype "passive"))
      (node (ref "U0962") (pin "9") (pinfunction "P0W_9") (pintype "passive"))
    )
    (net (code "87") (name "Net-(U0962-P1A)") (class "Default")
      (node (ref "R0963") (pin "1") (pinfunction "1_1") (pintype "passive"))
      (node (ref "U0962") (pin "7") (pinfunction "P1A_7") (pintype "passive"))
    )
    (net (code "88") (name "Net-(U1001A-C1-)") (class "Default")
      (node (ref "C1002") (pin "2") (pinfunction "2_2") (pintype "passive"))
      (node (ref "U1001") (pin "3") (pinfunction "C1-_3") (pintype "bidirectional"))
    )
    (net (code "89") (name "Net-(U1001A-C2-)") (class "Default")
      (node (ref "C1003") (pin "2") (pinfunction "2_2") (pintype "passive"))
      (node (ref "U1001") (pin "5") (pinfunction "C2-_5") (pintype "bidirectional"))
    )
    (net (code "90") (name "Net-(U1101A-C1-)") (class "Default")
      (node (ref "C1102") (pin "2") (pinfunction "2_2") (pintype "passive"))
      (node (ref "U1101") (pin "3") (pinfunction "C1-_3") (pintype "bidirectional"))
    )
    (net (code "91") (name "Net-(U1101A-C2-)") (class "Default")
      (node (ref "C1103") (pin "2") (pinfunction "2_2") (pintype "passive"))
      (node (ref "U1101") (pin "5") (pinfunction "C2-_5") (pintype "bidirectional"))
    )
    (net (code "92") (name "Net-(U1201-BIAS)") (class "Default")
      (node (ref "C1212") (pin "1") (pinfunction "1_1") (pintype "passive"))
      (node (ref "R1211") (pin "1") (pinfunction "1_1") (pintype "passive"))
      (node (ref "U1201") (pin "5") (pinfunction "BIAS_5") (pintype "power_in"))
    )
    (net (code "93") (name "Net-(U1201-CBOOT)") (class "Default")
      (node (ref "C1211") (pin "2") (pinfunction "2_2") (pintype "passive"))
      (node (ref "U1201") (pin "3") (pinfunction "CBOOT_3") (pintype "passive"))
    )
    (net (code "94") (name "Net-(U1201-VCC)") (class "Default")
      (node (ref "C1205") (pin "2") (pinfunction "2_2") (pintype "passive"))
      (node (ref "U1201") (pin "4") (pinfunction "VCC_4") (pintype "passive"))
    )
    (net (code "95") (name "Net-(U1301-LBI)") (class "Default")
      (node (ref "R1301") (pin "2") (pinfunction "2_2") (pintype "passive"))
      (node (ref "R1302") (pin "1") (pinfunction "1_1") (pintype "passive"))
      (node (ref "U1301") (pin "6") (pinfunction "LBI_6") (pintype "input"))
    )
    (net (code "96") (name "Net-(U1301-SW)") (class "Default")
      (node (ref "L1311") (pin "2") (pinfunction "2_2") (pintype "passive"))
      (node (ref "L1311") (pin "4") (pinfunction "2_4") (pintype "passive"))
      (node (ref "U1301") (pin "9") (pinfunction "SW_9") (pintype "passive"))
    )
    (net (code "97") (name "PA0") (class "Default")
      (node (ref "R1101") (pin "1") (pinfunction "1_1") (pintype "passive"))
      (node (ref "U0101") (pin "14") (pinfunction "PA0_WKUP_14") (pintype "bidirectional"))
    )
    (net (code "98") (name "PA1") (class "Default")
      (node (ref "R1102") (pin "1") (pinfunction "1_1") (pintype "passive"))
      (node (ref "U0101") (pin "15") (pinfunction "PA1_15") (pintype "bidirectional"))
    )
    (net (code "99") (name "PA3") (class "Default")
      (node (ref "R0922") (pin "1") (pinfunction "1_1") (pintype "passive"))
      (node (ref "U0101") (pin "17") (pinfunction "PA3_17") (pintype "bidirectional"))
    )
    (net (code "100") (name "PA5") (class "Default")
      (node (ref "R0621") (pin "1") (pinfunction "1_1") (pintype "passive"))
      (node (ref "U0101") (pin "21") (pinfunction "PA5_21") (pintype "bidirectional"))
    )
    (net (code "101") (name "PA6") (class "Default")
      (node (ref "R0622") (pin "1") (pinfunction "1_1") (pintype "passive"))
      (node (ref "U0101") (pin "22") (pinfunction "PA6_22") (pintype "bidirectional"))
    )
    (net (code "102") (name "PA7") (class "Default")
      (node (ref "R0623") (pin "1") (pinfunction "1_1") (pintype "passive"))
      (node (ref "U0101") (pin "23") (pinfunction "PA7_23") (pintype "bidirectional"))
    )
    (net (code "103") (name "PA9") (class "Default")
      (node (ref "PF1411") (pin "1") (pinfunction "1_1") (pintype "passive"))
      (node (ref "U0101") (pin "42") (pinfunction "PA9_42") (pintype "bidirectional"))
      (node (ref "X1401") (pin "VBUS") (pinfunction "J_VUSB_VBUS") (pintype "power_in"))
    )
    (net (code "104") (name "PA10") (class "Default")
      (node (ref "U0101") (pin "43") (pinfunction "PA10_43") (pintype "bidirectional"))
      (node (ref "X1401") (pin "ID") (pinfunction "J_ID_ID") (pintype "bidirectional"))
    )
    (net (code "105") (name "PA11") (class "Default")
      (node (ref "U0101") (pin "44") (pinfunction "PA11_44") (pintype "bidirectional"))
      (node (ref "X1401") (pin "D-") (pinfunction "J_D-_D-") (pintype "bidirectional"))
    )
    (net (code "106") (name "PA12") (class "Default")
      (node (ref "U0101") (pin "45") (pinfunction "PA12_45") (pintype "bidirectional"))
      (node (ref "X1401") (pin "D+") (pinfunction "J_D+_D+") (pintype "bidirectional"))
    )
    (net (code "107") (name "PA13") (class "Default")
      (node (ref "R0231") (pin "1") (pinfunction "1_1") (pintype "passive"))
      (node (ref "U0101") (pin "46") (pinfunction "PA13_JTMS_SWDIO_46") (pintype "bidirectional"))
      (node (ref "X0201") (pin "2") (pinfunction "2_2") (pintype "passive"))
    )
    (net (code "108") (name "PA14") (class "Default")
      (node (ref "R0232") (pin "2") (pinfunction "2_2") (pintype "passive"))
      (node (ref "U0101") (pin "49") (pinfunction "PA14_JTCK_SWCLK_49") (pintype "bidirectional"))
      (node (ref "X0201") (pin "4") (pinfunction "4_4") (pintype "passive"))
    )
    (net (code "109") (name "PA15") (class "Default")
      (node (ref "R1103") (pin "1") (pinfunction "1_1") (pintype "passive"))
      (node (ref "U0101") (pin "50") (pinfunction "PA15_JTDI_50") (pintype "bidirectional"))
    )
    (net (code "110") (name "PB0") (class "Default")
      (node (ref "R0624") (pin "1") (pinfunction "1_1") (pintype "passive"))
      (node (ref "U0101") (pin "26") (pinfunction "PB0_26") (pintype "bidirectional"))
    )
    (net (code "111") (name "PB1") (class "Default")
      (node (ref "R0724") (pin "1") (pinfunction "1_1") (pintype "passive"))
      (node (ref "U0101") (pin "27") (pinfunction "PB1_27") (pintype "bidirectional"))
    )
    (net (code "112") (name "PB2") (class "Default")
      (node (ref "R0824") (pin "1") (pinfunction "1_1") (pintype "passive"))
      (node (ref "U0101") (pin "28") (pinfunction "PB2_28") (pintype "bidirectional"))
    )
    (net (code "113") (name "PB6") (class "Default")
      (node (ref "R0512") (pin "1") (pinfunction "1_1") (pintype "passive"))
      (node (ref "U0101") (pin "58") (pinfunction "PB6_58") (pintype "bidirectional"))
      (node (ref "U0962") (pin "2") (pinfunction "SCL_2") (pintype "input"))
      (node (ref "X0601") (pin "1") (pinfunction "1_1") (pintype "passive"))
    )
    (net (code "114") (name "PB7") (class "Default")
      (node (ref "R1104") (pin "1") (pinfunction "1_1") (pintype "passive"))
      (node (ref "U0101") (pin "59") (pinfunction "PB7_59") (pintype "bidirectional"))
    )
    (net (code "115") (name "PB9") (class "Default")
      (node (ref "R0511") (pin "1") (pinfunction "1_1") (pintype "passive"))
      (node (ref "U0101") (pin "62") (pinfunction "PB9_62") (pintype "bidirectional"))
      (node (ref "U0962") (pin "3") (pinfunction "SDA_3") (pintype "bidirectional"))
      (node (ref "X0601") (pin "3") (pinfunction "3_3") (pintype "passive"))
    )
    (net (code "116") (name "PB10") (class "Default")
      (node (ref "R1002") (pin "1") (pinfunction "1_1") (pintype "passive"))
      (node (ref "U0101") (pin "29") (pinfunction "PB10_29") (pintype "bidirectional"))
    )
    (net (code "117") (name "PB11") (class "Default")
      (node (ref "R0626") (pin "1") (pinfunction "1_1") (pintype "passive"))
      (node (ref "U0101") (pin "30") (pinfunction "PB11_30") (pintype "bidirectional"))
    )
    (net (code "118") (name "PB12") (class "Default")
      (node (ref "R1003") (pin "1") (pinfunction "1_1") (pintype "passive"))
      (node (ref "U0101") (pin "33") (pinfunction "PB12_33") (pintype "bidirectional"))
    )
    (net (code "119") (name "PB13") (class "Default")
      (node (ref "R1004") (pin "1") (pinfunction "1_1") (pintype "passive"))
      (node (ref "U0101") (pin "34") (pinfunction "PB13_34") (pintype "bidirectional"))
    )
    (net (code "120") (name "PC0") (class "Default")
      (node (ref "R0972") (pin "2") (pinfunction "2_2") (pintype "passive"))
      (node (ref "U0101") (pin "8") (pinfunction "PC0_8") (pintype "bidirectional"))
    )
    (net (code "121") (name "PC1") (class "Default")
      (node (ref "R1001") (pin "1") (pinfunction "1_1") (pintype "passive"))
      (node (ref "U0101") (pin "9") (pinfunction "PC1_9") (pintype "bidirectional"))
    )
    (net (code "122") (name "PC2") (class "Default")
      (node (ref "D0971") (pin "A") (pinfunction "A_A") (pintype "passive"))
      (node (ref "R0971") (pin "2") (pinfunction "2_2") (pintype "passive"))
      (node (ref "U0101") (pin "10") (pinfunction "PC2_10") (pintype "bidirectional"))
    )
    (net (code "123") (name "PC3") (class "Default")
      (node (ref "R0921") (pin "1") (pinfunction "1_1") (pintype "passive"))
      (node (ref "U0101") (pin "11") (pinfunction "PC3_11") (pintype "bidirectional"))
    )
    (net (code "124") (name "PC4") (class "Default")
      (node (ref "R0625") (pin "1") (pinfunction "1_1") (pintype "passive"))
      (node (ref "U0101") (pin "24") (pinfunction "PC4_24") (pintype "bidirectional"))
    )
    (net (code "125") (name "PC14_OSC32_IN") (class "Default")
      (node (ref "C0331") (pin "-") (pinfunction "E_-") (pintype "passive"))
      (node (ref "C0332") (pin "1") (pinfunction "1_1") (pintype "passive"))
      (node (ref "Q0321") (pin "2") (pinfunction "2_2") (pintype "passive"))
      (node (ref "U0101") (pin "3") (pinfunction "PC14_OSC32_IN_3") (pintype "bidirectional"))
    )
    (net (code "126") (name "PC15_OSC32_OUT") (class "Default")
      (node (ref "C0311") (pin "1") (pinfunction "1_1") (pintype "passive"))
      (node (ref "Q0321") (pin "1") (pinfunction "1_1") (pintype "passive"))
      (node (ref "U0101") (pin "4") (pinfunction "PC15_OSC32_OUT_4") (pintype "bidirectional"))
    )
    (net (code "127") (name "PH0") (class "Default")
      (node (ref "U0101") (pin "5") (pinfunction "PH0_OSC_IN_5") (pintype "bidirectional"))
    )
    (net (code "128") (name "PH1") (class "Default")
      (node (ref "U0101") (pin "6") (pinfunction "PH1_OSC_OUT_6") (pintype "bidirectional"))
    )
    (net (code "129") (name "PH3_BOOT0") (class "Default")
      (node (ref "R0221") (pin "2") (pinfunction "2_2") (pintype "passive"))
      (node (ref "U0101") (pin "60") (pinfunction "BOOT0_60") (pintype "output"))
      (node (ref "X0222") (pin "2") (pinfunction "2_2") (pintype "passive"))
    )
    (net (code "130") (name "RELAY1") (class "Default")
      (node (ref "U0601") (pin "1") (pinfunction "OUT0_1") (pintype "passive"))
      (node (ref "X1601") (pin "1") (pinfunction "1_1") (pintype "passive"))
    )
    (net (code "131") (name "RELAY2") (class "Default")
      (node (ref "U0601") (pin "2") (pinfunction "OUT1_2") (pintype "passive"))
      (node (ref "X1601") (pin "2") (pinfunction "2_2") (pintype "passive"))
    )
    (net (code "132") (name "RELAY3") (class "Default")
      (node (ref "U0601") (pin "4") (pinfunction "OUT2_4") (pintype "passive"))
      (node (ref "X1601") (pin "3") (pinfunction "3_3") (pintype "passive"))
    )
    (net (code "133") (name "RELAY4") (class "Default")
      (node (ref "U0601") (pin "5") (pinfunction "OUT3_5") (pintype "passive"))
      (node (ref "X1601") (pin "4") (pinfunction "4_4") (pintype "passive"))
    )
    (net (code "134") (name "RELAY5") (class "Default")
      (node (ref "U0601") (pin "12") (pinfunction "OUT4_12") (pintype "passive"))
      (node (ref "X1601") (pin "5") (pinfunction "5_5") (pintype "passive"))
    )
    (net (code "135") (name "RELAY6") (class "Default")
      (node (ref "U0601") (pin "13") (pinfunction "OUT5_13") (pintype "passive"))
      (node (ref "X1601") (pin "6") (pinfunction "6_6") (pintype "passive"))
    )
    (net (code "136") (name "RELAY7") (class "Default")
      (node (ref "U0601") (pin "15") (pinfunction "OUT6_15") (pintype "passive"))
      (node (ref "X1601") (pin "7") (pinfunction "7_7") (pintype "passive"))
    )
    (net (code "137") (name "RELAY8") (class "Default")
      (node (ref "U0601") (pin "16") (pinfunction "OUT7_16") (pintype "passive"))
      (node (ref "X1601") (pin "8") (pinfunction "8_8") (pintype "passive"))
    )
    (net (code "138") (name "RELAY9") (class "Default")
      (node (ref "U0601") (pin "17") (pinfunction "OUT8_17") (pintype "passive"))
      (node (ref "X1601") (pin "9") (pinfunction "9_9") (pintype "passive"))
    )
    (net (code "139") (name "RELAY10") (class "Default")
      (node (ref "U0601") (pin "18") (pinfunction "OUT9_18") (pintype "passive"))
      (node (ref "X1601") (pin "10") (pinfunction "10_10") (pintype "passive"))
    )
    (net (code "140") (name "RELAY11") (class "Default")
      (node (ref "U0601") (pin "20") (pinfunction "OUT10_20") (pintype "passive"))
      (node (ref "X1601") (pin "11") (pinfunction "11_11") (pintype "passive"))
    )
    (net (code "141") (name "RELAY12") (class "Default")
      (node (ref "U0601") (pin "21") (pinfunction "OUT11_21") (pintype "passive"))
      (node (ref "X1601") (pin "12") (pinfunction "12_12") (pintype "passive"))
    )
    (net (code "142") (name "RELAY13") (class "Default")
      (node (ref "U0601") (pin "28") (pinfunction "OUT12_28") (pintype "passive"))
      (node (ref "X1601") (pin "13") (pinfunction "13_13") (pintype "passive"))
    )
    (net (code "143") (name "RELAY14") (class "Default")
      (node (ref "U0601") (pin "29") (pinfunction "OUT13_29") (pintype "passive"))
      (node (ref "X1601") (pin "14") (pinfunction "14_14") (pintype "passive"))
    )
    (net (code "144") (name "RELAY15") (class "Default")
      (node (ref "U0601") (pin "31") (pinfunction "OUT14_31") (pintype "passive"))
      (node (ref "X1601") (pin "15") (pinfunction "15_15") (pintype "passive"))
    )
    (net (code "145") (name "RELAY16") (class "Default")
      (node (ref "U0601") (pin "32") (pinfunction "OUT15_32") (pintype "passive"))
      (node (ref "X1601") (pin "16") (pinfunction "16_16") (pintype "passive"))
    )
    (net (code "146") (name "RELAY17") (class "Default")
      (node (ref "U0701") (pin "1") (pinfunction "OUT0_1") (pintype "passive"))
      (node (ref "X1601") (pin "17") (pinfunction "17_17") (pintype "passive"))
    )
    (net (code "147") (name "RELAY18") (class "Default")
      (node (ref "U0701") (pin "2") (pinfunction "OUT1_2") (pintype "passive"))
      (node (ref "X1601") (pin "18") (pinfunction "18_18") (pintype "passive"))
    )
    (net (code "148") (name "RELAY19") (class "Default")
      (node (ref "U0701") (pin "4") (pinfunction "OUT2_4") (pintype "passive"))
      (node (ref "X1601") (pin "19") (pinfunction "19_19") (pintype "passive"))
    )
    (net (code "149") (name "RELAY20") (class "Default")
      (node (ref "U0701") (pin "5") (pinfunction "OUT3_5") (pintype "passive"))
      (node (ref "X1601") (pin "20") (pinfunction "20_20") (pintype "passive"))
    )
    (net (code "150") (name "RELAY21") (class "Default")
      (node (ref "U0701") (pin "12") (pinfunction "OUT4_12") (pintype "passive"))
      (node (ref "X1602") (pin "1") (pinfunction "1_1") (pintype "passive"))
    )
    (net (code "151") (name "RELAY22") (class "Default")
      (node (ref "U0701") (pin "13") (pinfunction "OUT5_13") (pintype "passive"))
      (node (ref "X1602") (pin "2") (pinfunction "2_2") (pintype "passive"))
    )
    (net (code "152") (name "RELAY23") (class "Default")
      (node (ref "U0701") (pin "15") (pinfunction "OUT6_15") (pintype "passive"))
      (node (ref "X1602") (pin "3") (pinfunction "3_3") (pintype "passive"))
    )
    (net (code "153") (name "RELAY24") (class "Default")
      (node (ref "U0701") (pin "16") (pinfunction "OUT7_16") (pintype "passive"))
      (node (ref "X1602") (pin "4") (pinfunction "4_4") (pintype "passive"))
    )
    (net (code "154") (name "RELAY25") (class "Default")
      (node (ref "U0701") (pin "17") (pinfunction "OUT8_17") (pintype "passive"))
      (node (ref "X1602") (pin "5") (pinfunction "5_5") (pintype "passive"))
    )
    (net (code "155") (name "RELAY26") (class "Default")
      (node (ref "U0701") (pin "18") (pinfunction "OUT9_18") (pintype "passive"))
      (node (ref "X1602") (pin "6") (pinfunction "6_6") (pintype "passive"))
    )
    (net (code "156") (name "RELAY27") (class "Default")
      (node (ref "U0701") (pin "20") (pinfunction "OUT10_20") (pintype "passive"))
      (node (ref "X1602") (pin "7") (pinfunction "7_7") (pintype "passive"))
    )
    (net (code "157") (name "RELAY28") (class "Default")
      (node (ref "U0701") (pin "21") (pinfunction "OUT11_21") (pintype "passive"))
      (node (ref "X1602") (pin "8") (pinfunction "8_8") (pintype "passive"))
    )
    (net (code "158") (name "RELAY29") (class "Default")
      (node (ref "U0701") (pin "28") (pinfunction "OUT12_28") (pintype "passive"))
      (node (ref "X1602") (pin "9") (pinfunction "9_9") (pintype "passive"))
    )
    (net (code "159") (name "RELAY30") (class "Default")
      (node (ref "U0701") (pin "29") (pinfunction "OUT13_29") (pintype "passive"))
      (node (ref "X1602") (pin "10") (pinfunction "10_10") (pintype "passive"))
    )
    (net (code "160") (name "RELAY31") (class "Default")
      (node (ref "U0701") (pin "31") (pinfunction "OUT14_31") (pintype "passive"))
      (node (ref "X1602") (pin "11") (pinfunction "11_11") (pintype "passive"))
    )
    (net (code "161") (name "RELAY32") (class "Default")
      (node (ref "U0701") (pin "32") (pinfunction "OUT15_32") (pintype "passive"))
      (node (ref "X1602") (pin "12") (pinfunction "12_12") (pintype "passive"))
    )
    (net (code "162") (name "RELAY33") (class "Default")
      (node (ref "U0801") (pin "1") (pinfunction "OUT0_1") (pintype "passive"))
      (node (ref "X1602") (pin "13") (pinfunction "13_13") (pintype "passive"))
    )
    (net (code "163") (name "RELAY34") (class "Default")
      (node (ref "U0801") (pin "2") (pinfunction "OUT1_2") (pintype "passive"))
      (node (ref "X1602") (pin "14") (pinfunction "14_14") (pintype "passive"))
    )
    (net (code "164") (name "RELAY35") (class "Default")
      (node (ref "U0801") (pin "4") (pinfunction "OUT2_4") (pintype "passive"))
      (node (ref "X1602") (pin "15") (pinfunction "15_15") (pintype "passive"))
    )
    (net (code "165") (name "RELAY36") (class "Default")
      (node (ref "U0801") (pin "5") (pinfunction "OUT3_5") (pintype "passive"))
      (node (ref "X1602") (pin "16") (pinfunction "16_16") (pintype "passive"))
    )
    (net (code "166") (name "RM_FWD") (class "Default")
      (node (ref "L0901") (pin "2") (pinfunction "2_2") (pintype "passive"))
      (node (ref "X1501") (pin "1") (pinfunction "1_1") (pintype "passive"))
    )
    (net (code "167") (name "RM_REV") (class "Default")
      (node (ref "L0911") (pin "2") (pinfunction "2_2") (pintype "passive"))
      (node (ref "X1511") (pin "1") (pinfunction "1_1") (pintype "passive"))
    )
    (net (code "168") (name "RS_DTE_CTS") (class "Default")
      (node (ref "C1053") (pin "1") (pinfunction "1_1") (pintype "passive"))
      (node (ref "U1001") (pin "7") (pinfunction "T2OUT_7") (pintype "output"))
      (node (ref "X1053") (pin "1") (pinfunction "1_1") (pintype "passive"))
    )
    (net (code "169") (name "RS_DTE_RTR") (class "Default")
      (node (ref "C0054") (pin "1") (pinfunction "1_1") (pintype "passive"))
      (node (ref "U1001") (pin "8") (pinfunction "R2IN_8") (pintype "input"))
      (node (ref "X1053") (pin "2") (pinfunction "2_2") (pintype "passive"))
    )
    (net (code "170") (name "RS_DTE_RXD") (class "Default")
      (node (ref "C1051") (pin "1") (pinfunction "1_1") (pintype "passive"))
      (node (ref "U1001") (pin "14") (pinfunction "T1OUT_14") (pintype "output"))
      (node (ref "X1051") (pin "1") (pinfunction "1_1") (pintype "passive"))
    )
    (net (code "171") (name "RS_DTE_TXD") (class "Default")
      (node (ref "C1052") (pin "1") (pinfunction "1_1") (pintype "passive"))
      (node (ref "U1001") (pin "13") (pinfunction "R1IN_13") (pintype "input"))
      (node (ref "X1051") (pin "2") (pinfunction "2_2") (pintype "passive"))
    )
    (net (code "172") (name "RS_MX_C1P") (class "Default")
      (node (ref "C1002") (pin "1") (pinfunction "1_1") (pintype "passive"))
      (node (ref "U1001") (pin "1") (pinfunction "C1+_1") (pintype "bidirectional"))
    )
    (net (code "173") (name "RS_MX_C2P") (class "Default")
      (node (ref "C1003") (pin "1") (pinfunction "1_1") (pintype "passive"))
      (node (ref "U1001") (pin "4") (pinfunction "C2+_4") (pintype "bidirectional"))
    )
    (net (code "174") (name "RS_MX_VM") (class "Default")
      (node (ref "C1005") (pin "1") (pinfunction "1_1") (pintype "passive"))
      (node (ref "U1001") (pin "6") (pinfunction "V-_6") (pintype "bidirectional"))
    )
    (net (code "175") (name "RS_MX_VP") (class "Default")
      (node (ref "C1004") (pin "1") (pinfunction "1_1") (pintype "passive"))
      (node (ref "U1001") (pin "2") (pinfunction "V+_2") (pintype "bidirectional"))
    )
    (net (code "176") (name "SPI_DRV_C_~{CS}") (class "Default")
      (node (ref "R0724") (pin "2") (pinfunction "2_2") (pintype "passive"))
      (node (ref "U0701") (pin "14") (pinfunction "~{CS}_14") (pintype "input"))
    )
    (net (code "177") (name "SPI_DRV_EXT_~{CS}") (class "Default")
      (node (ref "R0824") (pin "2") (pinfunction "2_2") (pintype "passive"))
      (node (ref "U0801") (pin "14") (pinfunction "~{CS}_14") (pintype "input"))
    )
    (net (code "178") (name "SPI_DRV_L_~{CS}") (class "Default")
      (node (ref "R0624") (pin "2") (pinfunction "2_2") (pintype "passive"))
      (node (ref "U0601") (pin "14") (pinfunction "~{CS}_14") (pintype "input"))
    )
    (net (code "179") (name "SPI_DRV_PWM") (class "Default")
      (node (ref "R0626") (pin "2") (pinfunction "2_2") (pintype "passive"))
      (node (ref "U0601") (pin "30") (pinfunction "PWM_30") (pintype "input"))
      (node (ref "U0701") (pin "30") (pinfunction "PWM_30") (pintype "input"))
      (node (ref "U0801") (pin "30") (pinfunction "PWM_30") (pintype "input"))
    )
    (net (code "180") (name "SPI_DRV_SCLK") (class "Default")
      (node (ref "R0621") (pin "2") (pinfunction "2_2") (pintype "passive"))
      (node (ref "U0601") (pin "11") (pinfunction "SCLK_11") (pintype "input"))
      (node (ref "U0701") (pin "11") (pinfunction "SCLK_11") (pintype "input"))
      (node (ref "U0801") (pin "11") (pinfunction "SCLK_11") (pintype "input"))
    )
    (net (code "181") (name "SPI_DRV_SI") (class "Default")
      (node (ref "R0623") (pin "2") (pinfunction "2_2") (pintype "passive"))
      (node (ref "U0601") (pin "19") (pinfunction "SI_19") (pintype "input"))
      (node (ref "U0701") (pin "19") (pinfunction "SI_19") (pintype "input"))
      (node (ref "U0801") (pin "19") (pinfunction "SI_19") (pintype "input"))
    )
    (net (code "182") (name "SPI_DRV_SO") (class "Default")
      (node (ref "R0611") (pin "1") (pinfunction "1_1") (pintype "passive"))
      (node (ref "R0622") (pin "2") (pinfunction "2_2") (pintype "passive"))
      (node (ref "R0711") (pin "1") (pinfunction "1_1") (pintype "passive"))
      (node (ref "R0811") (pin "1") (pinfunction "1_1") (pintype "passive"))
    )
    (net (code "183") (name "SPI_DRV_~{RST}") (class "Default")
      (node (ref "R0625") (pin "2") (pinfunction "2_2") (pintype "passive"))
      (node (ref "U0601") (pin "27") (pinfunction "~{RST}_27") (pintype "input"))
      (node (ref "U0701") (pin "27") (pinfunction "~{RST}_27") (pintype "input"))
      (node (ref "U0801") (pin "27") (pinfunction "~{RST}_27") (pintype "input"))
    )
    (net (code "184") (name "SWR_IN_FWD") (class "Default")
      (node (ref "R0902") (pin "2") (pinfunction "2_2") (pintype "passive"))
      (node (ref "R0903") (pin "1") (pinfunction "1_1") (pintype "passive"))
      (node (ref "U0921") (pin "1") (pinfunction "1_1") (pintype "passive"))
    )
    (net (code "185") (name "SWR_IN_FWD_HI") (class "Default")
      (node (ref "C0901") (pin "1") (pinfunction "1_1") (pintype "passive"))
      (node (ref "L0901") (pin "1") (pinfunction "1_1") (pintype "passive"))
      (node (ref "R0901") (pin "2") (pinfunction "2_2") (pintype "passive"))
      (node (ref "R0902") (pin "1") (pinfunction "1_1") (pintype "passive"))
    )
    (net (code "186") (name "SWR_IN_REV") (class "Default")
      (node (ref "R0912") (pin "2") (pinfunction "2_2") (pintype "passive"))
      (node (ref "R0913") (pin "1") (pinfunction "1_1") (pintype "passive"))
      (node (ref "U0921") (pin "5") (pinfunction "5_5") (pintype "passive"))
    )
    (net (code "187") (name "SWR_IN_REV_HI") (class "Default")
      (node (ref "C0911") (pin "1") (pinfunction "1_1") (pintype "passive"))
      (node (ref "L0911") (pin "1") (pinfunction "1_1") (pintype "passive"))
      (node (ref "R0911") (pin "2") (pinfunction "2_2") (pintype "passive"))
      (node (ref "R0912") (pin "1") (pinfunction "1_1") (pintype "passive"))
    )
    (net (code "188") (name "SWR_SEL_FWD") (class "Default")
      (node (ref "R0921") (pin "2") (pinfunction "2_2") (pintype "passive"))
      (node (ref "U0921") (pin "7") (pinfunction "7_7") (pintype "input"))
    )
    (net (code "189") (name "SWR_SEL_PWR") (class "Default")
      (node (ref "D0951") (pin "A") (pinfunction "A_A") (pintype "passive"))
      (node (ref "U0921") (pin "2") (pinfunction "2_2") (pintype "passive"))
      (node (ref "U0921") (pin "6") (pinfunction "6_6") (pintype "passive"))
      (node (ref "U0951") (pin "4") (pinfunction "-IN_4") (pintype "input"))
    )
    (net (code "190") (name "SWR_SEL_REV") (class "Default")
      (node (ref "R0922") (pin "2") (pinfunction "2_2") (pintype "passive"))
      (node (ref "U0921") (pin "3") (pinfunction "3_3") (pintype "input"))
    )
    (net (code "191") (name "TPS_LBO") (class "Default")
      (node (ref "R1322") (pin "1") (pinfunction "1_1") (pintype "passive"))
      (node (ref "U1301") (pin "2") (pinfunction "LBO_2") (pintype "output"))
    )
    (net (code "192") (name "TPS_PG") (class "Default")
      (node (ref "R1321") (pin "1") (pinfunction "1_1") (pintype "passive"))
      (node (ref "U1301") (pin "4") (pinfunction "PG_4") (pintype "output"))
    )
    (net (code "193") (name "VDDUSB") (class "Default")
      (node (ref "D1221") (pin "A") (pinfunction "A_A") (pintype "passive"))
      (node (ref "PF1411") (pin "2") (pinfunction "2_2") (pintype "passive"))
      (node (ref "U0101") (pin "48") (pinfunction "VDDUSB_48") (pintype "power_in"))
    )
    (net (code "194") (name "unconnected-(U0101-PA2_WKUP-Pad16)") (class "Default")
      (node (ref "U0101") (pin "16") (pinfunction "PA2_WKUP_16") (pintype "bidirectional"))
    )
    (net (code "195") (name "unconnected-(U0101-PA4-Pad20)") (class "Default")
      (node (ref "U0101") (pin "20") (pinfunction "PA4_20") (pintype "bidirectional"))
    )
    (net (code "196") (name "unconnected-(U0101-PA8-Pad41)") (class "Default")
      (node (ref "U0101") (pin "41") (pinfunction "PA8_41") (pintype "bidirectional"))
    )
    (net (code "197") (name "unconnected-(U0101-PB3_JTDO_TRACESWO-Pad55)") (class "Default")
      (node (ref "U0101") (pin "55") (pinfunction "PB3_JTDO_TRACESWO_55") (pintype "bidirectional"))
    )
    (net (code "198") (name "unconnected-(U0101-PB4_NJTRST-Pad56)") (class "Default")
      (node (ref "U0101") (pin "56") (pinfunction "PB4_NJTRST_56") (pintype "bidirectional"))
    )
    (net (code "199") (name "unconnected-(U0101-PB5-Pad57)") (class "Default")
      (node (ref "U0101") (pin "57") (pinfunction "PB5_57") (pintype "bidirectional"))
    )
    (net (code "200") (name "unconnected-(U0101-PB8-Pad61)") (class "Default")
      (node (ref "U0101") (pin "61") (pinfunction "PB8_61") (pintype "bidirectional"))
    )
    (net (code "201") (name "unconnected-(U0101-PB14-Pad35)") (class "Default")
      (node (ref "U0101") (pin "35") (pinfunction "PB14_35") (pintype "bidirectional"))
    )
    (net (code "202") (name "unconnected-(U0101-PB15-Pad36)") (class "Default")
      (node (ref "U0101") (pin "36") (pinfunction "PB15_36") (pintype "bidirectional"))
    )
    (net (code "203") (name "unconnected-(U0101-PC5_WKUP-Pad25)") (class "Default")
      (node (ref "U0101") (pin "25") (pinfunction "PC5_WKUP_25") (pintype "bidirectional"))
    )
    (net (code "204") (name "unconnected-(U0101-PC6-Pad37)") (class "Default")
      (node (ref "U0101") (pin "37") (pinfunction "PC6_37") (pintype "bidirectional"))
    )
    (net (code "205") (name "unconnected-(U0101-PC7-Pad38)") (class "Default")
      (node (ref "U0101") (pin "38") (pinfunction "PC7_38") (pintype "bidirectional"))
    )
    (net (code "206") (name "unconnected-(U0101-PC8-Pad39)") (class "Default")
      (node (ref "U0101") (pin "39") (pinfunction "PC8_39") (pintype "bidirectional"))
    )
    (net (code "207") (name "unconnected-(U0101-PC9-Pad40)") (class "Default")
      (node (ref "U0101") (pin "40") (pinfunction "PC9_40") (pintype "bidirectional"))
    )
    (net (code "208") (name "unconnected-(U0101-PC10-Pad51)") (class "Default")
      (node (ref "U0101") (pin "51") (pinfunction "PC10_51") (pintype "bidirectional"))
    )
    (net (code "209") (name "unconnected-(U0101-PC11-Pad52)") (class "Default")
      (node (ref "U0101") (pin "52") (pinfunction "PC11_52") (pintype "bidirectional"))
    )
    (net (code "210") (name "unconnected-(U0101-PC12-Pad53)") (class "Default")
      (node (ref "U0101") (pin "53") (pinfunction "PC12_53") (pintype "bidirectional"))
    )
    (net (code "211") (name "unconnected-(U0101-PC13_WKUP-Pad2)") (class "Default")
      (node (ref "U0101") (pin "2") (pinfunction "PC13_WKUP_2") (pintype "bidirectional"))
    )
    (net (code "212") (name "unconnected-(U0101-PD2-Pad54)") (class "Default")
      (node (ref "U0101") (pin "54") (pinfunction "PD2_54") (pintype "bidirectional"))
    )
    (net (code "213") (name "unconnected-(U0962-P0B-Pad10)") (class "Default")
      (node (ref "U0962") (pin "10") (pinfunction "P0B_10") (pintype "passive"))
    )
    (net (code "214") (name "unconnected-(U0962-P1B-Pad5)") (class "Default")
      (node (ref "U0962") (pin "5") (pinfunction "P1B_5") (pintype "passive"))
    )
    (net (code "215") (name "unconnected-(U1201-NC-Pad14)") (class "Default")
      (node (ref "U1201") (pin "14") (pinfunction "NC_14") (pintype "no_connect"))
    )
    (net (code "216") (name "unconnected-(U1201-~{RESET}-Pad8)") (class "Default")
      (node (ref "U1201") (pin "8") (pinfunction "~{RESET}_8") (pintype "output"))
    )
    (net (code "217") (name "unconnected-(X0201-Pad6)") (class "Default")
      (node (ref "X0201") (pin "6") (pinfunction "6_6") (pintype "passive"))
    )
    (net (code "218") (name "unconnected-(X0201-Pad7)") (class "Default")
      (node (ref "X0201") (pin "7") (pinfunction "7_7") (pintype "passive"))
    )
    (net (code "219") (name "unconnected-(X0201-Pad8)") (class "Default")
      (node (ref "X0201") (pin "8") (pinfunction "8_8") (pintype "passive"))
    )
  )
)
